# LargePrototype.net
KiCad netlist of a schematic drawn in EAGLE
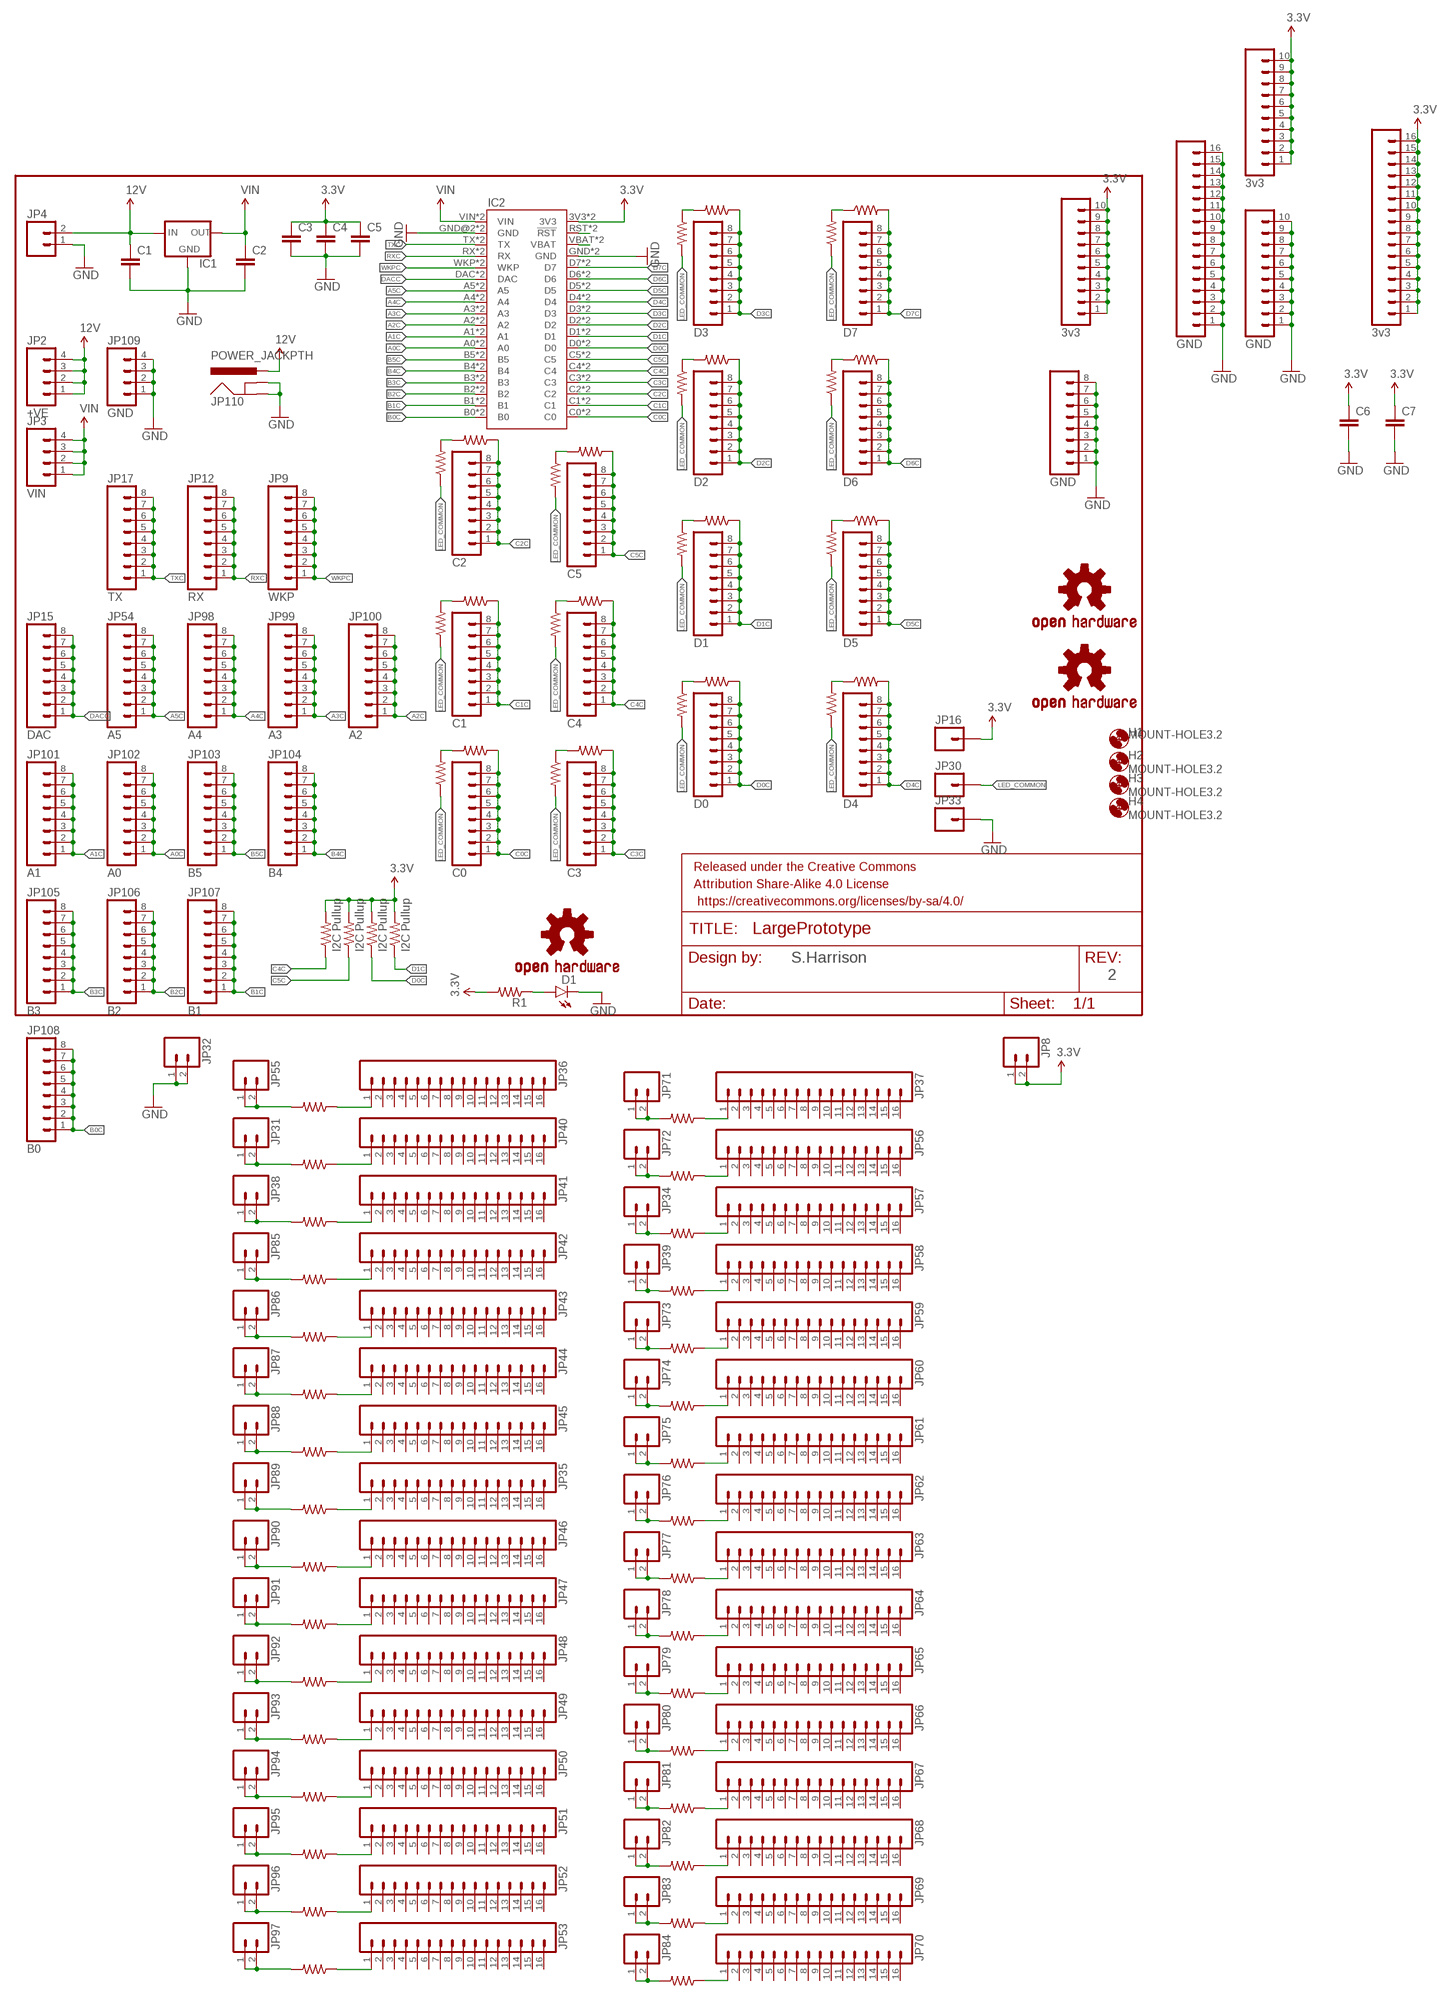
[diagram p0: schematic, sheet 1, part 1 of 2]
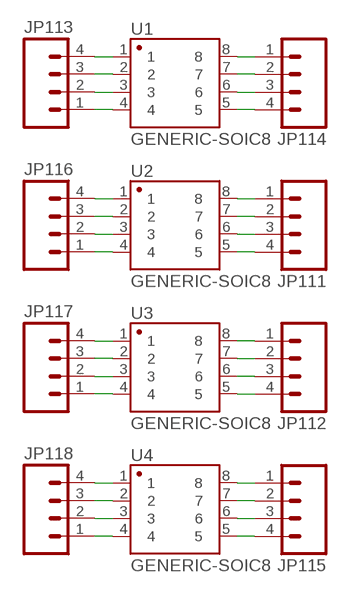
[diagram p1: schematic, sheet 1, part 2 of 2]

(export (version "E")
  (design (tool "Eeschema 10.0.6"))
  (components
    (comp (ref "C1")
      (value "1UF-25V-10%(0805)\"")
      (footprint "eagle-import:0805-CAP")
      (libsource (lib "eagle-import") (part "1UF-25V-10%(0805){dblquote}"))
    )
    (comp (ref "C2")
      (value "1UF-25V-10%(0805)\"")
      (footprint "eagle-import:0805-CAP")
      (libsource (lib "eagle-import") (part "1UF-25V-10%(0805){dblquote}"))
    )
    (comp (ref "C3")
      (value "1UF-25V-10%(0805)\"")
      (footprint "eagle-import:0805-CAP")
      (libsource (lib "eagle-import") (part "1UF-25V-10%(0805){dblquote}"))
    )
    (comp (ref "C4")
      (value "1UF-25V-10%(0805)\"")
      (footprint "eagle-import:0805-CAP")
      (libsource (lib "eagle-import") (part "1UF-25V-10%(0805){dblquote}"))
    )
    (comp (ref "C5")
      (value "1UF-25V-10%(0805)\"")
      (footprint "eagle-import:0805-CAP")
      (libsource (lib "eagle-import") (part "1UF-25V-10%(0805){dblquote}"))
    )
    (comp (ref "C6")
      (value "1UF-25V-10%(0805)\"")
      (footprint "eagle-import:0805-CAP")
      (libsource (lib "eagle-import") (part "1UF-25V-10%(0805){dblquote}"))
    )
    (comp (ref "C7")
      (value "1UF-25V-10%(0805)\"")
      (footprint "eagle-import:0805-CAP")
      (libsource (lib "eagle-import") (part "1UF-25V-10%(0805){dblquote}"))
    )
    (comp (ref "D1")
      (value "LED1206-BOTTOM")
      (footprint "eagle-import:LED-1206-BOTTOM")
      (libsource (lib "eagle-import") (part "LED1206-BOTTOM"))
    )
    (comp (ref "FRAME1")
      (value "FRAME-LETTER")
      (footprint "eagle-import:CREATIVE_COMMONS")
      (libsource (lib "eagle-import") (part "FRAME-LETTER"))
    )
    (comp (ref "H1")
      (value "MOUNT-HOLE3.2")
      (footprint "eagle-import:3,2")
      (libsource (lib "eagle-import") (part "MOUNT-HOLE3.2"))
    )
    (comp (ref "H2")
      (value "MOUNT-HOLE3.2")
      (footprint "eagle-import:3,2")
      (libsource (lib "eagle-import") (part "MOUNT-HOLE3.2"))
    )
    (comp (ref "H3")
      (value "MOUNT-HOLE3.2")
      (footprint "eagle-import:3,2")
      (libsource (lib "eagle-import") (part "MOUNT-HOLE3.2"))
    )
    (comp (ref "H4")
      (value "MOUNT-HOLE3.2")
      (footprint "eagle-import:3,2")
      (libsource (lib "eagle-import") (part "MOUNT-HOLE3.2"))
    )
    (comp (ref "IC1")
      (value "78XXS")
      (footprint "eagle-import:78XXS")
      (libsource (lib "eagle-import") (part "78XXS"))
    )
    (comp (ref "IC2")
      (value "ELECTRONDUALNAMED")
      (footprint "eagle-import:ELECTRON_SIMPLE_SILK_NAMES_DUAL")
      (libsource (lib "eagle-import") (part "ELECTRONDUALNAMED"))
    )
    (comp (ref "JP1")
      (value "D7")
      (footprint "eagle-import:1X08_ROUND")
      (libsource (lib "eagle-import") (part "M08"))
    )
    (comp (ref "JP2")
      (value "+VE")
      (footprint "eagle-import:1X04")
      (libsource (lib "eagle-import") (part "M04PTH"))
    )
    (comp (ref "JP3")
      (value "VIN")
      (footprint "eagle-import:1X04")
      (libsource (lib "eagle-import") (part "M04PTH"))
    )
    (comp (ref "JP4")
      (value "M025MM")
      (footprint "eagle-import:SCREWTERMINAL-5MM-2")
      (libsource (lib "eagle-import") (part "M025MM"))
    )
    (comp (ref "JP5")
      (value "3v3")
      (footprint "eagle-import:1X10")
      (libsource (lib "eagle-import") (part "M10SILK_FEMALE_PTH"))
    )
    (comp (ref "JP6")
      (value "3v3")
      (footprint "eagle-import:1X10")
      (libsource (lib "eagle-import") (part "M10SILK_FEMALE_PTH"))
    )
    (comp (ref "JP7")
      (value "D6")
      (footprint "eagle-import:1X08_ROUND")
      (libsource (lib "eagle-import") (part "M08"))
    )
    (comp (ref "JP8")
      (value "M02PTH")
      (footprint "eagle-import:1X02")
      (libsource (lib "eagle-import") (part "M02PTH"))
    )
    (comp (ref "JP9")
      (value "WKP")
      (footprint "eagle-import:1X08_ROUND")
      (libsource (lib "eagle-import") (part "M08"))
    )
    (comp (ref "JP10")
      (value "D5")
      (footprint "eagle-import:1X08_ROUND")
      (libsource (lib "eagle-import") (part "M08"))
    )
    (comp (ref "JP11")
      (value "GND")
      (footprint "eagle-import:1X10")
      (libsource (lib "eagle-import") (part "M10SILK_FEMALE_PTH"))
    )
    (comp (ref "JP12")
      (value "RX")
      (footprint "eagle-import:1X08_ROUND")
      (libsource (lib "eagle-import") (part "M08"))
    )
    (comp (ref "JP13")
      (value "3v3")
      (footprint "eagle-import:1X16")
      (libsource (lib "eagle-import") (part "M16PTH"))
    )
    (comp (ref "JP14")
      (value "GND")
      (footprint "eagle-import:1X16")
      (libsource (lib "eagle-import") (part "M16PTH"))
    )
    (comp (ref "JP15")
      (value "DAC")
      (footprint "eagle-import:1X08_ROUND")
      (libsource (lib "eagle-import") (part "M08"))
    )
    (comp (ref "JP16")
      (value "M01PTH")
      (footprint "eagle-import:1X01")
      (libsource (lib "eagle-import") (part "M01PTH"))
    )
    (comp (ref "JP17")
      (value "TX")
      (footprint "eagle-import:1X08_ROUND")
      (libsource (lib "eagle-import") (part "M08"))
    )
    (comp (ref "JP18")
      (value "D4")
      (footprint "eagle-import:1X08_ROUND")
      (libsource (lib "eagle-import") (part "M08"))
    )
    (comp (ref "JP19")
      (value "D3")
      (footprint "eagle-import:1X08_ROUND")
      (libsource (lib "eagle-import") (part "M08"))
    )
    (comp (ref "JP20")
      (value "D2")
      (footprint "eagle-import:1X08_ROUND")
      (libsource (lib "eagle-import") (part "M08"))
    )
    (comp (ref "JP21")
      (value "D1")
      (footprint "eagle-import:1X08_ROUND")
      (libsource (lib "eagle-import") (part "M08"))
    )
    (comp (ref "JP22")
      (value "D0")
      (footprint "eagle-import:1X08_ROUND")
      (libsource (lib "eagle-import") (part "M08"))
    )
    (comp (ref "JP23")
      (value "GND")
      (footprint "eagle-import:1X08_ROUND")
      (libsource (lib "eagle-import") (part "M08"))
    )
    (comp (ref "JP24")
      (value "C5")
      (footprint "eagle-import:1X08_ROUND")
      (libsource (lib "eagle-import") (part "M08"))
    )
    (comp (ref "JP25")
      (value "C4")
      (footprint "eagle-import:1X08_ROUND")
      (libsource (lib "eagle-import") (part "M08"))
    )
    (comp (ref "JP26")
      (value "C3")
      (footprint "eagle-import:1X08_ROUND")
      (libsource (lib "eagle-import") (part "M08"))
    )
    (comp (ref "JP27")
      (value "C2")
      (footprint "eagle-import:1X08_ROUND")
      (libsource (lib "eagle-import") (part "M08"))
    )
    (comp (ref "JP28")
      (value "C1")
      (footprint "eagle-import:1X08_ROUND")
      (libsource (lib "eagle-import") (part "M08"))
    )
    (comp (ref "JP29")
      (value "C0")
      (footprint "eagle-import:1X08_ROUND")
      (libsource (lib "eagle-import") (part "M08"))
    )
    (comp (ref "JP30")
      (value "M01PTH")
      (footprint "eagle-import:1X01")
      (libsource (lib "eagle-import") (part "M01PTH"))
    )
    (comp (ref "JP31")
      (value "M02PTH")
      (footprint "eagle-import:1X02")
      (libsource (lib "eagle-import") (part "M02PTH"))
    )
    (comp (ref "JP32")
      (value "M02PTH")
      (footprint "eagle-import:1X02")
      (libsource (lib "eagle-import") (part "M02PTH"))
    )
    (comp (ref "JP33")
      (value "M01PTH")
      (footprint "eagle-import:1X01")
      (libsource (lib "eagle-import") (part "M01PTH"))
    )
    (comp (ref "JP34")
      (value "M02PTH")
      (footprint "eagle-import:1X02")
      (libsource (lib "eagle-import") (part "M02PTH"))
    )
    (comp (ref "JP35")
      (value "M161X16_NO_SILK")
      (footprint "eagle-import:1X16_NO_SILK")
      (libsource (lib "eagle-import") (part "M161X16_NO_SILK"))
    )
    (comp (ref "JP36")
      (value "M161X16_NO_SILK")
      (footprint "eagle-import:1X16_NO_SILK")
      (libsource (lib "eagle-import") (part "M161X16_NO_SILK"))
    )
    (comp (ref "JP37")
      (value "M161X16_NO_SILK")
      (footprint "eagle-import:1X16_NO_SILK")
      (libsource (lib "eagle-import") (part "M161X16_NO_SILK"))
    )
    (comp (ref "JP38")
      (value "M02PTH")
      (footprint "eagle-import:1X02")
      (libsource (lib "eagle-import") (part "M02PTH"))
    )
    (comp (ref "JP39")
      (value "M02PTH")
      (footprint "eagle-import:1X02")
      (libsource (lib "eagle-import") (part "M02PTH"))
    )
    (comp (ref "JP40")
      (value "M161X16_NO_SILK")
      (footprint "eagle-import:1X16_NO_SILK")
      (libsource (lib "eagle-import") (part "M161X16_NO_SILK"))
    )
    (comp (ref "JP41")
      (value "M161X16_NO_SILK")
      (footprint "eagle-import:1X16_NO_SILK")
      (libsource (lib "eagle-import") (part "M161X16_NO_SILK"))
    )
    (comp (ref "JP42")
      (value "M161X16_NO_SILK")
      (footprint "eagle-import:1X16_NO_SILK")
      (libsource (lib "eagle-import") (part "M161X16_NO_SILK"))
    )
    (comp (ref "JP43")
      (value "M161X16_NO_SILK")
      (footprint "eagle-import:1X16_NO_SILK")
      (libsource (lib "eagle-import") (part "M161X16_NO_SILK"))
    )
    (comp (ref "JP44")
      (value "M161X16_NO_SILK")
      (footprint "eagle-import:1X16_NO_SILK")
      (libsource (lib "eagle-import") (part "M161X16_NO_SILK"))
    )
    (comp (ref "JP45")
      (value "M161X16_NO_SILK")
      (footprint "eagle-import:1X16_NO_SILK")
      (libsource (lib "eagle-import") (part "M161X16_NO_SILK"))
    )
    (comp (ref "JP46")
      (value "M161X16_NO_SILK")
      (footprint "eagle-import:1X16_NO_SILK")
      (libsource (lib "eagle-import") (part "M161X16_NO_SILK"))
    )
    (comp (ref "JP47")
      (value "M161X16_NO_SILK")
      (footprint "eagle-import:1X16_NO_SILK")
      (libsource (lib "eagle-import") (part "M161X16_NO_SILK"))
    )
    (comp (ref "JP48")
      (value "M161X16_NO_SILK")
      (footprint "eagle-import:1X16_NO_SILK")
      (libsource (lib "eagle-import") (part "M161X16_NO_SILK"))
    )
    (comp (ref "JP49")
      (value "M161X16_NO_SILK")
      (footprint "eagle-import:1X16_NO_SILK")
      (libsource (lib "eagle-import") (part "M161X16_NO_SILK"))
    )
    (comp (ref "JP50")
      (value "M161X16_NO_SILK")
      (footprint "eagle-import:1X16_NO_SILK")
      (libsource (lib "eagle-import") (part "M161X16_NO_SILK"))
    )
    (comp (ref "JP51")
      (value "M161X16_NO_SILK")
      (footprint "eagle-import:1X16_NO_SILK")
      (libsource (lib "eagle-import") (part "M161X16_NO_SILK"))
    )
    (comp (ref "JP52")
      (value "M161X16_NO_SILK")
      (footprint "eagle-import:1X16_NO_SILK")
      (libsource (lib "eagle-import") (part "M161X16_NO_SILK"))
    )
    (comp (ref "JP53")
      (value "M161X16_NO_SILK")
      (footprint "eagle-import:1X16_NO_SILK")
      (libsource (lib "eagle-import") (part "M161X16_NO_SILK"))
    )
    (comp (ref "JP54")
      (value "A5")
      (footprint "eagle-import:1X08_ROUND")
      (libsource (lib "eagle-import") (part "M08"))
    )
    (comp (ref "JP55")
      (value "M02PTH")
      (footprint "eagle-import:1X02")
      (libsource (lib "eagle-import") (part "M02PTH"))
    )
    (comp (ref "JP56")
      (value "M161X16_NO_SILK")
      (footprint "eagle-import:1X16_NO_SILK")
      (libsource (lib "eagle-import") (part "M161X16_NO_SILK"))
    )
    (comp (ref "JP57")
      (value "M161X16_NO_SILK")
      (footprint "eagle-import:1X16_NO_SILK")
      (libsource (lib "eagle-import") (part "M161X16_NO_SILK"))
    )
    (comp (ref "JP58")
      (value "M161X16_NO_SILK")
      (footprint "eagle-import:1X16_NO_SILK")
      (libsource (lib "eagle-import") (part "M161X16_NO_SILK"))
    )
    (comp (ref "JP59")
      (value "M161X16_NO_SILK")
      (footprint "eagle-import:1X16_NO_SILK")
      (libsource (lib "eagle-import") (part "M161X16_NO_SILK"))
    )
    (comp (ref "JP60")
      (value "M161X16_NO_SILK")
      (footprint "eagle-import:1X16_NO_SILK")
      (libsource (lib "eagle-import") (part "M161X16_NO_SILK"))
    )
    (comp (ref "JP61")
      (value "M161X16_NO_SILK")
      (footprint "eagle-import:1X16_NO_SILK")
      (libsource (lib "eagle-import") (part "M161X16_NO_SILK"))
    )
    (comp (ref "JP62")
      (value "M161X16_NO_SILK")
      (footprint "eagle-import:1X16_NO_SILK")
      (libsource (lib "eagle-import") (part "M161X16_NO_SILK"))
    )
    (comp (ref "JP63")
      (value "M161X16_NO_SILK")
      (footprint "eagle-import:1X16_NO_SILK")
      (libsource (lib "eagle-import") (part "M161X16_NO_SILK"))
    )
    (comp (ref "JP64")
      (value "M161X16_NO_SILK")
      (footprint "eagle-import:1X16_NO_SILK")
      (libsource (lib "eagle-import") (part "M161X16_NO_SILK"))
    )
    (comp (ref "JP65")
      (value "M161X16_NO_SILK")
      (footprint "eagle-import:1X16_NO_SILK")
      (libsource (lib "eagle-import") (part "M161X16_NO_SILK"))
    )
    (comp (ref "JP66")
      (value "M161X16_NO_SILK")
      (footprint "eagle-import:1X16_NO_SILK")
      (libsource (lib "eagle-import") (part "M161X16_NO_SILK"))
    )
    (comp (ref "JP67")
      (value "M161X16_NO_SILK")
      (footprint "eagle-import:1X16_NO_SILK")
      (libsource (lib "eagle-import") (part "M161X16_NO_SILK"))
    )
    (comp (ref "JP68")
      (value "M161X16_NO_SILK")
      (footprint "eagle-import:1X16_NO_SILK")
      (libsource (lib "eagle-import") (part "M161X16_NO_SILK"))
    )
    (comp (ref "JP69")
      (value "M161X16_NO_SILK")
      (footprint "eagle-import:1X16_NO_SILK")
      (libsource (lib "eagle-import") (part "M161X16_NO_SILK"))
    )
    (comp (ref "JP70")
      (value "M161X16_NO_SILK")
      (footprint "eagle-import:1X16_NO_SILK")
      (libsource (lib "eagle-import") (part "M161X16_NO_SILK"))
    )
    (comp (ref "JP71")
      (value "M02PTH")
      (footprint "eagle-import:1X02")
      (libsource (lib "eagle-import") (part "M02PTH"))
    )
    (comp (ref "JP72")
      (value "M02PTH")
      (footprint "eagle-import:1X02")
      (libsource (lib "eagle-import") (part "M02PTH"))
    )
    (comp (ref "JP73")
      (value "M02PTH")
      (footprint "eagle-import:1X02")
      (libsource (lib "eagle-import") (part "M02PTH"))
    )
    (comp (ref "JP74")
      (value "M02PTH")
      (footprint "eagle-import:1X02")
      (libsource (lib "eagle-import") (part "M02PTH"))
    )
    (comp (ref "JP75")
      (value "M02PTH")
      (footprint "eagle-import:1X02")
      (libsource (lib "eagle-import") (part "M02PTH"))
    )
    (comp (ref "JP76")
      (value "M02PTH")
      (footprint "eagle-import:1X02")
      (libsource (lib "eagle-import") (part "M02PTH"))
    )
    (comp (ref "JP77")
      (value "M02PTH")
      (footprint "eagle-import:1X02")
      (libsource (lib "eagle-import") (part "M02PTH"))
    )
    (comp (ref "JP78")
      (value "M02PTH")
      (footprint "eagle-import:1X02")
      (libsource (lib "eagle-import") (part "M02PTH"))
    )
    (comp (ref "JP79")
      (value "M02PTH")
      (footprint "eagle-import:1X02")
      (libsource (lib "eagle-import") (part "M02PTH"))
    )
    (comp (ref "JP80")
      (value "M02PTH")
      (footprint "eagle-import:1X02")
      (libsource (lib "eagle-import") (part "M02PTH"))
    )
    (comp (ref "JP81")
      (value "M02PTH")
      (footprint "eagle-import:1X02")
      (libsource (lib "eagle-import") (part "M02PTH"))
    )
    (comp (ref "JP82")
      (value "M02PTH")
      (footprint "eagle-import:1X02")
      (libsource (lib "eagle-import") (part "M02PTH"))
    )
    (comp (ref "JP83")
      (value "M02PTH")
      (footprint "eagle-import:1X02")
      (libsource (lib "eagle-import") (part "M02PTH"))
    )
    (comp (ref "JP84")
      (value "M02PTH")
      (footprint "eagle-import:1X02")
      (libsource (lib "eagle-import") (part "M02PTH"))
    )
    (comp (ref "JP85")
      (value "M02PTH")
      (footprint "eagle-import:1X02")
      (libsource (lib "eagle-import") (part "M02PTH"))
    )
    (comp (ref "JP86")
      (value "M02PTH")
      (footprint "eagle-import:1X02")
      (libsource (lib "eagle-import") (part "M02PTH"))
    )
    (comp (ref "JP87")
      (value "M02PTH")
      (footprint "eagle-import:1X02")
      (libsource (lib "eagle-import") (part "M02PTH"))
    )
    (comp (ref "JP88")
      (value "M02PTH")
      (footprint "eagle-import:1X02")
      (libsource (lib "eagle-import") (part "M02PTH"))
    )
    (comp (ref "JP89")
      (value "M02PTH")
      (footprint "eagle-import:1X02")
      (libsource (lib "eagle-import") (part "M02PTH"))
    )
    (comp (ref "JP90")
      (value "M02PTH")
      (footprint "eagle-import:1X02")
      (libsource (lib "eagle-import") (part "M02PTH"))
    )
    (comp (ref "JP91")
      (value "M02PTH")
      (footprint "eagle-import:1X02")
      (libsource (lib "eagle-import") (part "M02PTH"))
    )
    (comp (ref "JP92")
      (value "M02PTH")
      (footprint "eagle-import:1X02")
      (libsource (lib "eagle-import") (part "M02PTH"))
    )
    (comp (ref "JP93")
      (value "M02PTH")
      (footprint "eagle-import:1X02")
      (libsource (lib "eagle-import") (part "M02PTH"))
    )
    (comp (ref "JP94")
      (value "M02PTH")
      (footprint "eagle-import:1X02")
      (libsource (lib "eagle-import") (part "M02PTH"))
    )
    (comp (ref "JP95")
      (value "M02PTH")
      (footprint "eagle-import:1X02")
      (libsource (lib "eagle-import") (part "M02PTH"))
    )
    (comp (ref "JP96")
      (value "M02PTH")
      (footprint "eagle-import:1X02")
      (libsource (lib "eagle-import") (part "M02PTH"))
    )
    (comp (ref "JP97")
      (value "M02PTH")
      (footprint "eagle-import:1X02")
      (libsource (lib "eagle-import") (part "M02PTH"))
    )
    (comp (ref "JP98")
      (value "A4")
      (footprint "eagle-import:1X08_ROUND")
      (libsource (lib "eagle-import") (part "M08"))
    )
    (comp (ref "JP99")
      (value "A3")
      (footprint "eagle-import:1X08_ROUND")
      (libsource (lib "eagle-import") (part "M08"))
    )
    (comp (ref "JP100")
      (value "A2")
      (footprint "eagle-import:1X08_ROUND")
      (libsource (lib "eagle-import") (part "M08"))
    )
    (comp (ref "JP101")
      (value "A1")
      (footprint "eagle-import:1X08_ROUND")
      (libsource (lib "eagle-import") (part "M08"))
    )
    (comp (ref "JP102")
      (value "A0")
      (footprint "eagle-import:1X08_ROUND")
      (libsource (lib "eagle-import") (part "M08"))
    )
    (comp (ref "JP103")
      (value "B5")
      (footprint "eagle-import:1X08_ROUND")
      (libsource (lib "eagle-import") (part "M08"))
    )
    (comp (ref "JP104")
      (value "B4")
      (footprint "eagle-import:1X08_ROUND")
      (libsource (lib "eagle-import") (part "M08"))
    )
    (comp (ref "JP105")
      (value "B3")
      (footprint "eagle-import:1X08_ROUND")
      (libsource (lib "eagle-import") (part "M08"))
    )
    (comp (ref "JP106")
      (value "B2")
      (footprint "eagle-import:1X08_ROUND")
      (libsource (lib "eagle-import") (part "M08"))
    )
    (comp (ref "JP107")
      (value "B1")
      (footprint "eagle-import:1X08_ROUND")
      (libsource (lib "eagle-import") (part "M08"))
    )
    (comp (ref "JP108")
      (value "B0")
      (footprint "eagle-import:1X08_ROUND")
      (libsource (lib "eagle-import") (part "M08"))
    )
    (comp (ref "JP109")
      (value "GND")
      (footprint "eagle-import:1X04")
      (libsource (lib "eagle-import") (part "M04PTH"))
    )
    (comp (ref "JP110")
      (value "POWER_JACKPTH")
      (footprint "eagle-import:POWER_JACK_PTH")
      (libsource (lib "eagle-import") (part "POWER_JACKPTH"))
    )
    (comp (ref "JP111")
      (value "M04NO_SILK_ALL_ROUND")
      (footprint "eagle-import:1X04_NO_SILK_ALL_ROUND")
      (libsource (lib "eagle-import") (part "M04NO_SILK_ALL_ROUND"))
    )
    (comp (ref "JP112")
      (value "M04NO_SILK_ALL_ROUND")
      (footprint "eagle-import:1X04_NO_SILK_ALL_ROUND")
      (libsource (lib "eagle-import") (part "M04NO_SILK_ALL_ROUND"))
    )
    (comp (ref "JP113")
      (value "M04NO_SILK_ALL_ROUND")
      (footprint "eagle-import:1X04_NO_SILK_ALL_ROUND")
      (libsource (lib "eagle-import") (part "M04NO_SILK_ALL_ROUND"))
    )
    (comp (ref "JP114")
      (value "M04NO_SILK_ALL_ROUND")
      (footprint "eagle-import:1X04_NO_SILK_ALL_ROUND")
      (libsource (lib "eagle-import") (part "M04NO_SILK_ALL_ROUND"))
    )
    (comp (ref "JP115")
      (value "M04NO_SILK_ALL_ROUND")
      (footprint "eagle-import:1X04_NO_SILK_ALL_ROUND")
      (libsource (lib "eagle-import") (part "M04NO_SILK_ALL_ROUND"))
    )
    (comp (ref "JP116")
      (value "M04NO_SILK_ALL_ROUND")
      (footprint "eagle-import:1X04_NO_SILK_ALL_ROUND")
      (libsource (lib "eagle-import") (part "M04NO_SILK_ALL_ROUND"))
    )
    (comp (ref "JP117")
      (value "M04NO_SILK_ALL_ROUND")
      (footprint "eagle-import:1X04_NO_SILK_ALL_ROUND")
      (libsource (lib "eagle-import") (part "M04NO_SILK_ALL_ROUND"))
    )
    (comp (ref "JP118")
      (value "M04NO_SILK_ALL_ROUND")
      (footprint "eagle-import:1X04_NO_SILK_ALL_ROUND")
      (libsource (lib "eagle-import") (part "M04NO_SILK_ALL_ROUND"))
    )
    (comp (ref "LOGO1")
      (value "OSHW-LOGOL")
      (footprint "eagle-import:OSHW-LOGO-L")
      (libsource (lib "eagle-import") (part "OSHW-LOGOL"))
    )
    (comp (ref "LOGO2")
      (value "OSHW-LOGOL")
      (footprint "eagle-import:OSHW-LOGO-L")
      (libsource (lib "eagle-import") (part "OSHW-LOGOL"))
    )
    (comp (ref "LOGO3")
      (value "OSHW-LOGOM")
      (footprint "eagle-import:OSHW-LOGO-M")
      (libsource (lib "eagle-import") (part "OSHW-LOGOM"))
    )
    (comp (ref "R1")
      (value "RESISTOR1206")
      (footprint "eagle-import:1206")
      (libsource (lib "eagle-import") (part "RESISTOR1206"))
    )
    (comp (ref "R2")
      (value "RESISTOR1206")
      (footprint "eagle-import:1206")
      (libsource (lib "eagle-import") (part "RESISTOR1206"))
    )
    (comp (ref "R3")
      (value "RESISTOR1206")
      (footprint "eagle-import:1206")
      (libsource (lib "eagle-import") (part "RESISTOR1206"))
    )
    (comp (ref "R4")
      (value "RESISTOR1206")
      (footprint "eagle-import:1206")
      (libsource (lib "eagle-import") (part "RESISTOR1206"))
    )
    (comp (ref "R5")
      (value "RESISTOR1206")
      (footprint "eagle-import:1206")
      (libsource (lib "eagle-import") (part "RESISTOR1206"))
    )
    (comp (ref "R6")
      (value "RESISTOR1206")
      (footprint "eagle-import:1206")
      (libsource (lib "eagle-import") (part "RESISTOR1206"))
    )
    (comp (ref "R7")
      (value "RESISTOR1206")
      (footprint "eagle-import:1206")
      (libsource (lib "eagle-import") (part "RESISTOR1206"))
    )
    (comp (ref "R8")
      (value "RESISTOR1206")
      (footprint "eagle-import:1206")
      (libsource (lib "eagle-import") (part "RESISTOR1206"))
    )
    (comp (ref "R9")
      (value "RESISTOR1206")
      (footprint "eagle-import:1206")
      (libsource (lib "eagle-import") (part "RESISTOR1206"))
    )
    (comp (ref "R10")
      (value "RESISTOR1206")
      (footprint "eagle-import:1206")
      (libsource (lib "eagle-import") (part "RESISTOR1206"))
    )
    (comp (ref "R11")
      (value "RESISTOR1206")
      (footprint "eagle-import:1206")
      (libsource (lib "eagle-import") (part "RESISTOR1206"))
    )
    (comp (ref "R12")
      (value "RESISTOR1206")
      (footprint "eagle-import:1206")
      (libsource (lib "eagle-import") (part "RESISTOR1206"))
    )
    (comp (ref "R13")
      (value "RESISTOR1206")
      (footprint "eagle-import:1206")
      (libsource (lib "eagle-import") (part "RESISTOR1206"))
    )
    (comp (ref "R14")
      (value "RESISTOR1206")
      (footprint "eagle-import:1206")
      (libsource (lib "eagle-import") (part "RESISTOR1206"))
    )
    (comp (ref "R15")
      (value "RESISTOR1206")
      (footprint "eagle-import:1206")
      (libsource (lib "eagle-import") (part "RESISTOR1206"))
    )
    (comp (ref "R16")
      (value "RESISTOR1206")
      (footprint "eagle-import:1206")
      (libsource (lib "eagle-import") (part "RESISTOR1206"))
    )
    (comp (ref "R17")
      (value "RESISTOR1206")
      (footprint "eagle-import:1206")
      (libsource (lib "eagle-import") (part "RESISTOR1206"))
    )
    (comp (ref "R18")
      (value "RESISTOR1206")
      (footprint "eagle-import:1206")
      (libsource (lib "eagle-import") (part "RESISTOR1206"))
    )
    (comp (ref "R19")
      (value "RESISTOR1206")
      (footprint "eagle-import:1206")
      (libsource (lib "eagle-import") (part "RESISTOR1206"))
    )
    (comp (ref "R20")
      (value "RESISTOR1206")
      (footprint "eagle-import:1206")
      (libsource (lib "eagle-import") (part "RESISTOR1206"))
    )
    (comp (ref "R21")
      (value "RESISTOR1206")
      (footprint "eagle-import:1206")
      (libsource (lib "eagle-import") (part "RESISTOR1206"))
    )
    (comp (ref "R22")
      (value "RESISTOR1206")
      (footprint "eagle-import:1206")
      (libsource (lib "eagle-import") (part "RESISTOR1206"))
    )
    (comp (ref "R23")
      (value "RESISTOR1206")
      (footprint "eagle-import:1206")
      (libsource (lib "eagle-import") (part "RESISTOR1206"))
    )
    (comp (ref "R24")
      (value "RESISTOR1206")
      (footprint "eagle-import:1206")
      (libsource (lib "eagle-import") (part "RESISTOR1206"))
    )
    (comp (ref "R25")
      (value "RESISTOR1206")
      (footprint "eagle-import:1206")
      (libsource (lib "eagle-import") (part "RESISTOR1206"))
    )
    (comp (ref "R26")
      (value "RESISTOR1206")
      (footprint "eagle-import:1206")
      (libsource (lib "eagle-import") (part "RESISTOR1206"))
    )
    (comp (ref "R27")
      (value "RESISTOR1206")
      (footprint "eagle-import:1206")
      (libsource (lib "eagle-import") (part "RESISTOR1206"))
    )
    (comp (ref "R28")
      (value "RESISTOR1206")
      (footprint "eagle-import:1206")
      (libsource (lib "eagle-import") (part "RESISTOR1206"))
    )
    (comp (ref "R29")
      (value "RESISTOR1206")
      (footprint "eagle-import:1206")
      (libsource (lib "eagle-import") (part "RESISTOR1206"))
    )
    (comp (ref "R30")
      (value "RESISTOR1206")
      (footprint "eagle-import:1206")
      (libsource (lib "eagle-import") (part "RESISTOR1206"))
    )
    (comp (ref "R31")
      (value "RESISTOR1206")
      (footprint "eagle-import:1206")
      (libsource (lib "eagle-import") (part "RESISTOR1206"))
    )
    (comp (ref "R32")
      (value "RESISTOR1206")
      (footprint "eagle-import:1206")
      (libsource (lib "eagle-import") (part "RESISTOR1206"))
    )
    (comp (ref "R33")
      (value "RESISTOR1206")
      (footprint "eagle-import:1206")
      (libsource (lib "eagle-import") (part "RESISTOR1206"))
    )
    (comp (ref "R34")
      (value "RESISTOR1206")
      (footprint "eagle-import:1206")
      (libsource (lib "eagle-import") (part "RESISTOR1206"))
    )
    (comp (ref "R35")
      (value "RESISTOR1206")
      (footprint "eagle-import:1206")
      (libsource (lib "eagle-import") (part "RESISTOR1206"))
    )
    (comp (ref "R36")
      (value "RESISTOR1206")
      (footprint "eagle-import:1206")
      (libsource (lib "eagle-import") (part "RESISTOR1206"))
    )
    (comp (ref "R37")
      (value "RESISTOR1206")
      (footprint "eagle-import:1206")
      (libsource (lib "eagle-import") (part "RESISTOR1206"))
    )
    (comp (ref "R38")
      (value "RESISTOR1206")
      (footprint "eagle-import:1206")
      (libsource (lib "eagle-import") (part "RESISTOR1206"))
    )
    (comp (ref "R39")
      (value "RESISTOR1206")
      (footprint "eagle-import:1206")
      (libsource (lib "eagle-import") (part "RESISTOR1206"))
    )
    (comp (ref "R40")
      (value "RESISTOR1206")
      (footprint "eagle-import:1206")
      (libsource (lib "eagle-import") (part "RESISTOR1206"))
    )
    (comp (ref "R41")
      (value "RESISTOR1206")
      (footprint "eagle-import:1206")
      (libsource (lib "eagle-import") (part "RESISTOR1206"))
    )
    (comp (ref "R42")
      (value "RESISTOR1206")
      (footprint "eagle-import:1206")
      (libsource (lib "eagle-import") (part "RESISTOR1206"))
    )
    (comp (ref "R43")
      (value "RESISTOR1206")
      (footprint "eagle-import:1206")
      (libsource (lib "eagle-import") (part "RESISTOR1206"))
    )
    (comp (ref "R44")
      (value "RESISTOR1206")
      (footprint "eagle-import:1206")
      (libsource (lib "eagle-import") (part "RESISTOR1206"))
    )
    (comp (ref "R45")
      (value "RESISTOR1206")
      (footprint "eagle-import:1206")
      (libsource (lib "eagle-import") (part "RESISTOR1206"))
    )
    (comp (ref "R46")
      (value "RESISTOR1206")
      (footprint "eagle-import:1206")
      (libsource (lib "eagle-import") (part "RESISTOR1206"))
    )
    (comp (ref "R47")
      (value "RESISTOR1206")
      (footprint "eagle-import:1206")
      (libsource (lib "eagle-import") (part "RESISTOR1206"))
    )
    (comp (ref "R48")
      (value "RESISTOR1206")
      (footprint "eagle-import:1206")
      (libsource (lib "eagle-import") (part "RESISTOR1206"))
    )
    (comp (ref "R49")
      (value "RESISTOR1206")
      (footprint "eagle-import:1206")
      (libsource (lib "eagle-import") (part "RESISTOR1206"))
    )
    (comp (ref "R50")
      (value "RESISTOR1206")
      (footprint "eagle-import:1206")
      (libsource (lib "eagle-import") (part "RESISTOR1206"))
    )
    (comp (ref "R51")
      (value "RESISTOR1206")
      (footprint "eagle-import:1206")
      (libsource (lib "eagle-import") (part "RESISTOR1206"))
    )
    (comp (ref "R52")
      (value "RESISTOR1206")
      (footprint "eagle-import:1206")
      (libsource (lib "eagle-import") (part "RESISTOR1206"))
    )
    (comp (ref "R53")
      (value "RESISTOR1206")
      (footprint "eagle-import:1206")
      (libsource (lib "eagle-import") (part "RESISTOR1206"))
    )
    (comp (ref "R54")
      (value "RESISTOR1206")
      (footprint "eagle-import:1206")
      (libsource (lib "eagle-import") (part "RESISTOR1206"))
    )
    (comp (ref "R55")
      (value "RESISTOR1206")
      (footprint "eagle-import:1206")
      (libsource (lib "eagle-import") (part "RESISTOR1206"))
    )
    (comp (ref "R56")
      (value "RESISTOR1206")
      (footprint "eagle-import:1206")
      (libsource (lib "eagle-import") (part "RESISTOR1206"))
    )
    (comp (ref "R57")
      (value "RESISTOR1206")
      (footprint "eagle-import:1206")
      (libsource (lib "eagle-import") (part "RESISTOR1206"))
    )
    (comp (ref "R58")
      (value "RESISTOR1206")
      (footprint "eagle-import:1206")
      (libsource (lib "eagle-import") (part "RESISTOR1206"))
    )
    (comp (ref "R59")
      (value "RESISTOR1206")
      (footprint "eagle-import:1206")
      (libsource (lib "eagle-import") (part "RESISTOR1206"))
    )
    (comp (ref "R60")
      (value "RESISTOR1206")
      (footprint "eagle-import:1206")
      (libsource (lib "eagle-import") (part "RESISTOR1206"))
    )
    (comp (ref "R61")
      (value "RESISTOR1206")
      (footprint "eagle-import:1206")
      (libsource (lib "eagle-import") (part "RESISTOR1206"))
    )
    (comp (ref "R62")
      (value "I2C Pullup")
      (footprint "eagle-import:1206")
      (libsource (lib "eagle-import") (part "RESISTOR1206"))
    )
    (comp (ref "R63")
      (value "I2C Pullup")
      (footprint "eagle-import:1206")
      (libsource (lib "eagle-import") (part "RESISTOR1206"))
    )
    (comp (ref "R64")
      (value "I2C Pullup")
      (footprint "eagle-import:1206")
      (libsource (lib "eagle-import") (part "RESISTOR1206"))
    )
    (comp (ref "R65")
      (value "I2C Pullup")
      (footprint "eagle-import:1206")
      (libsource (lib "eagle-import") (part "RESISTOR1206"))
    )
    (comp (ref "U1")
      (value "GENERIC-SOIC8")
      (footprint "eagle-import:SO08-UNIVERSAL")
      (libsource (lib "eagle-import") (part "GENERIC-SOIC8"))
    )
    (comp (ref "U2")
      (value "GENERIC-SOIC8")
      (footprint "eagle-import:SO08-UNIVERSAL")
      (libsource (lib "eagle-import") (part "GENERIC-SOIC8"))
    )
    (comp (ref "U3")
      (value "GENERIC-SOIC8")
      (footprint "eagle-import:SO08-UNIVERSAL")
      (libsource (lib "eagle-import") (part "GENERIC-SOIC8"))
    )
    (comp (ref "U4")
      (value "GENERIC-SOIC8")
      (footprint "eagle-import:SO08-UNIVERSAL")
      (libsource (lib "eagle-import") (part "GENERIC-SOIC8"))
    )
  )
  (nets
    (net (code "1") (name "3.3V") (class "Default")
      (node (ref "C3") (pin "1") (pinfunction "1_1") (pintype "passive"))
      (node (ref "C4") (pin "1") (pinfunction "1_1") (pintype "passive"))
      (node (ref "C5") (pin "1") (pinfunction "1_1") (pintype "passive"))
      (node (ref "C6") (pin "1") (pinfunction "1_1") (pintype "passive"))
      (node (ref "C7") (pin "1") (pinfunction "1_1") (pintype "passive"))
      (node (ref "IC2") (pin "3V3") (pinfunction "3V3_3V3") (pintype "power_in"))
      (node (ref "IC2") (pin "3V3_1") (pinfunction "3V3_3V3_1") (pintype "power_in"))
      (node (ref "JP13") (pin "1") (pinfunction "1_1") (pintype "passive"))
      (node (ref "JP13") (pin "10") (pinfunction "10_10") (pintype "passive"))
      (node (ref "JP13") (pin "11") (pinfunction "11_11") (pintype "passive"))
      (node (ref "JP13") (pin "12") (pinfunction "12_12") (pintype "passive"))
      (node (ref "JP13") (pin "13") (pinfunction "13_13") (pintype "passive"))
      (node (ref "JP13") (pin "14") (pinfunction "14_14") (pintype "passive"))
      (node (ref "JP13") (pin "15") (pinfunction "15_15") (pintype "passive"))
      (node (ref "JP13") (pin "16") (pinfunction "16_16") (pintype "passive"))
      (node (ref "JP13") (pin "2") (pinfunction "2_2") (pintype "passive"))
      (node (ref "JP13") (pin "3") (pinfunction "3_3") (pintype "passive"))
      (node (ref "JP13") (pin "4") (pinfunction "4_4") (pintype "passive"))
      (node (ref "JP13") (pin "5") (pinfunction "5_5") (pintype "passive"))
      (node (ref "JP13") (pin "6") (pinfunction "6_6") (pintype "passive"))
      (node (ref "JP13") (pin "7") (pinfunction "7_7") (pintype "passive"))
      (node (ref "JP13") (pin "8") (pinfunction "8_8") (pintype "passive"))
      (node (ref "JP13") (pin "9") (pinfunction "9_9") (pintype "passive"))
      (node (ref "JP16") (pin "1") (pinfunction "1_1") (pintype "passive"))
      (node (ref "JP5") (pin "1") (pinfunction "1_1") (pintype "passive"))
      (node (ref "JP5") (pin "10") (pinfunction "10_10") (pintype "passive"))
      (node (ref "JP5") (pin "2") (pinfunction "2_2") (pintype "passive"))
      (node (ref "JP5") (pin "3") (pinfunction "3_3") (pintype "passive"))
      (node (ref "JP5") (pin "4") (pinfunction "4_4") (pintype "passive"))
      (node (ref "JP5") (pin "5") (pinfunction "5_5") (pintype "passive"))
      (node (ref "JP5") (pin "6") (pinfunction "6_6") (pintype "passive"))
      (node (ref "JP5") (pin "7") (pinfunction "7_7") (pintype "passive"))
      (node (ref "JP5") (pin "8") (pinfunction "8_8") (pintype "passive"))
      (node (ref "JP5") (pin "9") (pinfunction "9_9") (pintype "passive"))
      (node (ref "JP6") (pin "1") (pinfunction "1_1") (pintype "passive"))
      (node (ref "JP6") (pin "10") (pinfunction "10_10") (pintype "passive"))
      (node (ref "JP6") (pin "2") (pinfunction "2_2") (pintype "passive"))
      (node (ref "JP6") (pin "3") (pinfunction "3_3") (pintype "passive"))
      (node (ref "JP6") (pin "4") (pinfunction "4_4") (pintype "passive"))
      (node (ref "JP6") (pin "5") (pinfunction "5_5") (pintype "passive"))
      (node (ref "JP6") (pin "6") (pinfunction "6_6") (pintype "passive"))
      (node (ref "JP6") (pin "7") (pinfunction "7_7") (pintype "passive"))
      (node (ref "JP6") (pin "8") (pinfunction "8_8") (pintype "passive"))
      (node (ref "JP6") (pin "9") (pinfunction "9_9") (pintype "passive"))
      (node (ref "JP8") (pin "1") (pinfunction "1_1") (pintype "passive"))
      (node (ref "JP8") (pin "2") (pinfunction "2_2") (pintype "passive"))
      (node (ref "R1") (pin "2") (pinfunction "2_2") (pintype "passive"))
      (node (ref "R62") (pin "2") (pinfunction "2_2") (pintype "passive"))
      (node (ref "R63") (pin "2") (pinfunction "2_2") (pintype "passive"))
      (node (ref "R64") (pin "2") (pinfunction "2_2") (pintype "passive"))
      (node (ref "R65") (pin "2") (pinfunction "2_2") (pintype "passive"))
    )
    (net (code "2") (name "12V") (class "Default")
      (node (ref "C1") (pin "1") (pinfunction "1_1") (pintype "passive"))
      (node (ref "IC1") (pin "IN") (pinfunction "IN_IN") (pintype "input"))
      (node (ref "JP110") (pin "PWR") (pinfunction "PWR_PWR") (pintype "bidirectional"))
      (node (ref "JP2") (pin "1") (pinfunction "1_1") (pintype "passive"))
      (node (ref "JP2") (pin "2") (pinfunction "2_2") (pintype "passive"))
      (node (ref "JP2") (pin "3") (pinfunction "3_3") (pintype "passive"))
      (node (ref "JP2") (pin "4") (pinfunction "4_4") (pintype "passive"))
      (node (ref "JP4") (pin "2") (pinfunction "2_2") (pintype "passive"))
    )
    (net (code "3") (name "A0C") (class "Default")
      (node (ref "IC2") (pin "A0") (pinfunction "A0_A0") (pintype "bidirectional"))
      (node (ref "IC2") (pin "A0_1") (pinfunction "A0_A0_1") (pintype "bidirectional"))
      (node (ref "JP102") (pin "1") (pinfunction "1_1") (pintype "passive"))
      (node (ref "JP102") (pin "2") (pinfunction "2_2") (pintype "passive"))
      (node (ref "JP102") (pin "3") (pinfunction "3_3") (pintype "passive"))
      (node (ref "JP102") (pin "4") (pinfunction "4_4") (pintype "passive"))
      (node (ref "JP102") (pin "5") (pinfunction "5_5") (pintype "passive"))
      (node (ref "JP102") (pin "6") (pinfunction "6_6") (pintype "passive"))
      (node (ref "JP102") (pin "7") (pinfunction "7_7") (pintype "passive"))
      (node (ref "JP102") (pin "8") (pinfunction "8_8") (pintype "passive"))
    )
    (net (code "4") (name "A1C") (class "Default")
      (node (ref "IC2") (pin "A1") (pinfunction "A1_A1") (pintype "bidirectional"))
      (node (ref "IC2") (pin "A1_1") (pinfunction "A1_A1_1") (pintype "bidirectional"))
      (node (ref "JP101") (pin "1") (pinfunction "1_1") (pintype "passive"))
      (node (ref "JP101") (pin "2") (pinfunction "2_2") (pintype "passive"))
      (node (ref "JP101") (pin "3") (pinfunction "3_3") (pintype "passive"))
      (node (ref "JP101") (pin "4") (pinfunction "4_4") (pintype "passive"))
      (node (ref "JP101") (pin "5") (pinfunction "5_5") (pintype "passive"))
      (node (ref "JP101") (pin "6") (pinfunction "6_6") (pintype "passive"))
      (node (ref "JP101") (pin "7") (pinfunction "7_7") (pintype "passive"))
      (node (ref "JP101") (pin "8") (pinfunction "8_8") (pintype "passive"))
    )
    (net (code "5") (name "A2C") (class "Default")
      (node (ref "IC2") (pin "A2") (pinfunction "A2_A2") (pintype "bidirectional"))
      (node (ref "IC2") (pin "A2_1") (pinfunction "A2_A2_1") (pintype "bidirectional"))
      (node (ref "JP100") (pin "1") (pinfunction "1_1") (pintype "passive"))
      (node (ref "JP100") (pin "2") (pinfunction "2_2") (pintype "passive"))
      (node (ref "JP100") (pin "3") (pinfunction "3_3") (pintype "passive"))
      (node (ref "JP100") (pin "4") (pinfunction "4_4") (pintype "passive"))
      (node (ref "JP100") (pin "5") (pinfunction "5_5") (pintype "passive"))
      (node (ref "JP100") (pin "6") (pinfunction "6_6") (pintype "passive"))
      (node (ref "JP100") (pin "7") (pinfunction "7_7") (pintype "passive"))
      (node (ref "JP100") (pin "8") (pinfunction "8_8") (pintype "passive"))
    )
    (net (code "6") (name "A3C") (class "Default")
      (node (ref "IC2") (pin "A3") (pinfunction "A3_A3") (pintype "bidirectional"))
      (node (ref "IC2") (pin "A3_1") (pinfunction "A3_A3_1") (pintype "bidirectional"))
      (node (ref "JP99") (pin "1") (pinfunction "1_1") (pintype "passive"))
      (node (ref "JP99") (pin "2") (pinfunction "2_2") (pintype "passive"))
      (node (ref "JP99") (pin "3") (pinfunction "3_3") (pintype "passive"))
      (node (ref "JP99") (pin "4") (pinfunction "4_4") (pintype "passive"))
      (node (ref "JP99") (pin "5") (pinfunction "5_5") (pintype "passive"))
      (node (ref "JP99") (pin "6") (pinfunction "6_6") (pintype "passive"))
      (node (ref "JP99") (pin "7") (pinfunction "7_7") (pintype "passive"))
      (node (ref "JP99") (pin "8") (pinfunction "8_8") (pintype "passive"))
    )
    (net (code "7") (name "A4C") (class "Default")
      (node (ref "IC2") (pin "A4") (pinfunction "A4_A4") (pintype "bidirectional"))
      (node (ref "IC2") (pin "A4_1") (pinfunction "A4_A4_1") (pintype "bidirectional"))
      (node (ref "JP98") (pin "1") (pinfunction "1_1") (pintype "passive"))
      (node (ref "JP98") (pin "2") (pinfunction "2_2") (pintype "passive"))
      (node (ref "JP98") (pin "3") (pinfunction "3_3") (pintype "passive"))
      (node (ref "JP98") (pin "4") (pinfunction "4_4") (pintype "passive"))
      (node (ref "JP98") (pin "5") (pinfunction "5_5") (pintype "passive"))
      (node (ref "JP98") (pin "6") (pinfunction "6_6") (pintype "passive"))
      (node (ref "JP98") (pin "7") (pinfunction "7_7") (pintype "passive"))
      (node (ref "JP98") (pin "8") (pinfunction "8_8") (pintype "passive"))
    )
    (net (code "8") (name "A5C") (class "Default")
      (node (ref "IC2") (pin "A5") (pinfunction "A5_A5") (pintype "bidirectional"))
      (node (ref "IC2") (pin "A5_1") (pinfunction "A5_A5_1") (pintype "bidirectional"))
      (node (ref "JP54") (pin "1") (pinfunction "1_1") (pintype "passive"))
      (node (ref "JP54") (pin "2") (pinfunction "2_2") (pintype "passive"))
      (node (ref "JP54") (pin "3") (pinfunction "3_3") (pintype "passive"))
      (node (ref "JP54") (pin "4") (pinfunction "4_4") (pintype "passive"))
      (node (ref "JP54") (pin "5") (pinfunction "5_5") (pintype "passive"))
      (node (ref "JP54") (pin "6") (pinfunction "6_6") (pintype "passive"))
      (node (ref "JP54") (pin "7") (pinfunction "7_7") (pintype "passive"))
      (node (ref "JP54") (pin "8") (pinfunction "8_8") (pintype "passive"))
    )
    (net (code "9") (name "B0C") (class "Default")
      (node (ref "IC2") (pin "B0") (pinfunction "B0_B0") (pintype "bidirectional"))
      (node (ref "IC2") (pin "B0_1") (pinfunction "B0_B0_1") (pintype "bidirectional"))
      (node (ref "JP108") (pin "1") (pinfunction "1_1") (pintype "passive"))
      (node (ref "JP108") (pin "2") (pinfunction "2_2") (pintype "passive"))
      (node (ref "JP108") (pin "3") (pinfunction "3_3") (pintype "passive"))
      (node (ref "JP108") (pin "4") (pinfunction "4_4") (pintype "passive"))
      (node (ref "JP108") (pin "5") (pinfunction "5_5") (pintype "passive"))
      (node (ref "JP108") (pin "6") (pinfunction "6_6") (pintype "passive"))
      (node (ref "JP108") (pin "7") (pinfunction "7_7") (pintype "passive"))
      (node (ref "JP108") (pin "8") (pinfunction "8_8") (pintype "passive"))
    )
    (net (code "10") (name "B1C") (class "Default")
      (node (ref "IC2") (pin "B1") (pinfunction "B1_B1") (pintype "bidirectional"))
      (node (ref "IC2") (pin "B1_1") (pinfunction "B1_B1_1") (pintype "bidirectional"))
      (node (ref "JP107") (pin "1") (pinfunction "1_1") (pintype "passive"))
      (node (ref "JP107") (pin "2") (pinfunction "2_2") (pintype "passive"))
      (node (ref "JP107") (pin "3") (pinfunction "3_3") (pintype "passive"))
      (node (ref "JP107") (pin "4") (pinfunction "4_4") (pintype "passive"))
      (node (ref "JP107") (pin "5") (pinfunction "5_5") (pintype "passive"))
      (node (ref "JP107") (pin "6") (pinfunction "6_6") (pintype "passive"))
      (node (ref "JP107") (pin "7") (pinfunction "7_7") (pintype "passive"))
      (node (ref "JP107") (pin "8") (pinfunction "8_8") (pintype "passive"))
    )
    (net (code "11") (name "B2C") (class "Default")
      (node (ref "IC2") (pin "B2") (pinfunction "B2_B2") (pintype "bidirectional"))
      (node (ref "IC2") (pin "B2_1") (pinfunction "B2_B2_1") (pintype "bidirectional"))
      (node (ref "JP106") (pin "1") (pinfunction "1_1") (pintype "passive"))
      (node (ref "JP106") (pin "2") (pinfunction "2_2") (pintype "passive"))
      (node (ref "JP106") (pin "3") (pinfunction "3_3") (pintype "passive"))
      (node (ref "JP106") (pin "4") (pinfunction "4_4") (pintype "passive"))
      (node (ref "JP106") (pin "5") (pinfunction "5_5") (pintype "passive"))
      (node (ref "JP106") (pin "6") (pinfunction "6_6") (pintype "passive"))
      (node (ref "JP106") (pin "7") (pinfunction "7_7") (pintype "passive"))
      (node (ref "JP106") (pin "8") (pinfunction "8_8") (pintype "passive"))
    )
    (net (code "12") (name "B3C") (class "Default")
      (node (ref "IC2") (pin "B3") (pinfunction "B3_B3") (pintype "bidirectional"))
      (node (ref "IC2") (pin "B3_1") (pinfunction "B3_B3_1") (pintype "bidirectional"))
      (node (ref "JP105") (pin "1") (pinfunction "1_1") (pintype "passive"))
      (node (ref "JP105") (pin "2") (pinfunction "2_2") (pintype "passive"))
      (node (ref "JP105") (pin "3") (pinfunction "3_3") (pintype "passive"))
      (node (ref "JP105") (pin "4") (pinfunction "4_4") (pintype "passive"))
      (node (ref "JP105") (pin "5") (pinfunction "5_5") (pintype "passive"))
      (node (ref "JP105") (pin "6") (pinfunction "6_6") (pintype "passive"))
      (node (ref "JP105") (pin "7") (pinfunction "7_7") (pintype "passive"))
      (node (ref "JP105") (pin "8") (pinfunction "8_8") (pintype "passive"))
    )
    (net (code "13") (name "B4C") (class "Default")
      (node (ref "IC2") (pin "B4") (pinfunction "B4_B4") (pintype "bidirectional"))
      (node (ref "IC2") (pin "B4_1") (pinfunction "B4_B4_1") (pintype "bidirectional"))
      (node (ref "JP104") (pin "1") (pinfunction "1_1") (pintype "passive"))
      (node (ref "JP104") (pin "2") (pinfunction "2_2") (pintype "passive"))
      (node (ref "JP104") (pin "3") (pinfunction "3_3") (pintype "passive"))
      (node (ref "JP104") (pin "4") (pinfunction "4_4") (pintype "passive"))
      (node (ref "JP104") (pin "5") (pinfunction "5_5") (pintype "passive"))
      (node (ref "JP104") (pin "6") (pinfunction "6_6") (pintype "passive"))
      (node (ref "JP104") (pin "7") (pinfunction "7_7") (pintype "passive"))
      (node (ref "JP104") (pin "8") (pinfunction "8_8") (pintype "passive"))
    )
    (net (code "14") (name "B5C") (class "Default")
      (node (ref "IC2") (pin "B5") (pinfunction "B5_B5") (pintype "bidirectional"))
      (node (ref "IC2") (pin "B5_1") (pinfunction "B5_B5_1") (pintype "bidirectional"))
      (node (ref "JP103") (pin "1") (pinfunction "1_1") (pintype "passive"))
      (node (ref "JP103") (pin "2") (pinfunction "2_2") (pintype "passive"))
      (node (ref "JP103") (pin "3") (pinfunction "3_3") (pintype "passive"))
      (node (ref "JP103") (pin "4") (pinfunction "4_4") (pintype "passive"))
      (node (ref "JP103") (pin "5") (pinfunction "5_5") (pintype "passive"))
      (node (ref "JP103") (pin "6") (pinfunction "6_6") (pintype "passive"))
      (node (ref "JP103") (pin "7") (pinfunction "7_7") (pintype "passive"))
      (node (ref "JP103") (pin "8") (pinfunction "8_8") (pintype "passive"))
    )
    (net (code "15") (name "C0C") (class "Default")
      (node (ref "IC2") (pin "C0") (pinfunction "C0_C0") (pintype "bidirectional"))
      (node (ref "IC2") (pin "C0_1") (pinfunction "C0_C0_1") (pintype "bidirectional"))
      (node (ref "JP29") (pin "1") (pinfunction "1_1") (pintype "passive"))
      (node (ref "JP29") (pin "2") (pinfunction "2_2") (pintype "passive"))
      (node (ref "JP29") (pin "3") (pinfunction "3_3") (pintype "passive"))
      (node (ref "JP29") (pin "4") (pinfunction "4_4") (pintype "passive"))
      (node (ref "JP29") (pin "5") (pinfunction "5_5") (pintype "passive"))
      (node (ref "JP29") (pin "6") (pinfunction "6_6") (pintype "passive"))
      (node (ref "JP29") (pin "7") (pinfunction "7_7") (pintype "passive"))
      (node (ref "JP29") (pin "8") (pinfunction "8_8") (pintype "passive"))
      (node (ref "R28") (pin "1") (pinfunction "1_1") (pintype "passive"))
    )
    (net (code "16") (name "C1C") (class "Default")
      (node (ref "IC2") (pin "C1") (pinfunction "C1_C1") (pintype "bidirectional"))
      (node (ref "IC2") (pin "C1_1") (pinfunction "C1_C1_1") (pintype "bidirectional"))
      (node (ref "JP28") (pin "1") (pinfunction "1_1") (pintype "passive"))
      (node (ref "JP28") (pin "2") (pinfunction "2_2") (pintype "passive"))
      (node (ref "JP28") (pin "3") (pinfunction "3_3") (pintype "passive"))
      (node (ref "JP28") (pin "4") (pinfunction "4_4") (pintype "passive"))
      (node (ref "JP28") (pin "5") (pinfunction "5_5") (pintype "passive"))
      (node (ref "JP28") (pin "6") (pinfunction "6_6") (pintype "passive"))
      (node (ref "JP28") (pin "7") (pinfunction "7_7") (pintype "passive"))
      (node (ref "JP28") (pin "8") (pinfunction "8_8") (pintype "passive"))
      (node (ref "R26") (pin "1") (pinfunction "1_1") (pintype "passive"))
    )
    (net (code "17") (name "C2C") (class "Default")
      (node (ref "IC2") (pin "C2") (pinfunction "C2_C2") (pintype "bidirectional"))
      (node (ref "IC2") (pin "C2_1") (pinfunction "C2_C2_1") (pintype "bidirectional"))
      (node (ref "JP27") (pin "1") (pinfunction "1_1") (pintype "passive"))
      (node (ref "JP27") (pin "2") (pinfunction "2_2") (pintype "passive"))
      (node (ref "JP27") (pin "3") (pinfunction "3_3") (pintype "passive"))
      (node (ref "JP27") (pin "4") (pinfunction "4_4") (pintype "passive"))
      (node (ref "JP27") (pin "5") (pinfunction "5_5") (pintype "passive"))
      (node (ref "JP27") (pin "6") (pinfunction "6_6") (pintype "passive"))
      (node (ref "JP27") (pin "7") (pinfunction "7_7") (pintype "passive"))
      (node (ref "JP27") (pin "8") (pinfunction "8_8") (pintype "passive"))
      (node (ref "R24") (pin "1") (pinfunction "1_1") (pintype "passive"))
    )
    (net (code "18") (name "C3C") (class "Default")
      (node (ref "IC2") (pin "C3") (pinfunction "C3_C3") (pintype "bidirectional"))
      (node (ref "IC2") (pin "C3_1") (pinfunction "C3_C3_1") (pintype "bidirectional"))
      (node (ref "JP26") (pin "1") (pinfunction "1_1") (pintype "passive"))
      (node (ref "JP26") (pin "2") (pinfunction "2_2") (pintype "passive"))
      (node (ref "JP26") (pin "3") (pinfunction "3_3") (pintype "passive"))
      (node (ref "JP26") (pin "4") (pinfunction "4_4") (pintype "passive"))
      (node (ref "JP26") (pin "5") (pinfunction "5_5") (pintype "passive"))
      (node (ref "JP26") (pin "6") (pinfunction "6_6") (pintype "passive"))
      (node (ref "JP26") (pin "7") (pinfunction "7_7") (pintype "passive"))
      (node (ref "JP26") (pin "8") (pinfunction "8_8") (pintype "passive"))
      (node (ref "R22") (pin "1") (pinfunction "1_1") (pintype "passive"))
    )
    (net (code "19") (name "C4C") (class "Default")
      (node (ref "IC2") (pin "C4") (pinfunction "C4_C4") (pintype "bidirectional"))
      (node (ref "IC2") (pin "C4_1") (pinfunction "C4_C4_1") (pintype "bidirectional"))
      (node (ref "JP25") (pin "1") (pinfunction "1_1") (pintype "passive"))
      (node (ref "JP25") (pin "2") (pinfunction "2_2") (pintype "passive"))
      (node (ref "JP25") (pin "3") (pinfunction "3_3") (pintype "passive"))
      (node (ref "JP25") (pin "4") (pinfunction "4_4") (pintype "passive"))
      (node (ref "JP25") (pin "5") (pinfunction "5_5") (pintype "passive"))
      (node (ref "JP25") (pin "6") (pinfunction "6_6") (pintype "passive"))
      (node (ref "JP25") (pin "7") (pinfunction "7_7") (pintype "passive"))
      (node (ref "JP25") (pin "8") (pinfunction "8_8") (pintype "passive"))
      (node (ref "R20") (pin "1") (pinfunction "1_1") (pintype "passive"))
      (node (ref "R65") (pin "1") (pinfunction "1_1") (pintype "passive"))
    )
    (net (code "20") (name "C5C") (class "Default")
      (node (ref "IC2") (pin "C5") (pinfunction "C5_C5") (pintype "bidirectional"))
      (node (ref "IC2") (pin "C5_1") (pinfunction "C5_C5_1") (pintype "bidirectional"))
      (node (ref "JP24") (pin "1") (pinfunction "1_1") (pintype "passive"))
      (node (ref "JP24") (pin "2") (pinfunction "2_2") (pintype "passive"))
      (node (ref "JP24") (pin "3") (pinfunction "3_3") (pintype "passive"))
      (node (ref "JP24") (pin "4") (pinfunction "4_4") (pintype "passive"))
      (node (ref "JP24") (pin "5") (pinfunction "5_5") (pintype "passive"))
      (node (ref "JP24") (pin "6") (pinfunction "6_6") (pintype "passive"))
      (node (ref "JP24") (pin "7") (pinfunction "7_7") (pintype "passive"))
      (node (ref "JP24") (pin "8") (pinfunction "8_8") (pintype "passive"))
      (node (ref "R18") (pin "1") (pinfunction "1_1") (pintype "passive"))
      (node (ref "R64") (pin "1") (pinfunction "1_1") (pintype "passive"))
    )
    (net (code "21") (name "D0C") (class "Default")
      (node (ref "IC2") (pin "D0") (pinfunction "D0_D0") (pintype "bidirectional"))
      (node (ref "IC2") (pin "D0_1") (pinfunction "D0_D0_1") (pintype "bidirectional"))
      (node (ref "JP22") (pin "1") (pinfunction "1_1") (pintype "passive"))
      (node (ref "JP22") (pin "2") (pinfunction "2_2") (pintype "passive"))
      (node (ref "JP22") (pin "3") (pinfunction "3_3") (pintype "passive"))
      (node (ref "JP22") (pin "4") (pinfunction "4_4") (pintype "passive"))
      (node (ref "JP22") (pin "5") (pinfunction "5_5") (pintype "passive"))
      (node (ref "JP22") (pin "6") (pinfunction "6_6") (pintype "passive"))
      (node (ref "JP22") (pin "7") (pinfunction "7_7") (pintype "passive"))
      (node (ref "JP22") (pin "8") (pinfunction "8_8") (pintype "passive"))
      (node (ref "R16") (pin "1") (pinfunction "1_1") (pintype "passive"))
      (node (ref "R62") (pin "1") (pinfunction "1_1") (pintype "passive"))
    )
    (net (code "22") (name "D1C") (class "Default")
      (node (ref "IC2") (pin "D1") (pinfunction "D1_D1") (pintype "bidirectional"))
      (node (ref "IC2") (pin "D1_1") (pinfunction "D1_D1_1") (pintype "bidirectional"))
      (node (ref "JP21") (pin "1") (pinfunction "1_1") (pintype "passive"))
      (node (ref "JP21") (pin "2") (pinfunction "2_2") (pintype "passive"))
      (node (ref "JP21") (pin "3") (pinfunction "3_3") (pintype "passive"))
      (node (ref "JP21") (pin "4") (pinfunction "4_4") (pintype "passive"))
      (node (ref "JP21") (pin "5") (pinfunction "5_5") (pintype "passive"))
      (node (ref "JP21") (pin "6") (pinfunction "6_6") (pintype "passive"))
      (node (ref "JP21") (pin "7") (pinfunction "7_7") (pintype "passive"))
      (node (ref "JP21") (pin "8") (pinfunction "8_8") (pintype "passive"))
      (node (ref "R14") (pin "1") (pinfunction "1_1") (pintype "passive"))
      (node (ref "R63") (pin "1") (pinfunction "1_1") (pintype "passive"))
    )
    (net (code "23") (name "D2C") (class "Default")
      (node (ref "IC2") (pin "D2") (pinfunction "D2_D2") (pintype "bidirectional"))
      (node (ref "IC2") (pin "D2_1") (pinfunction "D2_D2_1") (pintype "bidirectional"))
      (node (ref "JP20") (pin "1") (pinfunction "1_1") (pintype "passive"))
      (node (ref "JP20") (pin "2") (pinfunction "2_2") (pintype "passive"))
      (node (ref "JP20") (pin "3") (pinfunction "3_3") (pintype "passive"))
      (node (ref "JP20") (pin "4") (pinfunction "4_4") (pintype "passive"))
      (node (ref "JP20") (pin "5") (pinfunction "5_5") (pintype "passive"))
      (node (ref "JP20") (pin "6") (pinfunction "6_6") (pintype "passive"))
      (node (ref "JP20") (pin "7") (pinfunction "7_7") (pintype "passive"))
      (node (ref "JP20") (pin "8") (pinfunction "8_8") (pintype "passive"))
      (node (ref "R12") (pin "1") (pinfunction "1_1") (pintype "passive"))
    )
    (net (code "24") (name "D3C") (class "Default")
      (node (ref "IC2") (pin "D3") (pinfunction "D3_D3") (pintype "bidirectional"))
      (node (ref "IC2") (pin "D3_1") (pinfunction "D3_D3_1") (pintype "bidirectional"))
      (node (ref "JP19") (pin "1") (pinfunction "1_1") (pintype "passive"))
      (node (ref "JP19") (pin "2") (pinfunction "2_2") (pintype "passive"))
      (node (ref "JP19") (pin "3") (pinfunction "3_3") (pintype "passive"))
      (node (ref "JP19") (pin "4") (pinfunction "4_4") (pintype "passive"))
      (node (ref "JP19") (pin "5") (pinfunction "5_5") (pintype "passive"))
      (node (ref "JP19") (pin "6") (pinfunction "6_6") (pintype "passive"))
      (node (ref "JP19") (pin "7") (pinfunction "7_7") (pintype "passive"))
      (node (ref "JP19") (pin "8") (pinfunction "8_8") (pintype "passive"))
      (node (ref "R10") (pin "1") (pinfunction "1_1") (pintype "passive"))
    )
    (net (code "25") (name "D4C") (class "Default")
      (node (ref "IC2") (pin "D4") (pinfunction "D4_D4") (pintype "bidirectional"))
      (node (ref "IC2") (pin "D4_1") (pinfunction "D4_D4_1") (pintype "bidirectional"))
      (node (ref "JP18") (pin "1") (pinfunction "1_1") (pintype "passive"))
      (node (ref "JP18") (pin "2") (pinfunction "2_2") (pintype "passive"))
      (node (ref "JP18") (pin "3") (pinfunction "3_3") (pintype "passive"))
      (node (ref "JP18") (pin "4") (pinfunction "4_4") (pintype "passive"))
      (node (ref "JP18") (pin "5") (pinfunction "5_5") (pintype "passive"))
      (node (ref "JP18") (pin "6") (pinfunction "6_6") (pintype "passive"))
      (node (ref "JP18") (pin "7") (pinfunction "7_7") (pintype "passive"))
      (node (ref "JP18") (pin "8") (pinfunction "8_8") (pintype "passive"))
      (node (ref "R8") (pin "2") (pinfunction "2_2") (pintype "passive"))
    )
    (net (code "26") (name "D5C") (class "Default")
      (node (ref "IC2") (pin "D5") (pinfunction "D5_D5") (pintype "bidirectional"))
      (node (ref "IC2") (pin "D5_1") (pinfunction "D5_D5_1") (pintype "bidirectional"))
      (node (ref "JP10") (pin "1") (pinfunction "1_1") (pintype "passive"))
      (node (ref "JP10") (pin "2") (pinfunction "2_2") (pintype "passive"))
      (node (ref "JP10") (pin "3") (pinfunction "3_3") (pintype "passive"))
      (node (ref "JP10") (pin "4") (pinfunction "4_4") (pintype "passive"))
      (node (ref "JP10") (pin "5") (pinfunction "5_5") (pintype "passive"))
      (node (ref "JP10") (pin "6") (pinfunction "6_6") (pintype "passive"))
      (node (ref "JP10") (pin "7") (pinfunction "7_7") (pintype "passive"))
      (node (ref "JP10") (pin "8") (pinfunction "8_8") (pintype "passive"))
      (node (ref "R6") (pin "2") (pinfunction "2_2") (pintype "passive"))
    )
    (net (code "27") (name "D6C") (class "Default")
      (node (ref "IC2") (pin "D6") (pinfunction "D6_D6") (pintype "bidirectional"))
      (node (ref "IC2") (pin "D6_1") (pinfunction "D6_D6_1") (pintype "bidirectional"))
      (node (ref "JP7") (pin "1") (pinfunction "1_1") (pintype "passive"))
      (node (ref "JP7") (pin "2") (pinfunction "2_2") (pintype "passive"))
      (node (ref "JP7") (pin "3") (pinfunction "3_3") (pintype "passive"))
      (node (ref "JP7") (pin "4") (pinfunction "4_4") (pintype "passive"))
      (node (ref "JP7") (pin "5") (pinfunction "5_5") (pintype "passive"))
      (node (ref "JP7") (pin "6") (pinfunction "6_6") (pintype "passive"))
      (node (ref "JP7") (pin "7") (pinfunction "7_7") (pintype "passive"))
      (node (ref "JP7") (pin "8") (pinfunction "8_8") (pintype "passive"))
      (node (ref "R4") (pin "2") (pinfunction "2_2") (pintype "passive"))
    )
    (net (code "28") (name "D7C") (class "Default")
      (node (ref "IC2") (pin "D7") (pinfunction "D7_D7") (pintype "bidirectional"))
      (node (ref "IC2") (pin "D7_1") (pinfunction "D7_D7_1") (pintype "bidirectional"))
      (node (ref "JP1") (pin "1") (pinfunction "1_1") (pintype "passive"))
      (node (ref "JP1") (pin "2") (pinfunction "2_2") (pintype "passive"))
      (node (ref "JP1") (pin "3") (pinfunction "3_3") (pintype "passive"))
      (node (ref "JP1") (pin "4") (pinfunction "4_4") (pintype "passive"))
      (node (ref "JP1") (pin "5") (pinfunction "5_5") (pintype "passive"))
      (node (ref "JP1") (pin "6") (pinfunction "6_6") (pintype "passive"))
      (node (ref "JP1") (pin "7") (pinfunction "7_7") (pintype "passive"))
      (node (ref "JP1") (pin "8") (pinfunction "8_8") (pintype "passive"))
      (node (ref "R3") (pin "2") (pinfunction "2_2") (pintype "passive"))
    )
    (net (code "29") (name "DACC") (class "Default")
      (node (ref "IC2") (pin "DAC") (pinfunction "DAC_DAC") (pintype "bidirectional"))
      (node (ref "IC2") (pin "DAC_1") (pinfunction "DAC_DAC_1") (pintype "bidirectional"))
      (node (ref "JP15") (pin "1") (pinfunction "1_1") (pintype "passive"))
      (node (ref "JP15") (pin "2") (pinfunction "2_2") (pintype "passive"))
      (node (ref "JP15") (pin "3") (pinfunction "3_3") (pintype "passive"))
      (node (ref "JP15") (pin "4") (pinfunction "4_4") (pintype "passive"))
      (node (ref "JP15") (pin "5") (pinfunction "5_5") (pintype "passive"))
      (node (ref "JP15") (pin "6") (pinfunction "6_6") (pintype "passive"))
      (node (ref "JP15") (pin "7") (pinfunction "7_7") (pintype "passive"))
      (node (ref "JP15") (pin "8") (pinfunction "8_8") (pintype "passive"))
    )
    (net (code "30") (name "GND") (class "Default")
      (node (ref "C1") (pin "2") (pinfunction "2_2") (pintype "passive"))
      (node (ref "C2") (pin "2") (pinfunction "2_2") (pintype "passive"))
      (node (ref "C3") (pin "2") (pinfunction "2_2") (pintype "passive"))
      (node (ref "C4") (pin "2") (pinfunction "2_2") (pintype "passive"))
      (node (ref "C5") (pin "2") (pinfunction "2_2") (pintype "passive"))
      (node (ref "C6") (pin "2") (pinfunction "2_2") (pintype "passive"))
      (node (ref "C7") (pin "2") (pinfunction "2_2") (pintype "passive"))
      (node (ref "D1") (pin "C") (pinfunction "C_C") (pintype "passive"))
      (node (ref "IC1") (pin "GND") (pinfunction "GND_GND") (pintype "input"))
      (node (ref "IC2") (pin "GND") (pinfunction "GND_GND") (pintype "power_in"))
      (node (ref "IC2") (pin "GND@2") (pinfunction "GND_GND@2") (pintype "power_in"))
      (node (ref "IC2") (pin "GND_1") (pinfunction "GND_GND_1") (pintype "power_in"))
      (node (ref "IC2") (pin "GND_1B") (pinfunction "GND_GND_1B") (pintype "power_in"))
      (node (ref "JP109") (pin "1") (pinfunction "1_1") (pintype "passive"))
      (node (ref "JP109") (pin "2") (pinfunction "2_2") (pintype "passive"))
      (node (ref "JP109") (pin "3") (pinfunction "3_3") (pintype "passive"))
      (node (ref "JP109") (pin "4") (pinfunction "4_4") (pintype "passive"))
      (node (ref "JP11") (pin "1") (pinfunction "1_1") (pintype "passive"))
      (node (ref "JP11") (pin "10") (pinfunction "10_10") (pintype "passive"))
      (node (ref "JP11") (pin "2") (pinfunction "2_2") (pintype "passive"))
      (node (ref "JP11") (pin "3") (pinfunction "3_3") (pintype "passive"))
      (node (ref "JP11") (pin "4") (pinfunction "4_4") (pintype "passive"))
      (node (ref "JP11") (pin "5") (pinfunction "5_5") (pintype "passive"))
      (node (ref "JP11") (pin "6") (pinfunction "6_6") (pintype "passive"))
      (node (ref "JP11") (pin "7") (pinfunction "7_7") (pintype "passive"))
      (node (ref "JP11") (pin "8") (pinfunction "8_8") (pintype "passive"))
      (node (ref "JP11") (pin "9") (pinfunction "9_9") (pintype "passive"))
      (node (ref "JP110") (pin "GND") (pinfunction "GND_GND") (pintype "bidirectional"))
      (node (ref "JP110") (pin "GNDBREAK") (pinfunction "GNDBREAK_GNDBREAK") (pintype "bidirectional"))
      (node (ref "JP14") (pin "1") (pinfunction "1_1") (pintype "passive"))
      (node (ref "JP14") (pin "10") (pinfunction "10_10") (pintype "passive"))
      (node (ref "JP14") (pin "11") (pinfunction "11_11") (pintype "passive"))
      (node (ref "JP14") (pin "12") (pinfunction "12_12") (pintype "passive"))
      (node (ref "JP14") (pin "13") (pinfunction "13_13") (pintype "passive"))
      (node (ref "JP14") (pin "14") (pinfunction "14_14") (pintype "passive"))
      (node (ref "JP14") (pin "15") (pinfunction "15_15") (pintype "passive"))
      (node (ref "JP14") (pin "16") (pinfunction "16_16") (pintype "passive"))
      (node (ref "JP14") (pin "2") (pinfunction "2_2") (pintype "passive"))
      (node (ref "JP14") (pin "3") (pinfunction "3_3") (pintype "passive"))
      (node (ref "JP14") (pin "4") (pinfunction "4_4") (pintype "passive"))
      (node (ref "JP14") (pin "5") (pinfunction "5_5") (pintype "passive"))
      (node (ref "JP14") (pin "6") (pinfunction "6_6") (pintype "passive"))
      (node (ref "JP14") (pin "7") (pinfunction "7_7") (pintype "passive"))
      (node (ref "JP14") (pin "8") (pinfunction "8_8") (pintype "passive"))
      (node (ref "JP14") (pin "9") (pinfunction "9_9") (pintype "passive"))
      (node (ref "JP23") (pin "1") (pinfunction "1_1") (pintype "passive"))
      (node (ref "JP23") (pin "2") (pinfunction "2_2") (pintype "passive"))
      (node (ref "JP23") (pin "3") (pinfunction "3_3") (pintype "passive"))
      (node (ref "JP23") (pin "4") (pinfunction "4_4") (pintype "passive"))
      (node (ref "JP23") (pin "5") (pinfunction "5_5") (pintype "passive"))
      (node (ref "JP23") (pin "6") (pinfunction "6_6") (pintype "passive"))
      (node (ref "JP23") (pin "7") (pinfunction "7_7") (pintype "passive"))
      (node (ref "JP23") (pin "8") (pinfunction "8_8") (pintype "passive"))
      (node (ref "JP32") (pin "1") (pinfunction "1_1") (pintype "passive"))
      (node (ref "JP32") (pin "2") (pinfunction "2_2") (pintype "passive"))
      (node (ref "JP33") (pin "1") (pinfunction "1_1") (pintype "passive"))
      (node (ref "JP4") (pin "1") (pinfunction "1_1") (pintype "passive"))
    )
    (net (code "31") (name "LED_COMMON") (class "Default")
      (node (ref "JP30") (pin "1") (pinfunction "1_1") (pintype "passive"))
      (node (ref "R11") (pin "2") (pinfunction "2_2") (pintype "passive"))
      (node (ref "R13") (pin "2") (pinfunction "2_2") (pintype "passive"))
      (node (ref "R15") (pin "2") (pinfunction "2_2") (pintype "passive"))
      (node (ref "R17") (pin "2") (pinfunction "2_2") (pintype "passive"))
      (node (ref "R19") (pin "2") (pinfunction "2_2") (pintype "passive"))
      (node (ref "R2") (pin "1") (pinfunction "1_1") (pintype "passive"))
      (node (ref "R21") (pin "2") (pinfunction "2_2") (pintype "passive"))
      (node (ref "R23") (pin "2") (pinfunction "2_2") (pintype "passive"))
      (node (ref "R25") (pin "1") (pinfunction "1_1") (pintype "passive"))
      (node (ref "R27") (pin "1") (pinfunction "1_1") (pintype "passive"))
      (node (ref "R29") (pin "1") (pinfunction "1_1") (pintype "passive"))
      (node (ref "R5") (pin "1") (pinfunction "1_1") (pintype "passive"))
      (node (ref "R7") (pin "1") (pinfunction "1_1") (pintype "passive"))
      (node (ref "R9") (pin "1") (pinfunction "1_1") (pintype "passive"))
    )
    (net (code "32") (name "Net-(D1-PadA)") (class "Default")
      (node (ref "D1") (pin "A") (pinfunction "A_A") (pintype "passive"))
      (node (ref "R1") (pin "1") (pinfunction "1_1") (pintype "passive"))
    )
    (net (code "33") (name "Net-(IC2-PadVBAT)") (class "Default")
      (node (ref "IC2") (pin "VBAT") (pinfunction "VBAT_VBAT") (pintype "passive"))
      (node (ref "IC2") (pin "VBATT_1") (pinfunction "VBAT_VBATT_1") (pintype "passive"))
    )
    (net (code "34") (name "Net-(IC2-~{RST}-PadRST)") (class "Default")
      (node (ref "IC2") (pin "RST") (pinfunction "~{RST}_RST") (pintype "bidirectional"))
      (node (ref "IC2") (pin "RST_1") (pinfunction "~{RST}_RST_1") (pintype "bidirectional"))
    )
    (net (code "35") (name "Net-(JP31-Pad1)") (class "Default")
      (node (ref "JP31") (pin "1") (pinfunction "1_1") (pintype "passive"))
      (node (ref "JP31") (pin "2") (pinfunction "2_2") (pintype "passive"))
      (node (ref "R31") (pin "2") (pinfunction "2_2") (pintype "passive"))
    )
    (net (code "36") (name "Net-(JP34-Pad1)") (class "Default")
      (node (ref "JP34") (pin "1") (pinfunction "1_1") (pintype "passive"))
      (node (ref "JP34") (pin "2") (pinfunction "2_2") (pintype "passive"))
      (node (ref "R48") (pin "2") (pinfunction "2_2") (pintype "passive"))
    )
    (net (code "37") (name "Net-(JP35-Pad1)") (class "Default")
      (node (ref "JP35") (pin "1") (pinfunction "1_1") (pintype "passive"))
      (node (ref "R37") (pin "1") (pinfunction "1_1") (pintype "passive"))
    )
    (net (code "38") (name "Net-(JP36-Pad1)") (class "Default")
      (node (ref "JP36") (pin "1") (pinfunction "1_1") (pintype "passive"))
      (node (ref "R30") (pin "1") (pinfunction "1_1") (pintype "passive"))
    )
    (net (code "39") (name "Net-(JP37-Pad1)") (class "Default")
      (node (ref "JP37") (pin "1") (pinfunction "1_1") (pintype "passive"))
      (node (ref "R46") (pin "1") (pinfunction "1_1") (pintype "passive"))
    )
    (net (code "40") (name "Net-(JP38-Pad1)") (class "Default")
      (node (ref "JP38") (pin "1") (pinfunction "1_1") (pintype "passive"))
      (node (ref "JP38") (pin "2") (pinfunction "2_2") (pintype "passive"))
      (node (ref "R32") (pin "2") (pinfunction "2_2") (pintype "passive"))
    )
    (net (code "41") (name "Net-(JP39-Pad1)") (class "Default")
      (node (ref "JP39") (pin "1") (pinfunction "1_1") (pintype "passive"))
      (node (ref "JP39") (pin "2") (pinfunction "2_2") (pintype "passive"))
      (node (ref "R49") (pin "2") (pinfunction "2_2") (pintype "passive"))
    )
    (net (code "42") (name "Net-(JP40-Pad1)") (class "Default")
      (node (ref "JP40") (pin "1") (pinfunction "1_1") (pintype "passive"))
      (node (ref "R31") (pin "1") (pinfunction "1_1") (pintype "passive"))
    )
    (net (code "43") (name "Net-(JP41-Pad1)") (class "Default")
      (node (ref "JP41") (pin "1") (pinfunction "1_1") (pintype "passive"))
      (node (ref "R32") (pin "1") (pinfunction "1_1") (pintype "passive"))
    )
    (net (code "44") (name "Net-(JP42-Pad1)") (class "Default")
      (node (ref "JP42") (pin "1") (pinfunction "1_1") (pintype "passive"))
      (node (ref "R33") (pin "1") (pinfunction "1_1") (pintype "passive"))
    )
    (net (code "45") (name "Net-(JP43-Pad1)") (class "Default")
      (node (ref "JP43") (pin "1") (pinfunction "1_1") (pintype "passive"))
      (node (ref "R34") (pin "1") (pinfunction "1_1") (pintype "passive"))
    )
    (net (code "46") (name "Net-(JP44-Pad1)") (class "Default")
      (node (ref "JP44") (pin "1") (pinfunction "1_1") (pintype "passive"))
      (node (ref "R35") (pin "1") (pinfunction "1_1") (pintype "passive"))
    )
    (net (code "47") (name "Net-(JP45-Pad1)") (class "Default")
      (node (ref "JP45") (pin "1") (pinfunction "1_1") (pintype "passive"))
      (node (ref "R36") (pin "1") (pinfunction "1_1") (pintype "passive"))
    )
    (net (code "48") (name "Net-(JP46-Pad1)") (class "Default")
      (node (ref "JP46") (pin "1") (pinfunction "1_1") (pintype "passive"))
      (node (ref "R38") (pin "1") (pinfunction "1_1") (pintype "passive"))
    )
    (net (code "49") (name "Net-(JP47-Pad1)") (class "Default")
      (node (ref "JP47") (pin "1") (pinfunction "1_1") (pintype "passive"))
      (node (ref "R39") (pin "1") (pinfunction "1_1") (pintype "passive"))
    )
    (net (code "50") (name "Net-(JP48-Pad1)") (class "Default")
      (node (ref "JP48") (pin "1") (pinfunction "1_1") (pintype "passive"))
      (node (ref "R40") (pin "1") (pinfunction "1_1") (pintype "passive"))
    )
    (net (code "51") (name "Net-(JP49-Pad1)") (class "Default")
      (node (ref "JP49") (pin "1") (pinfunction "1_1") (pintype "passive"))
      (node (ref "R41") (pin "1") (pinfunction "1_1") (pintype "passive"))
    )
    (net (code "52") (name "Net-(JP50-Pad1)") (class "Default")
      (node (ref "JP50") (pin "1") (pinfunction "1_1") (pintype "passive"))
      (node (ref "R42") (pin "1") (pinfunction "1_1") (pintype "passive"))
    )
    (net (code "53") (name "Net-(JP51-Pad1)") (class "Default")
      (node (ref "JP51") (pin "1") (pinfunction "1_1") (pintype "passive"))
      (node (ref "R43") (pin "1") (pinfunction "1_1") (pintype "passive"))
    )
    (net (code "54") (name "Net-(JP52-Pad1)") (class "Default")
      (node (ref "JP52") (pin "1") (pinfunction "1_1") (pintype "passive"))
      (node (ref "R44") (pin "1") (pinfunction "1_1") (pintype "passive"))
    )
    (net (code "55") (name "Net-(JP53-Pad1)") (class "Default")
      (node (ref "JP53") (pin "1") (pinfunction "1_1") (pintype "passive"))
      (node (ref "R45") (pin "1") (pinfunction "1_1") (pintype "passive"))
    )
    (net (code "56") (name "Net-(JP55-Pad1)") (class "Default")
      (node (ref "JP55") (pin "1") (pinfunction "1_1") (pintype "passive"))
      (node (ref "JP55") (pin "2") (pinfunction "2_2") (pintype "passive"))
      (node (ref "R30") (pin "2") (pinfunction "2_2") (pintype "passive"))
    )
    (net (code "57") (name "Net-(JP56-Pad1)") (class "Default")
      (node (ref "JP56") (pin "1") (pinfunction "1_1") (pintype "passive"))
      (node (ref "R47") (pin "1") (pinfunction "1_1") (pintype "passive"))
    )
    (net (code "58") (name "Net-(JP57-Pad1)") (class "Default")
      (node (ref "JP57") (pin "1") (pinfunction "1_1") (pintype "passive"))
      (node (ref "R48") (pin "1") (pinfunction "1_1") (pintype "passive"))
    )
    (net (code "59") (name "Net-(JP58-Pad1)") (class "Default")
      (node (ref "JP58") (pin "1") (pinfunction "1_1") (pintype "passive"))
      (node (ref "R49") (pin "1") (pinfunction "1_1") (pintype "passive"))
    )
    (net (code "60") (name "Net-(JP59-Pad1)") (class "Default")
      (node (ref "JP59") (pin "1") (pinfunction "1_1") (pintype "passive"))
      (node (ref "R50") (pin "1") (pinfunction "1_1") (pintype "passive"))
    )
    (net (code "61") (name "Net-(JP60-Pad1)") (class "Default")
      (node (ref "JP60") (pin "1") (pinfunction "1_1") (pintype "passive"))
      (node (ref "R51") (pin "1") (pinfunction "1_1") (pintype "passive"))
    )
    (net (code "62") (name "Net-(JP61-Pad1)") (class "Default")
      (node (ref "JP61") (pin "1") (pinfunction "1_1") (pintype "passive"))
      (node (ref "R52") (pin "1") (pinfunction "1_1") (pintype "passive"))
    )
    (net (code "63") (name "Net-(JP62-Pad1)") (class "Default")
      (node (ref "JP62") (pin "1") (pinfunction "1_1") (pintype "passive"))
      (node (ref "R53") (pin "1") (pinfunction "1_1") (pintype "passive"))
    )
    (net (code "64") (name "Net-(JP63-Pad1)") (class "Default")
      (node (ref "JP63") (pin "1") (pinfunction "1_1") (pintype "passive"))
      (node (ref "R54") (pin "1") (pinfunction "1_1") (pintype "passive"))
    )
    (net (code "65") (name "Net-(JP64-Pad1)") (class "Default")
      (node (ref "JP64") (pin "1") (pinfunction "1_1") (pintype "passive"))
      (node (ref "R55") (pin "1") (pinfunction "1_1") (pintype "passive"))
    )
    (net (code "66") (name "Net-(JP65-Pad1)") (class "Default")
      (node (ref "JP65") (pin "1") (pinfunction "1_1") (pintype "passive"))
      (node (ref "R56") (pin "1") (pinfunction "1_1") (pintype "passive"))
    )
    (net (code "67") (name "Net-(JP66-Pad1)") (class "Default")
      (node (ref "JP66") (pin "1") (pinfunction "1_1") (pintype "passive"))
      (node (ref "R57") (pin "1") (pinfunction "1_1") (pintype "passive"))
    )
    (net (code "68") (name "Net-(JP67-Pad1)") (class "Default")
      (node (ref "JP67") (pin "1") (pinfunction "1_1") (pintype "passive"))
      (node (ref "R58") (pin "1") (pinfunction "1_1") (pintype "passive"))
    )
    (net (code "69") (name "Net-(JP68-Pad1)") (class "Default")
      (node (ref "JP68") (pin "1") (pinfunction "1_1") (pintype "passive"))
      (node (ref "R59") (pin "1") (pinfunction "1_1") (pintype "passive"))
    )
    (net (code "70") (name "Net-(JP69-Pad1)") (class "Default")
      (node (ref "JP69") (pin "1") (pinfunction "1_1") (pintype "passive"))
      (node (ref "R60") (pin "1") (pinfunction "1_1") (pintype "passive"))
    )
    (net (code "71") (name "Net-(JP70-Pad1)") (class "Default")
      (node (ref "JP70") (pin "1") (pinfunction "1_1") (pintype "passive"))
      (node (ref "R61") (pin "1") (pinfunction "1_1") (pintype "passive"))
    )
    (net (code "72") (name "Net-(JP71-Pad1)") (class "Default")
      (node (ref "JP71") (pin "1") (pinfunction "1_1") (pintype "passive"))
      (node (ref "JP71") (pin "2") (pinfunction "2_2") (pintype "passive"))
      (node (ref "R46") (pin "2") (pinfunction "2_2") (pintype "passive"))
    )
    (net (code "73") (name "Net-(JP72-Pad1)") (class "Default")
      (node (ref "JP72") (pin "1") (pinfunction "1_1") (pintype "passive"))
      (node (ref "JP72") (pin "2") (pinfunction "2_2") (pintype "passive"))
      (node (ref "R47") (pin "2") (pinfunction "2_2") (pintype "passive"))
    )
    (net (code "74") (name "Net-(JP73-Pad1)") (class "Default")
      (node (ref "JP73") (pin "1") (pinfunction "1_1") (pintype "passive"))
      (node (ref "JP73") (pin "2") (pinfunction "2_2") (pintype "passive"))
      (node (ref "R50") (pin "2") (pinfunction "2_2") (pintype "passive"))
    )
    (net (code "75") (name "Net-(JP74-Pad1)") (class "Default")
      (node (ref "JP74") (pin "1") (pinfunction "1_1") (pintype "passive"))
      (node (ref "JP74") (pin "2") (pinfunction "2_2") (pintype "passive"))
      (node (ref "R51") (pin "2") (pinfunction "2_2") (pintype "passive"))
    )
    (net (code "76") (name "Net-(JP75-Pad1)") (class "Default")
      (node (ref "JP75") (pin "1") (pinfunction "1_1") (pintype "passive"))
      (node (ref "JP75") (pin "2") (pinfunction "2_2") (pintype "passive"))
      (node (ref "R52") (pin "2") (pinfunction "2_2") (pintype "passive"))
    )
    (net (code "77") (name "Net-(JP76-Pad1)") (class "Default")
      (node (ref "JP76") (pin "1") (pinfunction "1_1") (pintype "passive"))
      (node (ref "JP76") (pin "2") (pinfunction "2_2") (pintype "passive"))
      (node (ref "R53") (pin "2") (pinfunction "2_2") (pintype "passive"))
    )
    (net (code "78") (name "Net-(JP77-Pad1)") (class "Default")
      (node (ref "JP77") (pin "1") (pinfunction "1_1") (pintype "passive"))
      (node (ref "JP77") (pin "2") (pinfunction "2_2") (pintype "passive"))
      (node (ref "R54") (pin "2") (pinfunction "2_2") (pintype "passive"))
    )
    (net (code "79") (name "Net-(JP78-Pad1)") (class "Default")
      (node (ref "JP78") (pin "1") (pinfunction "1_1") (pintype "passive"))
      (node (ref "JP78") (pin "2") (pinfunction "2_2") (pintype "passive"))
      (node (ref "R55") (pin "2") (pinfunction "2_2") (pintype "passive"))
    )
    (net (code "80") (name "Net-(JP79-Pad1)") (class "Default")
      (node (ref "JP79") (pin "1") (pinfunction "1_1") (pintype "passive"))
      (node (ref "JP79") (pin "2") (pinfunction "2_2") (pintype "passive"))
      (node (ref "R56") (pin "2") (pinfunction "2_2") (pintype "passive"))
    )
    (net (code "81") (name "Net-(JP80-Pad1)") (class "Default")
      (node (ref "JP80") (pin "1") (pinfunction "1_1") (pintype "passive"))
      (node (ref "JP80") (pin "2") (pinfunction "2_2") (pintype "passive"))
      (node (ref "R57") (pin "2") (pinfunction "2_2") (pintype "passive"))
    )
    (net (code "82") (name "Net-(JP81-Pad1)") (class "Default")
      (node (ref "JP81") (pin "1") (pinfunction "1_1") (pintype "passive"))
      (node (ref "JP81") (pin "2") (pinfunction "2_2") (pintype "passive"))
      (node (ref "R58") (pin "2") (pinfunction "2_2") (pintype "passive"))
    )
    (net (code "83") (name "Net-(JP82-Pad1)") (class "Default")
      (node (ref "JP82") (pin "1") (pinfunction "1_1") (pintype "passive"))
      (node (ref "JP82") (pin "2") (pinfunction "2_2") (pintype "passive"))
      (node (ref "R59") (pin "2") (pinfunction "2_2") (pintype "passive"))
    )
    (net (code "84") (name "Net-(JP83-Pad1)") (class "Default")
      (node (ref "JP83") (pin "1") (pinfunction "1_1") (pintype "passive"))
      (node (ref "JP83") (pin "2") (pinfunction "2_2") (pintype "passive"))
      (node (ref "R60") (pin "2") (pinfunction "2_2") (pintype "passive"))
    )
    (net (code "85") (name "Net-(JP84-Pad1)") (class "Default")
      (node (ref "JP84") (pin "1") (pinfunction "1_1") (pintype "passive"))
      (node (ref "JP84") (pin "2") (pinfunction "2_2") (pintype "passive"))
      (node (ref "R61") (pin "2") (pinfunction "2_2") (pintype "passive"))
    )
    (net (code "86") (name "Net-(JP85-Pad1)") (class "Default")
      (node (ref "JP85") (pin "1") (pinfunction "1_1") (pintype "passive"))
      (node (ref "JP85") (pin "2") (pinfunction "2_2") (pintype "passive"))
      (node (ref "R33") (pin "2") (pinfunction "2_2") (pintype "passive"))
    )
    (net (code "87") (name "Net-(JP86-Pad1)") (class "Default")
      (node (ref "JP86") (pin "1") (pinfunction "1_1") (pintype "passive"))
      (node (ref "JP86") (pin "2") (pinfunction "2_2") (pintype "passive"))
      (node (ref "R34") (pin "2") (pinfunction "2_2") (pintype "passive"))
    )
    (net (code "88") (name "Net-(JP87-Pad1)") (class "Default")
      (node (ref "JP87") (pin "1") (pinfunction "1_1") (pintype "passive"))
      (node (ref "JP87") (pin "2") (pinfunction "2_2") (pintype "passive"))
      (node (ref "R35") (pin "2") (pinfunction "2_2") (pintype "passive"))
    )
    (net (code "89") (name "Net-(JP88-Pad1)") (class "Default")
      (node (ref "JP88") (pin "1") (pinfunction "1_1") (pintype "passive"))
      (node (ref "JP88") (pin "2") (pinfunction "2_2") (pintype "passive"))
      (node (ref "R36") (pin "2") (pinfunction "2_2") (pintype "passive"))
    )
    (net (code "90") (name "Net-(JP89-Pad1)") (class "Default")
      (node (ref "JP89") (pin "1") (pinfunction "1_1") (pintype "passive"))
      (node (ref "JP89") (pin "2") (pinfunction "2_2") (pintype "passive"))
      (node (ref "R37") (pin "2") (pinfunction "2_2") (pintype "passive"))
    )
    (net (code "91") (name "Net-(JP90-Pad1)") (class "Default")
      (node (ref "JP90") (pin "1") (pinfunction "1_1") (pintype "passive"))
      (node (ref "JP90") (pin "2") (pinfunction "2_2") (pintype "passive"))
      (node (ref "R38") (pin "2") (pinfunction "2_2") (pintype "passive"))
    )
    (net (code "92") (name "Net-(JP91-Pad1)") (class "Default")
      (node (ref "JP91") (pin "1") (pinfunction "1_1") (pintype "passive"))
      (node (ref "JP91") (pin "2") (pinfunction "2_2") (pintype "passive"))
      (node (ref "R39") (pin "2") (pinfunction "2_2") (pintype "passive"))
    )
    (net (code "93") (name "Net-(JP92-Pad1)") (class "Default")
      (node (ref "JP92") (pin "1") (pinfunction "1_1") (pintype "passive"))
      (node (ref "JP92") (pin "2") (pinfunction "2_2") (pintype "passive"))
      (node (ref "R40") (pin "2") (pinfunction "2_2") (pintype "passive"))
    )
    (net (code "94") (name "Net-(JP93-Pad1)") (class "Default")
      (node (ref "JP93") (pin "1") (pinfunction "1_1") (pintype "passive"))
      (node (ref "JP93") (pin "2") (pinfunction "2_2") (pintype "passive"))
      (node (ref "R41") (pin "2") (pinfunction "2_2") (pintype "passive"))
    )
    (net (code "95") (name "Net-(JP94-Pad1)") (class "Default")
      (node (ref "JP94") (pin "1") (pinfunction "1_1") (pintype "passive"))
      (node (ref "JP94") (pin "2") (pinfunction "2_2") (pintype "passive"))
      (node (ref "R42") (pin "2") (pinfunction "2_2") (pintype "passive"))
    )
    (net (code "96") (name "Net-(JP95-Pad1)") (class "Default")
      (node (ref "JP95") (pin "1") (pinfunction "1_1") (pintype "passive"))
      (node (ref "JP95") (pin "2") (pinfunction "2_2") (pintype "passive"))
      (node (ref "R43") (pin "2") (pinfunction "2_2") (pintype "passive"))
    )
    (net (code "97") (name "Net-(JP96-Pad1)") (class "Default")
      (node (ref "JP96") (pin "1") (pinfunction "1_1") (pintype "passive"))
      (node (ref "JP96") (pin "2") (pinfunction "2_2") (pintype "passive"))
      (node (ref "R44") (pin "2") (pinfunction "2_2") (pintype "passive"))
    )
    (net (code "98") (name "Net-(JP97-Pad1)") (class "Default")
      (node (ref "JP97") (pin "1") (pinfunction "1_1") (pintype "passive"))
      (node (ref "JP97") (pin "2") (pinfunction "2_2") (pintype "passive"))
      (node (ref "R45") (pin "2") (pinfunction "2_2") (pintype "passive"))
    )
    (net (code "99") (name "Net-(JP111-Pad1)") (class "Default")
      (node (ref "JP111") (pin "1") (pinfunction "1_1") (pintype "passive"))
      (node (ref "U2") (pin "8") (pinfunction "8_8") (pintype "bidirectional"))
    )
    (net (code "100") (name "Net-(JP111-Pad2)") (class "Default")
      (node (ref "JP111") (pin "2") (pinfunction "2_2") (pintype "passive"))
      (node (ref "U2") (pin "7") (pinfunction "7_7") (pintype "bidirectional"))
    )
    (net (code "101") (name "Net-(JP111-Pad3)") (class "Default")
      (node (ref "JP111") (pin "3") (pinfunction "3_3") (pintype "passive"))
      (node (ref "U2") (pin "6") (pinfunction "6_6") (pintype "bidirectional"))
    )
    (net (code "102") (name "Net-(JP111-Pad4)") (class "Default")
      (node (ref "JP111") (pin "4") (pinfunction "4_4") (pintype "passive"))
      (node (ref "U2") (pin "5") (pinfunction "5_5") (pintype "bidirectional"))
    )
    (net (code "103") (name "Net-(JP112-Pad1)") (class "Default")
      (node (ref "JP112") (pin "1") (pinfunction "1_1") (pintype "passive"))
      (node (ref "U3") (pin "8") (pinfunction "8_8") (pintype "bidirectional"))
    )
    (net (code "104") (name "Net-(JP112-Pad2)") (class "Default")
      (node (ref "JP112") (pin "2") (pinfunction "2_2") (pintype "passive"))
      (node (ref "U3") (pin "7") (pinfunction "7_7") (pintype "bidirectional"))
    )
    (net (code "105") (name "Net-(JP112-Pad3)") (class "Default")
      (node (ref "JP112") (pin "3") (pinfunction "3_3") (pintype "passive"))
      (node (ref "U3") (pin "6") (pinfunction "6_6") (pintype "bidirectional"))
    )
    (net (code "106") (name "Net-(JP112-Pad4)") (class "Default")
      (node (ref "JP112") (pin "4") (pinfunction "4_4") (pintype "passive"))
      (node (ref "U3") (pin "5") (pinfunction "5_5") (pintype "bidirectional"))
    )
    (net (code "107") (name "Net-(JP113-Pad1)") (class "Default")
      (node (ref "JP113") (pin "1") (pinfunction "1_1") (pintype "passive"))
      (node (ref "U1") (pin "4") (pinfunction "4_4") (pintype "bidirectional"))
    )
    (net (code "108") (name "Net-(JP113-Pad2)") (class "Default")
      (node (ref "JP113") (pin "2") (pinfunction "2_2") (pintype "passive"))
      (node (ref "U1") (pin "3") (pinfunction "3_3") (pintype "bidirectional"))
    )
    (net (code "109") (name "Net-(JP113-Pad3)") (class "Default")
      (node (ref "JP113") (pin "3") (pinfunction "3_3") (pintype "passive"))
      (node (ref "U1") (pin "2") (pinfunction "2_2") (pintype "bidirectional"))
    )
    (net (code "110") (name "Net-(JP113-Pad4)") (class "Default")
      (node (ref "JP113") (pin "4") (pinfunction "4_4") (pintype "passive"))
      (node (ref "U1") (pin "1") (pinfunction "1_1") (pintype "bidirectional"))
    )
    (net (code "111") (name "Net-(JP114-Pad1)") (class "Default")
      (node (ref "JP114") (pin "1") (pinfunction "1_1") (pintype "passive"))
      (node (ref "U1") (pin "8") (pinfunction "8_8") (pintype "bidirectional"))
    )
    (net (code "112") (name "Net-(JP114-Pad2)") (class "Default")
      (node (ref "JP114") (pin "2") (pinfunction "2_2") (pintype "passive"))
      (node (ref "U1") (pin "7") (pinfunction "7_7") (pintype "bidirectional"))
    )
    (net (code "113") (name "Net-(JP114-Pad3)") (class "Default")
      (node (ref "JP114") (pin "3") (pinfunction "3_3") (pintype "passive"))
      (node (ref "U1") (pin "6") (pinfunction "6_6") (pintype "bidirectional"))
    )
    (net (code "114") (name "Net-(JP114-Pad4)") (class "Default")
      (node (ref "JP114") (pin "4") (pinfunction "4_4") (pintype "passive"))
      (node (ref "U1") (pin "5") (pinfunction "5_5") (pintype "bidirectional"))
    )
    (net (code "115") (name "Net-(JP115-Pad1)") (class "Default")
      (node (ref "JP115") (pin "1") (pinfunction "1_1") (pintype "passive"))
      (node (ref "U4") (pin "8") (pinfunction "8_8") (pintype "bidirectional"))
    )
    (net (code "116") (name "Net-(JP115-Pad2)") (class "Default")
      (node (ref "JP115") (pin "2") (pinfunction "2_2") (pintype "passive"))
      (node (ref "U4") (pin "7") (pinfunction "7_7") (pintype "bidirectional"))
    )
    (net (code "117") (name "Net-(JP115-Pad3)") (class "Default")
      (node (ref "JP115") (pin "3") (pinfunction "3_3") (pintype "passive"))
      (node (ref "U4") (pin "6") (pinfunction "6_6") (pintype "bidirectional"))
    )
    (net (code "118") (name "Net-(JP115-Pad4)") (class "Default")
      (node (ref "JP115") (pin "4") (pinfunction "4_4") (pintype "passive"))
      (node (ref "U4") (pin "5") (pinfunction "5_5") (pintype "bidirectional"))
    )
    (net (code "119") (name "Net-(JP116-Pad1)") (class "Default")
      (node (ref "JP116") (pin "1") (pinfunction "1_1") (pintype "passive"))
      (node (ref "U2") (pin "4") (pinfunction "4_4") (pintype "bidirectional"))
    )
    (net (code "120") (name "Net-(JP116-Pad2)") (class "Default")
      (node (ref "JP116") (pin "2") (pinfunction "2_2") (pintype "passive"))
      (node (ref "U2") (pin "3") (pinfunction "3_3") (pintype "bidirectional"))
    )
    (net (code "121") (name "Net-(JP116-Pad3)") (class "Default")
      (node (ref "JP116") (pin "3") (pinfunction "3_3") (pintype "passive"))
      (node (ref "U2") (pin "2") (pinfunction "2_2") (pintype "bidirectional"))
    )
    (net (code "122") (name "Net-(JP116-Pad4)") (class "Default")
      (node (ref "JP116") (pin "4") (pinfunction "4_4") (pintype "passive"))
      (node (ref "U2") (pin "1") (pinfunction "1_1") (pintype "bidirectional"))
    )
    (net (code "123") (name "Net-(JP117-Pad1)") (class "Default")
      (node (ref "JP117") (pin "1") (pinfunction "1_1") (pintype "passive"))
      (node (ref "U3") (pin "4") (pinfunction "4_4") (pintype "bidirectional"))
    )
    (net (code "124") (name "Net-(JP117-Pad2)") (class "Default")
      (node (ref "JP117") (pin "2") (pinfunction "2_2") (pintype "passive"))
      (node (ref "U3") (pin "3") (pinfunction "3_3") (pintype "bidirectional"))
    )
    (net (code "125") (name "Net-(JP117-Pad3)") (class "Default")
      (node (ref "JP117") (pin "3") (pinfunction "3_3") (pintype "passive"))
      (node (ref "U3") (pin "2") (pinfunction "2_2") (pintype "bidirectional"))
    )
    (net (code "126") (name "Net-(JP117-Pad4)") (class "Default")
      (node (ref "JP117") (pin "4") (pinfunction "4_4") (pintype "passive"))
      (node (ref "U3") (pin "1") (pinfunction "1_1") (pintype "bidirectional"))
    )
    (net (code "127") (name "Net-(JP118-Pad1)") (class "Default")
      (node (ref "JP118") (pin "1") (pinfunction "1_1") (pintype "passive"))
      (node (ref "U4") (pin "4") (pinfunction "4_4") (pintype "bidirectional"))
    )
    (net (code "128") (name "Net-(JP118-Pad2)") (class "Default")
      (node (ref "JP118") (pin "2") (pinfunction "2_2") (pintype "passive"))
      (node (ref "U4") (pin "3") (pinfunction "3_3") (pintype "bidirectional"))
    )
    (net (code "129") (name "Net-(JP118-Pad3)") (class "Default")
      (node (ref "JP118") (pin "3") (pinfunction "3_3") (pintype "passive"))
      (node (ref "U4") (pin "2") (pinfunction "2_2") (pintype "bidirectional"))
    )
    (net (code "130") (name "Net-(JP118-Pad4)") (class "Default")
      (node (ref "JP118") (pin "4") (pinfunction "4_4") (pintype "passive"))
      (node (ref "U4") (pin "1") (pinfunction "1_1") (pintype "bidirectional"))
    )
    (net (code "131") (name "Net-(R2-Pad2)") (class "Default")
      (node (ref "R2") (pin "2") (pinfunction "2_2") (pintype "passive"))
      (node (ref "R3") (pin "1") (pinfunction "1_1") (pintype "passive"))
    )
    (net (code "132") (name "Net-(R4-Pad1)") (class "Default")
      (node (ref "R4") (pin "1") (pinfunction "1_1") (pintype "passive"))
      (node (ref "R5") (pin "2") (pinfunction "2_2") (pintype "passive"))
    )
    (net (code "133") (name "Net-(R6-Pad1)") (class "Default")
      (node (ref "R6") (pin "1") (pinfunction "1_1") (pintype "passive"))
      (node (ref "R7") (pin "2") (pinfunction "2_2") (pintype "passive"))
    )
    (net (code "134") (name "Net-(R8-Pad1)") (class "Default")
      (node (ref "R8") (pin "1") (pinfunction "1_1") (pintype "passive"))
      (node (ref "R9") (pin "2") (pinfunction "2_2") (pintype "passive"))
    )
    (net (code "135") (name "Net-(R10-Pad2)") (class "Default")
      (node (ref "R10") (pin "2") (pinfunction "2_2") (pintype "passive"))
      (node (ref "R11") (pin "1") (pinfunction "1_1") (pintype "passive"))
    )
    (net (code "136") (name "Net-(R12-Pad2)") (class "Default")
      (node (ref "R12") (pin "2") (pinfunction "2_2") (pintype "passive"))
      (node (ref "R13") (pin "1") (pinfunction "1_1") (pintype "passive"))
    )
    (net (code "137") (name "Net-(R14-Pad2)") (class "Default")
      (node (ref "R14") (pin "2") (pinfunction "2_2") (pintype "passive"))
      (node (ref "R15") (pin "1") (pinfunction "1_1") (pintype "passive"))
    )
    (net (code "138") (name "Net-(R16-Pad2)") (class "Default")
      (node (ref "R16") (pin "2") (pinfunction "2_2") (pintype "passive"))
      (node (ref "R17") (pin "1") (pinfunction "1_1") (pintype "passive"))
    )
    (net (code "139") (name "Net-(R18-Pad2)") (class "Default")
      (node (ref "R18") (pin "2") (pinfunction "2_2") (pintype "passive"))
      (node (ref "R19") (pin "1") (pinfunction "1_1") (pintype "passive"))
    )
    (net (code "140") (name "Net-(R20-Pad2)") (class "Default")
      (node (ref "R20") (pin "2") (pinfunction "2_2") (pintype "passive"))
      (node (ref "R21") (pin "1") (pinfunction "1_1") (pintype "passive"))
    )
    (net (code "141") (name "Net-(R22-Pad2)") (class "Default")
      (node (ref "R22") (pin "2") (pinfunction "2_2") (pintype "passive"))
      (node (ref "R23") (pin "1") (pinfunction "1_1") (pintype "passive"))
    )
    (net (code "142") (name "Net-(R24-Pad2)") (class "Default")
      (node (ref "R24") (pin "2") (pinfunction "2_2") (pintype "passive"))
      (node (ref "R25") (pin "2") (pinfunction "2_2") (pintype "passive"))
    )
    (net (code "143") (name "Net-(R26-Pad2)") (class "Default")
      (node (ref "R26") (pin "2") (pinfunction "2_2") (pintype "passive"))
      (node (ref "R27") (pin "2") (pinfunction "2_2") (pintype "passive"))
    )
    (net (code "144") (name "Net-(R28-Pad2)") (class "Default")
      (node (ref "R28") (pin "2") (pinfunction "2_2") (pintype "passive"))
      (node (ref "R29") (pin "2") (pinfunction "2_2") (pintype "passive"))
    )
    (net (code "145") (name "RXC") (class "Default")
      (node (ref "IC2") (pin "RX") (pinfunction "RX_RX") (pintype "bidirectional"))
      (node (ref "IC2") (pin "RX_1") (pinfunction "RX_RX_1") (pintype "bidirectional"))
      (node (ref "JP12") (pin "1") (pinfunction "1_1") (pintype "passive"))
      (node (ref "JP12") (pin "2") (pinfunction "2_2") (pintype "passive"))
      (node (ref "JP12") (pin "3") (pinfunction "3_3") (pintype "passive"))
      (node (ref "JP12") (pin "4") (pinfunction "4_4") (pintype "passive"))
      (node (ref "JP12") (pin "5") (pinfunction "5_5") (pintype "passive"))
      (node (ref "JP12") (pin "6") (pinfunction "6_6") (pintype "passive"))
      (node (ref "JP12") (pin "7") (pinfunction "7_7") (pintype "passive"))
      (node (ref "JP12") (pin "8") (pinfunction "8_8") (pintype "passive"))
    )
    (net (code "146") (name "TXC") (class "Default")
      (node (ref "IC2") (pin "TX") (pinfunction "TX_TX") (pintype "bidirectional"))
      (node (ref "IC2") (pin "TX_1") (pinfunction "TX_TX_1") (pintype "bidirectional"))
      (node (ref "JP17") (pin "1") (pinfunction "1_1") (pintype "passive"))
      (node (ref "JP17") (pin "2") (pinfunction "2_2") (pintype "passive"))
      (node (ref "JP17") (pin "3") (pinfunction "3_3") (pintype "passive"))
      (node (ref "JP17") (pin "4") (pinfunction "4_4") (pintype "passive"))
      (node (ref "JP17") (pin "5") (pinfunction "5_5") (pintype "passive"))
      (node (ref "JP17") (pin "6") (pinfunction "6_6") (pintype "passive"))
      (node (ref "JP17") (pin "7") (pinfunction "7_7") (pintype "passive"))
      (node (ref "JP17") (pin "8") (pinfunction "8_8") (pintype "passive"))
    )
    (net (code "147") (name "VIN") (class "Default")
      (node (ref "C2") (pin "1") (pinfunction "1_1") (pintype "passive"))
      (node (ref "IC1") (pin "OUT") (pinfunction "OUT_OUT") (pintype "passive"))
      (node (ref "IC2") (pin "VIN") (pinfunction "VIN_VIN") (pintype "power_in"))
      (node (ref "IC2") (pin "VIN_1B") (pinfunction "VIN_VIN_1B") (pintype "power_in"))
      (node (ref "JP3") (pin "1") (pinfunction "1_1") (pintype "passive"))
      (node (ref "JP3") (pin "2") (pinfunction "2_2") (pintype "passive"))
      (node (ref "JP3") (pin "3") (pinfunction "3_3") (pintype "passive"))
      (node (ref "JP3") (pin "4") (pinfunction "4_4") (pintype "passive"))
    )
    (net (code "148") (name "WKPC") (class "Default")
      (node (ref "IC2") (pin "WKP") (pinfunction "WKP_WKP") (pintype "bidirectional"))
      (node (ref "IC2") (pin "WKP_1") (pinfunction "WKP_WKP_1") (pintype "bidirectional"))
      (node (ref "JP9") (pin "1") (pinfunction "1_1") (pintype "passive"))
      (node (ref "JP9") (pin "2") (pinfunction "2_2") (pintype "passive"))
      (node (ref "JP9") (pin "3") (pinfunction "3_3") (pintype "passive"))
      (node (ref "JP9") (pin "4") (pinfunction "4_4") (pintype "passive"))
      (node (ref "JP9") (pin "5") (pinfunction "5_5") (pintype "passive"))
      (node (ref "JP9") (pin "6") (pinfunction "6_6") (pintype "passive"))
      (node (ref "JP9") (pin "7") (pinfunction "7_7") (pintype "passive"))
      (node (ref "JP9") (pin "8") (pinfunction "8_8") (pintype "passive"))
    )
    (net (code "149") (name "unconnected-(JP35-Pad2)") (class "Default")
      (node (ref "JP35") (pin "2") (pinfunction "2_2") (pintype "passive"))
    )
    (net (code "150") (name "unconnected-(JP35-Pad3)") (class "Default")
      (node (ref "JP35") (pin "3") (pinfunction "3_3") (pintype "passive"))
    )
    (net (code "151") (name "unconnected-(JP35-Pad4)") (class "Default")
      (node (ref "JP35") (pin "4") (pinfunction "4_4") (pintype "passive"))
    )
    (net (code "152") (name "unconnected-(JP35-Pad5)") (class "Default")
      (node (ref "JP35") (pin "5") (pinfunction "5_5") (pintype "passive"))
    )
    (net (code "153") (name "unconnected-(JP35-Pad6)") (class "Default")
      (node (ref "JP35") (pin "6") (pinfunction "6_6") (pintype "passive"))
    )
    (net (code "154") (name "unconnected-(JP35-Pad7)") (class "Default")
      (node (ref "JP35") (pin "7") (pinfunction "7_7") (pintype "passive"))
    )
    (net (code "155") (name "unconnected-(JP35-Pad8)") (class "Default")
      (node (ref "JP35") (pin "8") (pinfunction "8_8") (pintype "passive"))
    )
    (net (code "156") (name "unconnected-(JP35-Pad9)") (class "Default")
      (node (ref "JP35") (pin "9") (pinfunction "9_9") (pintype "passive"))
    )
    (net (code "157") (name "unconnected-(JP35-Pad10)") (class "Default")
      (node (ref "JP35") (pin "10") (pinfunction "10_10") (pintype "passive"))
    )
    (net (code "158") (name "unconnected-(JP35-Pad11)") (class "Default")
      (node (ref "JP35") (pin "11") (pinfunction "11_11") (pintype "passive"))
    )
    (net (code "159") (name "unconnected-(JP35-Pad12)") (class "Default")
      (node (ref "JP35") (pin "12") (pinfunction "12_12") (pintype "passive"))
    )
    (net (code "160") (name "unconnected-(JP35-Pad13)") (class "Default")
      (node (ref "JP35") (pin "13") (pinfunction "13_13") (pintype "passive"))
    )
    (net (code "161") (name "unconnected-(JP35-Pad14)") (class "Default")
      (node (ref "JP35") (pin "14") (pinfunction "14_14") (pintype "passive"))
    )
    (net (code "162") (name "unconnected-(JP35-Pad15)") (class "Default")
      (node (ref "JP35") (pin "15") (pinfunction "15_15") (pintype "passive"))
    )
    (net (code "163") (name "unconnected-(JP35-Pad16)") (class "Default")
      (node (ref "JP35") (pin "16") (pinfunction "16_16") (pintype "passive"))
    )
    (net (code "164") (name "unconnected-(JP36-Pad2)") (class "Default")
      (node (ref "JP36") (pin "2") (pinfunction "2_2") (pintype "passive"))
    )
    (net (code "165") (name "unconnected-(JP36-Pad3)") (class "Default")
      (node (ref "JP36") (pin "3") (pinfunction "3_3") (pintype "passive"))
    )
    (net (code "166") (name "unconnected-(JP36-Pad4)") (class "Default")
      (node (ref "JP36") (pin "4") (pinfunction "4_4") (pintype "passive"))
    )
    (net (code "167") (name "unconnected-(JP36-Pad5)") (class "Default")
      (node (ref "JP36") (pin "5") (pinfunction "5_5") (pintype "passive"))
    )
    (net (code "168") (name "unconnected-(JP36-Pad6)") (class "Default")
      (node (ref "JP36") (pin "6") (pinfunction "6_6") (pintype "passive"))
    )
    (net (code "169") (name "unconnected-(JP36-Pad7)") (class "Default")
      (node (ref "JP36") (pin "7") (pinfunction "7_7") (pintype "passive"))
    )
    (net (code "170") (name "unconnected-(JP36-Pad8)") (class "Default")
      (node (ref "JP36") (pin "8") (pinfunction "8_8") (pintype "passive"))
    )
    (net (code "171") (name "unconnected-(JP36-Pad9)") (class "Default")
      (node (ref "JP36") (pin "9") (pinfunction "9_9") (pintype "passive"))
    )
    (net (code "172") (name "unconnected-(JP36-Pad10)") (class "Default")
      (node (ref "JP36") (pin "10") (pinfunction "10_10") (pintype "passive"))
    )
    (net (code "173") (name "unconnected-(JP36-Pad11)") (class "Default")
      (node (ref "JP36") (pin "11") (pinfunction "11_11") (pintype "passive"))
    )
    (net (code "174") (name "unconnected-(JP36-Pad12)") (class "Default")
      (node (ref "JP36") (pin "12") (pinfunction "12_12") (pintype "passive"))
    )
    (net (code "175") (name "unconnected-(JP36-Pad13)") (class "Default")
      (node (ref "JP36") (pin "13") (pinfunction "13_13") (pintype "passive"))
    )
    (net (code "176") (name "unconnected-(JP36-Pad14)") (class "Default")
      (node (ref "JP36") (pin "14") (pinfunction "14_14") (pintype "passive"))
    )
    (net (code "177") (name "unconnected-(JP36-Pad15)") (class "Default")
      (node (ref "JP36") (pin "15") (pinfunction "15_15") (pintype "passive"))
    )
    (net (code "178") (name "unconnected-(JP36-Pad16)") (class "Default")
      (node (ref "JP36") (pin "16") (pinfunction "16_16") (pintype "passive"))
    )
    (net (code "179") (name "unconnected-(JP37-Pad2)") (class "Default")
      (node (ref "JP37") (pin "2") (pinfunction "2_2") (pintype "passive"))
    )
    (net (code "180") (name "unconnected-(JP37-Pad3)") (class "Default")
      (node (ref "JP37") (pin "3") (pinfunction "3_3") (pintype "passive"))
    )
    (net (code "181") (name "unconnected-(JP37-Pad4)") (class "Default")
      (node (ref "JP37") (pin "4") (pinfunction "4_4") (pintype "passive"))
    )
    (net (code "182") (name "unconnected-(JP37-Pad5)") (class "Default")
      (node (ref "JP37") (pin "5") (pinfunction "5_5") (pintype "passive"))
    )
    (net (code "183") (name "unconnected-(JP37-Pad6)") (class "Default")
      (node (ref "JP37") (pin "6") (pinfunction "6_6") (pintype "passive"))
    )
    (net (code "184") (name "unconnected-(JP37-Pad7)") (class "Default")
      (node (ref "JP37") (pin "7") (pinfunction "7_7") (pintype "passive"))
    )
    (net (code "185") (name "unconnected-(JP37-Pad8)") (class "Default")
      (node (ref "JP37") (pin "8") (pinfunction "8_8") (pintype "passive"))
    )
    (net (code "186") (name "unconnected-(JP37-Pad9)") (class "Default")
      (node (ref "JP37") (pin "9") (pinfunction "9_9") (pintype "passive"))
    )
    (net (code "187") (name "unconnected-(JP37-Pad10)") (class "Default")
      (node (ref "JP37") (pin "10") (pinfunction "10_10") (pintype "passive"))
    )
    (net (code "188") (name "unconnected-(JP37-Pad11)") (class "Default")
      (node (ref "JP37") (pin "11") (pinfunction "11_11") (pintype "passive"))
    )
    (net (code "189") (name "unconnected-(JP37-Pad12)") (class "Default")
      (node (ref "JP37") (pin "12") (pinfunction "12_12") (pintype "passive"))
    )
    (net (code "190") (name "unconnected-(JP37-Pad13)") (class "Default")
      (node (ref "JP37") (pin "13") (pinfunction "13_13") (pintype "passive"))
    )
    (net (code "191") (name "unconnected-(JP37-Pad14)") (class "Default")
      (node (ref "JP37") (pin "14") (pinfunction "14_14") (pintype "passive"))
    )
    (net (code "192") (name "unconnected-(JP37-Pad15)") (class "Default")
      (node (ref "JP37") (pin "15") (pinfunction "15_15") (pintype "passive"))
    )
    (net (code "193") (name "unconnected-(JP37-Pad16)") (class "Default")
      (node (ref "JP37") (pin "16") (pinfunction "16_16") (pintype "passive"))
    )
    (net (code "194") (name "unconnected-(JP40-Pad2)") (class "Default")
      (node (ref "JP40") (pin "2") (pinfunction "2_2") (pintype "passive"))
    )
    (net (code "195") (name "unconnected-(JP40-Pad3)") (class "Default")
      (node (ref "JP40") (pin "3") (pinfunction "3_3") (pintype "passive"))
    )
    (net (code "196") (name "unconnected-(JP40-Pad4)") (class "Default")
      (node (ref "JP40") (pin "4") (pinfunction "4_4") (pintype "passive"))
    )
    (net (code "197") (name "unconnected-(JP40-Pad5)") (class "Default")
      (node (ref "JP40") (pin "5") (pinfunction "5_5") (pintype "passive"))
    )
    (net (code "198") (name "unconnected-(JP40-Pad6)") (class "Default")
      (node (ref "JP40") (pin "6") (pinfunction "6_6") (pintype "passive"))
    )
    (net (code "199") (name "unconnected-(JP40-Pad7)") (class "Default")
      (node (ref "JP40") (pin "7") (pinfunction "7_7") (pintype "passive"))
    )
    (net (code "200") (name "unconnected-(JP40-Pad8)") (class "Default")
      (node (ref "JP40") (pin "8") (pinfunction "8_8") (pintype "passive"))
    )
    (net (code "201") (name "unconnected-(JP40-Pad9)") (class "Default")
      (node (ref "JP40") (pin "9") (pinfunction "9_9") (pintype "passive"))
    )
    (net (code "202") (name "unconnected-(JP40-Pad10)") (class "Default")
      (node (ref "JP40") (pin "10") (pinfunction "10_10") (pintype "passive"))
    )
    (net (code "203") (name "unconnected-(JP40-Pad11)") (class "Default")
      (node (ref "JP40") (pin "11") (pinfunction "11_11") (pintype "passive"))
    )
    (net (code "204") (name "unconnected-(JP40-Pad12)") (class "Default")
      (node (ref "JP40") (pin "12") (pinfunction "12_12") (pintype "passive"))
    )
    (net (code "205") (name "unconnected-(JP40-Pad13)") (class "Default")
      (node (ref "JP40") (pin "13") (pinfunction "13_13") (pintype "passive"))
    )
    (net (code "206") (name "unconnected-(JP40-Pad14)") (class "Default")
      (node (ref "JP40") (pin "14") (pinfunction "14_14") (pintype "passive"))
    )
    (net (code "207") (name "unconnected-(JP40-Pad15)") (class "Default")
      (node (ref "JP40") (pin "15") (pinfunction "15_15") (pintype "passive"))
    )
    (net (code "208") (name "unconnected-(JP40-Pad16)") (class "Default")
      (node (ref "JP40") (pin "16") (pinfunction "16_16") (pintype "passive"))
    )
    (net (code "209") (name "unconnected-(JP41-Pad2)") (class "Default")
      (node (ref "JP41") (pin "2") (pinfunction "2_2") (pintype "passive"))
    )
    (net (code "210") (name "unconnected-(JP41-Pad3)") (class "Default")
      (node (ref "JP41") (pin "3") (pinfunction "3_3") (pintype "passive"))
    )
    (net (code "211") (name "unconnected-(JP41-Pad4)") (class "Default")
      (node (ref "JP41") (pin "4") (pinfunction "4_4") (pintype "passive"))
    )
    (net (code "212") (name "unconnected-(JP41-Pad5)") (class "Default")
      (node (ref "JP41") (pin "5") (pinfunction "5_5") (pintype "passive"))
    )
    (net (code "213") (name "unconnected-(JP41-Pad6)") (class "Default")
      (node (ref "JP41") (pin "6") (pinfunction "6_6") (pintype "passive"))
    )
    (net (code "214") (name "unconnected-(JP41-Pad7)") (class "Default")
      (node (ref "JP41") (pin "7") (pinfunction "7_7") (pintype "passive"))
    )
    (net (code "215") (name "unconnected-(JP41-Pad8)") (class "Default")
      (node (ref "JP41") (pin "8") (pinfunction "8_8") (pintype "passive"))
    )
    (net (code "216") (name "unconnected-(JP41-Pad9)") (class "Default")
      (node (ref "JP41") (pin "9") (pinfunction "9_9") (pintype "passive"))
    )
    (net (code "217") (name "unconnected-(JP41-Pad10)") (class "Default")
      (node (ref "JP41") (pin "10") (pinfunction "10_10") (pintype "passive"))
    )
    (net (code "218") (name "unconnected-(JP41-Pad11)") (class "Default")
      (node (ref "JP41") (pin "11") (pinfunction "11_11") (pintype "passive"))
    )
    (net (code "219") (name "unconnected-(JP41-Pad12)") (class "Default")
      (node (ref "JP41") (pin "12") (pinfunction "12_12") (pintype "passive"))
    )
    (net (code "220") (name "unconnected-(JP41-Pad13)") (class "Default")
      (node (ref "JP41") (pin "13") (pinfunction "13_13") (pintype "passive"))
    )
    (net (code "221") (name "unconnected-(JP41-Pad14)") (class "Default")
      (node (ref "JP41") (pin "14") (pinfunction "14_14") (pintype "passive"))
    )
    (net (code "222") (name "unconnected-(JP41-Pad15)") (class "Default")
      (node (ref "JP41") (pin "15") (pinfunction "15_15") (pintype "passive"))
    )
    (net (code "223") (name "unconnected-(JP41-Pad16)") (class "Default")
      (node (ref "JP41") (pin "16") (pinfunction "16_16") (pintype "passive"))
    )
    (net (code "224") (name "unconnected-(JP42-Pad2)") (class "Default")
      (node (ref "JP42") (pin "2") (pinfunction "2_2") (pintype "passive"))
    )
    (net (code "225") (name "unconnected-(JP42-Pad3)") (class "Default")
      (node (ref "JP42") (pin "3") (pinfunction "3_3") (pintype "passive"))
    )
    (net (code "226") (name "unconnected-(JP42-Pad4)") (class "Default")
      (node (ref "JP42") (pin "4") (pinfunction "4_4") (pintype "passive"))
    )
    (net (code "227") (name "unconnected-(JP42-Pad5)") (class "Default")
      (node (ref "JP42") (pin "5") (pinfunction "5_5") (pintype "passive"))
    )
    (net (code "228") (name "unconnected-(JP42-Pad6)") (class "Default")
      (node (ref "JP42") (pin "6") (pinfunction "6_6") (pintype "passive"))
    )
    (net (code "229") (name "unconnected-(JP42-Pad7)") (class "Default")
      (node (ref "JP42") (pin "7") (pinfunction "7_7") (pintype "passive"))
    )
    (net (code "230") (name "unconnected-(JP42-Pad8)") (class "Default")
      (node (ref "JP42") (pin "8") (pinfunction "8_8") (pintype "passive"))
    )
    (net (code "231") (name "unconnected-(JP42-Pad9)") (class "Default")
      (node (ref "JP42") (pin "9") (pinfunction "9_9") (pintype "passive"))
    )
    (net (code "232") (name "unconnected-(JP42-Pad10)") (class "Default")
      (node (ref "JP42") (pin "10") (pinfunction "10_10") (pintype "passive"))
    )
    (net (code "233") (name "unconnected-(JP42-Pad11)") (class "Default")
      (node (ref "JP42") (pin "11") (pinfunction "11_11") (pintype "passive"))
    )
    (net (code "234") (name "unconnected-(JP42-Pad12)") (class "Default")
      (node (ref "JP42") (pin "12") (pinfunction "12_12") (pintype "passive"))
    )
    (net (code "235") (name "unconnected-(JP42-Pad13)") (class "Default")
      (node (ref "JP42") (pin "13") (pinfunction "13_13") (pintype "passive"))
    )
    (net (code "236") (name "unconnected-(JP42-Pad14)") (class "Default")
      (node (ref "JP42") (pin "14") (pinfunction "14_14") (pintype "passive"))
    )
    (net (code "237") (name "unconnected-(JP42-Pad15)") (class "Default")
      (node (ref "JP42") (pin "15") (pinfunction "15_15") (pintype "passive"))
    )
    (net (code "238") (name "unconnected-(JP42-Pad16)") (class "Default")
      (node (ref "JP42") (pin "16") (pinfunction "16_16") (pintype "passive"))
    )
    (net (code "239") (name "unconnected-(JP43-Pad2)") (class "Default")
      (node (ref "JP43") (pin "2") (pinfunction "2_2") (pintype "passive"))
    )
    (net (code "240") (name "unconnected-(JP43-Pad3)") (class "Default")
      (node (ref "JP43") (pin "3") (pinfunction "3_3") (pintype "passive"))
    )
    (net (code "241") (name "unconnected-(JP43-Pad4)") (class "Default")
      (node (ref "JP43") (pin "4") (pinfunction "4_4") (pintype "passive"))
    )
    (net (code "242") (name "unconnected-(JP43-Pad5)") (class "Default")
      (node (ref "JP43") (pin "5") (pinfunction "5_5") (pintype "passive"))
    )
    (net (code "243") (name "unconnected-(JP43-Pad6)") (class "Default")
      (node (ref "JP43") (pin "6") (pinfunction "6_6") (pintype "passive"))
    )
    (net (code "244") (name "unconnected-(JP43-Pad7)") (class "Default")
      (node (ref "JP43") (pin "7") (pinfunction "7_7") (pintype "passive"))
    )
    (net (code "245") (name "unconnected-(JP43-Pad8)") (class "Default")
      (node (ref "JP43") (pin "8") (pinfunction "8_8") (pintype "passive"))
    )
    (net (code "246") (name "unconnected-(JP43-Pad9)") (class "Default")
      (node (ref "JP43") (pin "9") (pinfunction "9_9") (pintype "passive"))
    )
    (net (code "247") (name "unconnected-(JP43-Pad10)") (class "Default")
      (node (ref "JP43") (pin "10") (pinfunction "10_10") (pintype "passive"))
    )
    (net (code "248") (name "unconnected-(JP43-Pad11)") (class "Default")
      (node (ref "JP43") (pin "11") (pinfunction "11_11") (pintype "passive"))
    )
    (net (code "249") (name "unconnected-(JP43-Pad12)") (class "Default")
      (node (ref "JP43") (pin "12") (pinfunction "12_12") (pintype "passive"))
    )
    (net (code "250") (name "unconnected-(JP43-Pad13)") (class "Default")
      (node (ref "JP43") (pin "13") (pinfunction "13_13") (pintype "passive"))
    )
    (net (code "251") (name "unconnected-(JP43-Pad14)") (class "Default")
      (node (ref "JP43") (pin "14") (pinfunction "14_14") (pintype "passive"))
    )
    (net (code "252") (name "unconnected-(JP43-Pad15)") (class "Default")
      (node (ref "JP43") (pin "15") (pinfunction "15_15") (pintype "passive"))
    )
    (net (code "253") (name "unconnected-(JP43-Pad16)") (class "Default")
      (node (ref "JP43") (pin "16") (pinfunction "16_16") (pintype "passive"))
    )
    (net (code "254") (name "unconnected-(JP44-Pad2)") (class "Default")
      (node (ref "JP44") (pin "2") (pinfunction "2_2") (pintype "passive"))
    )
    (net (code "255") (name "unconnected-(JP44-Pad3)") (class "Default")
      (node (ref "JP44") (pin "3") (pinfunction "3_3") (pintype "passive"))
    )
    (net (code "256") (name "unconnected-(JP44-Pad4)") (class "Default")
      (node (ref "JP44") (pin "4") (pinfunction "4_4") (pintype "passive"))
    )
    (net (code "257") (name "unconnected-(JP44-Pad5)") (class "Default")
      (node (ref "JP44") (pin "5") (pinfunction "5_5") (pintype "passive"))
    )
    (net (code "258") (name "unconnected-(JP44-Pad6)") (class "Default")
      (node (ref "JP44") (pin "6") (pinfunction "6_6") (pintype "passive"))
    )
    (net (code "259") (name "unconnected-(JP44-Pad7)") (class "Default")
      (node (ref "JP44") (pin "7") (pinfunction "7_7") (pintype "passive"))
    )
    (net (code "260") (name "unconnected-(JP44-Pad8)") (class "Default")
      (node (ref "JP44") (pin "8") (pinfunction "8_8") (pintype "passive"))
    )
    (net (code "261") (name "unconnected-(JP44-Pad9)") (class "Default")
      (node (ref "JP44") (pin "9") (pinfunction "9_9") (pintype "passive"))
    )
    (net (code "262") (name "unconnected-(JP44-Pad10)") (class "Default")
      (node (ref "JP44") (pin "10") (pinfunction "10_10") (pintype "passive"))
    )
    (net (code "263") (name "unconnected-(JP44-Pad11)") (class "Default")
      (node (ref "JP44") (pin "11") (pinfunction "11_11") (pintype "passive"))
    )
    (net (code "264") (name "unconnected-(JP44-Pad12)") (class "Default")
      (node (ref "JP44") (pin "12") (pinfunction "12_12") (pintype "passive"))
    )
    (net (code "265") (name "unconnected-(JP44-Pad13)") (class "Default")
      (node (ref "JP44") (pin "13") (pinfunction "13_13") (pintype "passive"))
    )
    (net (code "266") (name "unconnected-(JP44-Pad14)") (class "Default")
      (node (ref "JP44") (pin "14") (pinfunction "14_14") (pintype "passive"))
    )
    (net (code "267") (name "unconnected-(JP44-Pad15)") (class "Default")
      (node (ref "JP44") (pin "15") (pinfunction "15_15") (pintype "passive"))
    )
    (net (code "268") (name "unconnected-(JP44-Pad16)") (class "Default")
      (node (ref "JP44") (pin "16") (pinfunction "16_16") (pintype "passive"))
    )
    (net (code "269") (name "unconnected-(JP45-Pad2)") (class "Default")
      (node (ref "JP45") (pin "2") (pinfunction "2_2") (pintype "passive"))
    )
    (net (code "270") (name "unconnected-(JP45-Pad3)") (class "Default")
      (node (ref "JP45") (pin "3") (pinfunction "3_3") (pintype "passive"))
    )
    (net (code "271") (name "unconnected-(JP45-Pad4)") (class "Default")
      (node (ref "JP45") (pin "4") (pinfunction "4_4") (pintype "passive"))
    )
    (net (code "272") (name "unconnected-(JP45-Pad5)") (class "Default")
      (node (ref "JP45") (pin "5") (pinfunction "5_5") (pintype "passive"))
    )
    (net (code "273") (name "unconnected-(JP45-Pad6)") (class "Default")
      (node (ref "JP45") (pin "6") (pinfunction "6_6") (pintype "passive"))
    )
    (net (code "274") (name "unconnected-(JP45-Pad7)") (class "Default")
      (node (ref "JP45") (pin "7") (pinfunction "7_7") (pintype "passive"))
    )
    (net (code "275") (name "unconnected-(JP45-Pad8)") (class "Default")
      (node (ref "JP45") (pin "8") (pinfunction "8_8") (pintype "passive"))
    )
    (net (code "276") (name "unconnected-(JP45-Pad9)") (class "Default")
      (node (ref "JP45") (pin "9") (pinfunction "9_9") (pintype "passive"))
    )
    (net (code "277") (name "unconnected-(JP45-Pad10)") (class "Default")
      (node (ref "JP45") (pin "10") (pinfunction "10_10") (pintype "passive"))
    )
    (net (code "278") (name "unconnected-(JP45-Pad11)") (class "Default")
      (node (ref "JP45") (pin "11") (pinfunction "11_11") (pintype "passive"))
    )
    (net (code "279") (name "unconnected-(JP45-Pad12)") (class "Default")
      (node (ref "JP45") (pin "12") (pinfunction "12_12") (pintype "passive"))
    )
    (net (code "280") (name "unconnected-(JP45-Pad13)") (class "Default")
      (node (ref "JP45") (pin "13") (pinfunction "13_13") (pintype "passive"))
    )
    (net (code "281") (name "unconnected-(JP45-Pad14)") (class "Default")
      (node (ref "JP45") (pin "14") (pinfunction "14_14") (pintype "passive"))
    )
    (net (code "282") (name "unconnected-(JP45-Pad15)") (class "Default")
      (node (ref "JP45") (pin "15") (pinfunction "15_15") (pintype "passive"))
    )
    (net (code "283") (name "unconnected-(JP45-Pad16)") (class "Default")
      (node (ref "JP45") (pin "16") (pinfunction "16_16") (pintype "passive"))
    )
    (net (code "284") (name "unconnected-(JP46-Pad2)") (class "Default")
      (node (ref "JP46") (pin "2") (pinfunction "2_2") (pintype "passive"))
    )
    (net (code "285") (name "unconnected-(JP46-Pad3)") (class "Default")
      (node (ref "JP46") (pin "3") (pinfunction "3_3") (pintype "passive"))
    )
    (net (code "286") (name "unconnected-(JP46-Pad4)") (class "Default")
      (node (ref "JP46") (pin "4") (pinfunction "4_4") (pintype "passive"))
    )
    (net (code "287") (name "unconnected-(JP46-Pad5)") (class "Default")
      (node (ref "JP46") (pin "5") (pinfunction "5_5") (pintype "passive"))
    )
    (net (code "288") (name "unconnected-(JP46-Pad6)") (class "Default")
      (node (ref "JP46") (pin "6") (pinfunction "6_6") (pintype "passive"))
    )
    (net (code "289") (name "unconnected-(JP46-Pad7)") (class "Default")
      (node (ref "JP46") (pin "7") (pinfunction "7_7") (pintype "passive"))
    )
    (net (code "290") (name "unconnected-(JP46-Pad8)") (class "Default")
      (node (ref "JP46") (pin "8") (pinfunction "8_8") (pintype "passive"))
    )
    (net (code "291") (name "unconnected-(JP46-Pad9)") (class "Default")
      (node (ref "JP46") (pin "9") (pinfunction "9_9") (pintype "passive"))
    )
    (net (code "292") (name "unconnected-(JP46-Pad10)") (class "Default")
      (node (ref "JP46") (pin "10") (pinfunction "10_10") (pintype "passive"))
    )
    (net (code "293") (name "unconnected-(JP46-Pad11)") (class "Default")
      (node (ref "JP46") (pin "11") (pinfunction "11_11") (pintype "passive"))
    )
    (net (code "294") (name "unconnected-(JP46-Pad12)") (class "Default")
      (node (ref "JP46") (pin "12") (pinfunction "12_12") (pintype "passive"))
    )
    (net (code "295") (name "unconnected-(JP46-Pad13)") (class "Default")
      (node (ref "JP46") (pin "13") (pinfunction "13_13") (pintype "passive"))
    )
    (net (code "296") (name "unconnected-(JP46-Pad14)") (class "Default")
      (node (ref "JP46") (pin "14") (pinfunction "14_14") (pintype "passive"))
    )
    (net (code "297") (name "unconnected-(JP46-Pad15)") (class "Default")
      (node (ref "JP46") (pin "15") (pinfunction "15_15") (pintype "passive"))
    )
    (net (code "298") (name "unconnected-(JP46-Pad16)") (class "Default")
      (node (ref "JP46") (pin "16") (pinfunction "16_16") (pintype "passive"))
    )
    (net (code "299") (name "unconnected-(JP47-Pad2)") (class "Default")
      (node (ref "JP47") (pin "2") (pinfunction "2_2") (pintype "passive"))
    )
    (net (code "300") (name "unconnected-(JP47-Pad3)") (class "Default")
      (node (ref "JP47") (pin "3") (pinfunction "3_3") (pintype "passive"))
    )
    (net (code "301") (name "unconnected-(JP47-Pad4)") (class "Default")
      (node (ref "JP47") (pin "4") (pinfunction "4_4") (pintype "passive"))
    )
    (net (code "302") (name "unconnected-(JP47-Pad5)") (class "Default")
      (node (ref "JP47") (pin "5") (pinfunction "5_5") (pintype "passive"))
    )
    (net (code "303") (name "unconnected-(JP47-Pad6)") (class "Default")
      (node (ref "JP47") (pin "6") (pinfunction "6_6") (pintype "passive"))
    )
    (net (code "304") (name "unconnected-(JP47-Pad7)") (class "Default")
      (node (ref "JP47") (pin "7") (pinfunction "7_7") (pintype "passive"))
    )
    (net (code "305") (name "unconnected-(JP47-Pad8)") (class "Default")
      (node (ref "JP47") (pin "8") (pinfunction "8_8") (pintype "passive"))
    )
    (net (code "306") (name "unconnected-(JP47-Pad9)") (class "Default")
      (node (ref "JP47") (pin "9") (pinfunction "9_9") (pintype "passive"))
    )
    (net (code "307") (name "unconnected-(JP47-Pad10)") (class "Default")
      (node (ref "JP47") (pin "10") (pinfunction "10_10") (pintype "passive"))
    )
    (net (code "308") (name "unconnected-(JP47-Pad11)") (class "Default")
      (node (ref "JP47") (pin "11") (pinfunction "11_11") (pintype "passive"))
    )
    (net (code "309") (name "unconnected-(JP47-Pad12)") (class "Default")
      (node (ref "JP47") (pin "12") (pinfunction "12_12") (pintype "passive"))
    )
    (net (code "310") (name "unconnected-(JP47-Pad13)") (class "Default")
      (node (ref "JP47") (pin "13") (pinfunction "13_13") (pintype "passive"))
    )
    (net (code "311") (name "unconnected-(JP47-Pad14)") (class "Default")
      (node (ref "JP47") (pin "14") (pinfunction "14_14") (pintype "passive"))
    )
    (net (code "312") (name "unconnected-(JP47-Pad15)") (class "Default")
      (node (ref "JP47") (pin "15") (pinfunction "15_15") (pintype "passive"))
    )
    (net (code "313") (name "unconnected-(JP47-Pad16)") (class "Default")
      (node (ref "JP47") (pin "16") (pinfunction "16_16") (pintype "passive"))
    )
    (net (code "314") (name "unconnected-(JP48-Pad2)") (class "Default")
      (node (ref "JP48") (pin "2") (pinfunction "2_2") (pintype "passive"))
    )
    (net (code "315") (name "unconnected-(JP48-Pad3)") (class "Default")
      (node (ref "JP48") (pin "3") (pinfunction "3_3") (pintype "passive"))
    )
    (net (code "316") (name "unconnected-(JP48-Pad4)") (class "Default")
      (node (ref "JP48") (pin "4") (pinfunction "4_4") (pintype "passive"))
    )
    (net (code "317") (name "unconnected-(JP48-Pad5)") (class "Default")
      (node (ref "JP48") (pin "5") (pinfunction "5_5") (pintype "passive"))
    )
    (net (code "318") (name "unconnected-(JP48-Pad6)") (class "Default")
      (node (ref "JP48") (pin "6") (pinfunction "6_6") (pintype "passive"))
    )
    (net (code "319") (name "unconnected-(JP48-Pad7)") (class "Default")
      (node (ref "JP48") (pin "7") (pinfunction "7_7") (pintype "passive"))
    )
    (net (code "320") (name "unconnected-(JP48-Pad8)") (class "Default")
      (node (ref "JP48") (pin "8") (pinfunction "8_8") (pintype "passive"))
    )
    (net (code "321") (name "unconnected-(JP48-Pad9)") (class "Default")
      (node (ref "JP48") (pin "9") (pinfunction "9_9") (pintype "passive"))
    )
    (net (code "322") (name "unconnected-(JP48-Pad10)") (class "Default")
      (node (ref "JP48") (pin "10") (pinfunction "10_10") (pintype "passive"))
    )
    (net (code "323") (name "unconnected-(JP48-Pad11)") (class "Default")
      (node (ref "JP48") (pin "11") (pinfunction "11_11") (pintype "passive"))
    )
    (net (code "324") (name "unconnected-(JP48-Pad12)") (class "Default")
      (node (ref "JP48") (pin "12") (pinfunction "12_12") (pintype "passive"))
    )
    (net (code "325") (name "unconnected-(JP48-Pad13)") (class "Default")
      (node (ref "JP48") (pin "13") (pinfunction "13_13") (pintype "passive"))
    )
    (net (code "326") (name "unconnected-(JP48-Pad14)") (class "Default")
      (node (ref "JP48") (pin "14") (pinfunction "14_14") (pintype "passive"))
    )
    (net (code "327") (name "unconnected-(JP48-Pad15)") (class "Default")
      (node (ref "JP48") (pin "15") (pinfunction "15_15") (pintype "passive"))
    )
    (net (code "328") (name "unconnected-(JP48-Pad16)") (class "Default")
      (node (ref "JP48") (pin "16") (pinfunction "16_16") (pintype "passive"))
    )
    (net (code "329") (name "unconnected-(JP49-Pad2)") (class "Default")
      (node (ref "JP49") (pin "2") (pinfunction "2_2") (pintype "passive"))
    )
    (net (code "330") (name "unconnected-(JP49-Pad3)") (class "Default")
      (node (ref "JP49") (pin "3") (pinfunction "3_3") (pintype "passive"))
    )
    (net (code "331") (name "unconnected-(JP49-Pad4)") (class "Default")
      (node (ref "JP49") (pin "4") (pinfunction "4_4") (pintype "passive"))
    )
    (net (code "332") (name "unconnected-(JP49-Pad5)") (class "Default")
      (node (ref "JP49") (pin "5") (pinfunction "5_5") (pintype "passive"))
    )
    (net (code "333") (name "unconnected-(JP49-Pad6)") (class "Default")
      (node (ref "JP49") (pin "6") (pinfunction "6_6") (pintype "passive"))
    )
    (net (code "334") (name "unconnected-(JP49-Pad7)") (class "Default")
      (node (ref "JP49") (pin "7") (pinfunction "7_7") (pintype "passive"))
    )
    (net (code "335") (name "unconnected-(JP49-Pad8)") (class "Default")
      (node (ref "JP49") (pin "8") (pinfunction "8_8") (pintype "passive"))
    )
    (net (code "336") (name "unconnected-(JP49-Pad9)") (class "Default")
      (node (ref "JP49") (pin "9") (pinfunction "9_9") (pintype "passive"))
    )
    (net (code "337") (name "unconnected-(JP49-Pad10)") (class "Default")
      (node (ref "JP49") (pin "10") (pinfunction "10_10") (pintype "passive"))
    )
    (net (code "338") (name "unconnected-(JP49-Pad11)") (class "Default")
      (node (ref "JP49") (pin "11") (pinfunction "11_11") (pintype "passive"))
    )
    (net (code "339") (name "unconnected-(JP49-Pad12)") (class "Default")
      (node (ref "JP49") (pin "12") (pinfunction "12_12") (pintype "passive"))
    )
    (net (code "340") (name "unconnected-(JP49-Pad13)") (class "Default")
      (node (ref "JP49") (pin "13") (pinfunction "13_13") (pintype "passive"))
    )
    (net (code "341") (name "unconnected-(JP49-Pad14)") (class "Default")
      (node (ref "JP49") (pin "14") (pinfunction "14_14") (pintype "passive"))
    )
    (net (code "342") (name "unconnected-(JP49-Pad15)") (class "Default")
      (node (ref "JP49") (pin "15") (pinfunction "15_15") (pintype "passive"))
    )
    (net (code "343") (name "unconnected-(JP49-Pad16)") (class "Default")
      (node (ref "JP49") (pin "16") (pinfunction "16_16") (pintype "passive"))
    )
    (net (code "344") (name "unconnected-(JP50-Pad2)") (class "Default")
      (node (ref "JP50") (pin "2") (pinfunction "2_2") (pintype "passive"))
    )
    (net (code "345") (name "unconnected-(JP50-Pad3)") (class "Default")
      (node (ref "JP50") (pin "3") (pinfunction "3_3") (pintype "passive"))
    )
    (net (code "346") (name "unconnected-(JP50-Pad4)") (class "Default")
      (node (ref "JP50") (pin "4") (pinfunction "4_4") (pintype "passive"))
    )
    (net (code "347") (name "unconnected-(JP50-Pad5)") (class "Default")
      (node (ref "JP50") (pin "5") (pinfunction "5_5") (pintype "passive"))
    )
    (net (code "348") (name "unconnected-(JP50-Pad6)") (class "Default")
      (node (ref "JP50") (pin "6") (pinfunction "6_6") (pintype "passive"))
    )
    (net (code "349") (name "unconnected-(JP50-Pad7)") (class "Default")
      (node (ref "JP50") (pin "7") (pinfunction "7_7") (pintype "passive"))
    )
    (net (code "350") (name "unconnected-(JP50-Pad8)") (class "Default")
      (node (ref "JP50") (pin "8") (pinfunction "8_8") (pintype "passive"))
    )
    (net (code "351") (name "unconnected-(JP50-Pad9)") (class "Default")
      (node (ref "JP50") (pin "9") (pinfunction "9_9") (pintype "passive"))
    )
    (net (code "352") (name "unconnected-(JP50-Pad10)") (class "Default")
      (node (ref "JP50") (pin "10") (pinfunction "10_10") (pintype "passive"))
    )
    (net (code "353") (name "unconnected-(JP50-Pad11)") (class "Default")
      (node (ref "JP50") (pin "11") (pinfunction "11_11") (pintype "passive"))
    )
    (net (code "354") (name "unconnected-(JP50-Pad12)") (class "Default")
      (node (ref "JP50") (pin "12") (pinfunction "12_12") (pintype "passive"))
    )
    (net (code "355") (name "unconnected-(JP50-Pad13)") (class "Default")
      (node (ref "JP50") (pin "13") (pinfunction "13_13") (pintype "passive"))
    )
    (net (code "356") (name "unconnected-(JP50-Pad14)") (class "Default")
      (node (ref "JP50") (pin "14") (pinfunction "14_14") (pintype "passive"))
    )
    (net (code "357") (name "unconnected-(JP50-Pad15)") (class "Default")
      (node (ref "JP50") (pin "15") (pinfunction "15_15") (pintype "passive"))
    )
    (net (code "358") (name "unconnected-(JP50-Pad16)") (class "Default")
      (node (ref "JP50") (pin "16") (pinfunction "16_16") (pintype "passive"))
    )
    (net (code "359") (name "unconnected-(JP51-Pad2)") (class "Default")
      (node (ref "JP51") (pin "2") (pinfunction "2_2") (pintype "passive"))
    )
    (net (code "360") (name "unconnected-(JP51-Pad3)") (class "Default")
      (node (ref "JP51") (pin "3") (pinfunction "3_3") (pintype "passive"))
    )
    (net (code "361") (name "unconnected-(JP51-Pad4)") (class "Default")
      (node (ref "JP51") (pin "4") (pinfunction "4_4") (pintype "passive"))
    )
    (net (code "362") (name "unconnected-(JP51-Pad5)") (class "Default")
      (node (ref "JP51") (pin "5") (pinfunction "5_5") (pintype "passive"))
    )
    (net (code "363") (name "unconnected-(JP51-Pad6)") (class "Default")
      (node (ref "JP51") (pin "6") (pinfunction "6_6") (pintype "passive"))
    )
    (net (code "364") (name "unconnected-(JP51-Pad7)") (class "Default")
      (node (ref "JP51") (pin "7") (pinfunction "7_7") (pintype "passive"))
    )
    (net (code "365") (name "unconnected-(JP51-Pad8)") (class "Default")
      (node (ref "JP51") (pin "8") (pinfunction "8_8") (pintype "passive"))
    )
    (net (code "366") (name "unconnected-(JP51-Pad9)") (class "Default")
      (node (ref "JP51") (pin "9") (pinfunction "9_9") (pintype "passive"))
    )
    (net (code "367") (name "unconnected-(JP51-Pad10)") (class "Default")
      (node (ref "JP51") (pin "10") (pinfunction "10_10") (pintype "passive"))
    )
    (net (code "368") (name "unconnected-(JP51-Pad11)") (class "Default")
      (node (ref "JP51") (pin "11") (pinfunction "11_11") (pintype "passive"))
    )
    (net (code "369") (name "unconnected-(JP51-Pad12)") (class "Default")
      (node (ref "JP51") (pin "12") (pinfunction "12_12") (pintype "passive"))
    )
    (net (code "370") (name "unconnected-(JP51-Pad13)") (class "Default")
      (node (ref "JP51") (pin "13") (pinfunction "13_13") (pintype "passive"))
    )
    (net (code "371") (name "unconnected-(JP51-Pad14)") (class "Default")
      (node (ref "JP51") (pin "14") (pinfunction "14_14") (pintype "passive"))
    )
    (net (code "372") (name "unconnected-(JP51-Pad15)") (class "Default")
      (node (ref "JP51") (pin "15") (pinfunction "15_15") (pintype "passive"))
    )
    (net (code "373") (name "unconnected-(JP51-Pad16)") (class "Default")
      (node (ref "JP51") (pin "16") (pinfunction "16_16") (pintype "passive"))
    )
    (net (code "374") (name "unconnected-(JP52-Pad2)") (class "Default")
      (node (ref "JP52") (pin "2") (pinfunction "2_2") (pintype "passive"))
    )
    (net (code "375") (name "unconnected-(JP52-Pad3)") (class "Default")
      (node (ref "JP52") (pin "3") (pinfunction "3_3") (pintype "passive"))
    )
    (net (code "376") (name "unconnected-(JP52-Pad4)") (class "Default")
      (node (ref "JP52") (pin "4") (pinfunction "4_4") (pintype "passive"))
    )
    (net (code "377") (name "unconnected-(JP52-Pad5)") (class "Default")
      (node (ref "JP52") (pin "5") (pinfunction "5_5") (pintype "passive"))
    )
    (net (code "378") (name "unconnected-(JP52-Pad6)") (class "Default")
      (node (ref "JP52") (pin "6") (pinfunction "6_6") (pintype "passive"))
    )
    (net (code "379") (name "unconnected-(JP52-Pad7)") (class "Default")
      (node (ref "JP52") (pin "7") (pinfunction "7_7") (pintype "passive"))
    )
    (net (code "380") (name "unconnected-(JP52-Pad8)") (class "Default")
      (node (ref "JP52") (pin "8") (pinfunction "8_8") (pintype "passive"))
    )
    (net (code "381") (name "unconnected-(JP52-Pad9)") (class "Default")
      (node (ref "JP52") (pin "9") (pinfunction "9_9") (pintype "passive"))
    )
    (net (code "382") (name "unconnected-(JP52-Pad10)") (class "Default")
      (node (ref "JP52") (pin "10") (pinfunction "10_10") (pintype "passive"))
    )
    (net (code "383") (name "unconnected-(JP52-Pad11)") (class "Default")
      (node (ref "JP52") (pin "11") (pinfunction "11_11") (pintype "passive"))
    )
    (net (code "384") (name "unconnected-(JP52-Pad12)") (class "Default")
      (node (ref "JP52") (pin "12") (pinfunction "12_12") (pintype "passive"))
    )
    (net (code "385") (name "unconnected-(JP52-Pad13)") (class "Default")
      (node (ref "JP52") (pin "13") (pinfunction "13_13") (pintype "passive"))
    )
    (net (code "386") (name "unconnected-(JP52-Pad14)") (class "Default")
      (node (ref "JP52") (pin "14") (pinfunction "14_14") (pintype "passive"))
    )
    (net (code "387") (name "unconnected-(JP52-Pad15)") (class "Default")
      (node (ref "JP52") (pin "15") (pinfunction "15_15") (pintype "passive"))
    )
    (net (code "388") (name "unconnected-(JP52-Pad16)") (class "Default")
      (node (ref "JP52") (pin "16") (pinfunction "16_16") (pintype "passive"))
    )
    (net (code "389") (name "unconnected-(JP53-Pad2)") (class "Default")
      (node (ref "JP53") (pin "2") (pinfunction "2_2") (pintype "passive"))
    )
    (net (code "390") (name "unconnected-(JP53-Pad3)") (class "Default")
      (node (ref "JP53") (pin "3") (pinfunction "3_3") (pintype "passive"))
    )
    (net (code "391") (name "unconnected-(JP53-Pad4)") (class "Default")
      (node (ref "JP53") (pin "4") (pinfunction "4_4") (pintype "passive"))
    )
    (net (code "392") (name "unconnected-(JP53-Pad5)") (class "Default")
      (node (ref "JP53") (pin "5") (pinfunction "5_5") (pintype "passive"))
    )
    (net (code "393") (name "unconnected-(JP53-Pad6)") (class "Default")
      (node (ref "JP53") (pin "6") (pinfunction "6_6") (pintype "passive"))
    )
    (net (code "394") (name "unconnected-(JP53-Pad7)") (class "Default")
      (node (ref "JP53") (pin "7") (pinfunction "7_7") (pintype "passive"))
    )
    (net (code "395") (name "unconnected-(JP53-Pad8)") (class "Default")
      (node (ref "JP53") (pin "8") (pinfunction "8_8") (pintype "passive"))
    )
    (net (code "396") (name "unconnected-(JP53-Pad9)") (class "Default")
      (node (ref "JP53") (pin "9") (pinfunction "9_9") (pintype "passive"))
    )
    (net (code "397") (name "unconnected-(JP53-Pad10)") (class "Default")
      (node (ref "JP53") (pin "10") (pinfunction "10_10") (pintype "passive"))
    )
    (net (code "398") (name "unconnected-(JP53-Pad11)") (class "Default")
      (node (ref "JP53") (pin "11") (pinfunction "11_11") (pintype "passive"))
    )
    (net (code "399") (name "unconnected-(JP53-Pad12)") (class "Default")
      (node (ref "JP53") (pin "12") (pinfunction "12_12") (pintype "passive"))
    )
    (net (code "400") (name "unconnected-(JP53-Pad13)") (class "Default")
      (node (ref "JP53") (pin "13") (pinfunction "13_13") (pintype "passive"))
    )
    (net (code "401") (name "unconnected-(JP53-Pad14)") (class "Default")
      (node (ref "JP53") (pin "14") (pinfunction "14_14") (pintype "passive"))
    )
    (net (code "402") (name "unconnected-(JP53-Pad15)") (class "Default")
      (node (ref "JP53") (pin "15") (pinfunction "15_15") (pintype "passive"))
    )
    (net (code "403") (name "unconnected-(JP53-Pad16)") (class "Default")
      (node (ref "JP53") (pin "16") (pinfunction "16_16") (pintype "passive"))
    )
    (net (code "404") (name "unconnected-(JP56-Pad2)") (class "Default")
      (node (ref "JP56") (pin "2") (pinfunction "2_2") (pintype "passive"))
    )
    (net (code "405") (name "unconnected-(JP56-Pad3)") (class "Default")
      (node (ref "JP56") (pin "3") (pinfunction "3_3") (pintype "passive"))
    )
    (net (code "406") (name "unconnected-(JP56-Pad4)") (class "Default")
      (node (ref "JP56") (pin "4") (pinfunction "4_4") (pintype "passive"))
    )
    (net (code "407") (name "unconnected-(JP56-Pad5)") (class "Default")
      (node (ref "JP56") (pin "5") (pinfunction "5_5") (pintype "passive"))
    )
    (net (code "408") (name "unconnected-(JP56-Pad6)") (class "Default")
      (node (ref "JP56") (pin "6") (pinfunction "6_6") (pintype "passive"))
    )
    (net (code "409") (name "unconnected-(JP56-Pad7)") (class "Default")
      (node (ref "JP56") (pin "7") (pinfunction "7_7") (pintype "passive"))
    )
    (net (code "410") (name "unconnected-(JP56-Pad8)") (class "Default")
      (node (ref "JP56") (pin "8") (pinfunction "8_8") (pintype "passive"))
    )
    (net (code "411") (name "unconnected-(JP56-Pad9)") (class "Default")
      (node (ref "JP56") (pin "9") (pinfunction "9_9") (pintype "passive"))
    )
    (net (code "412") (name "unconnected-(JP56-Pad10)") (class "Default")
      (node (ref "JP56") (pin "10") (pinfunction "10_10") (pintype "passive"))
    )
    (net (code "413") (name "unconnected-(JP56-Pad11)") (class "Default")
      (node (ref "JP56") (pin "11") (pinfunction "11_11") (pintype "passive"))
    )
    (net (code "414") (name "unconnected-(JP56-Pad12)") (class "Default")
      (node (ref "JP56") (pin "12") (pinfunction "12_12") (pintype "passive"))
    )
    (net (code "415") (name "unconnected-(JP56-Pad13)") (class "Default")
      (node (ref "JP56") (pin "13") (pinfunction "13_13") (pintype "passive"))
    )
    (net (code "416") (name "unconnected-(JP56-Pad14)") (class "Default")
      (node (ref "JP56") (pin "14") (pinfunction "14_14") (pintype "passive"))
    )
    (net (code "417") (name "unconnected-(JP56-Pad15)") (class "Default")
      (node (ref "JP56") (pin "15") (pinfunction "15_15") (pintype "passive"))
    )
    (net (code "418") (name "unconnected-(JP56-Pad16)") (class "Default")
      (node (ref "JP56") (pin "16") (pinfunction "16_16") (pintype "passive"))
    )
    (net (code "419") (name "unconnected-(JP57-Pad2)") (class "Default")
      (node (ref "JP57") (pin "2") (pinfunction "2_2") (pintype "passive"))
    )
    (net (code "420") (name "unconnected-(JP57-Pad3)") (class "Default")
      (node (ref "JP57") (pin "3") (pinfunction "3_3") (pintype "passive"))
    )
    (net (code "421") (name "unconnected-(JP57-Pad4)") (class "Default")
      (node (ref "JP57") (pin "4") (pinfunction "4_4") (pintype "passive"))
    )
    (net (code "422") (name "unconnected-(JP57-Pad5)") (class "Default")
      (node (ref "JP57") (pin "5") (pinfunction "5_5") (pintype "passive"))
    )
    (net (code "423") (name "unconnected-(JP57-Pad6)") (class "Default")
      (node (ref "JP57") (pin "6") (pinfunction "6_6") (pintype "passive"))
    )
    (net (code "424") (name "unconnected-(JP57-Pad7)") (class "Default")
      (node (ref "JP57") (pin "7") (pinfunction "7_7") (pintype "passive"))
    )
    (net (code "425") (name "unconnected-(JP57-Pad8)") (class "Default")
      (node (ref "JP57") (pin "8") (pinfunction "8_8") (pintype "passive"))
    )
    (net (code "426") (name "unconnected-(JP57-Pad9)") (class "Default")
      (node (ref "JP57") (pin "9") (pinfunction "9_9") (pintype "passive"))
    )
    (net (code "427") (name "unconnected-(JP57-Pad10)") (class "Default")
      (node (ref "JP57") (pin "10") (pinfunction "10_10") (pintype "passive"))
    )
    (net (code "428") (name "unconnected-(JP57-Pad11)") (class "Default")
      (node (ref "JP57") (pin "11") (pinfunction "11_11") (pintype "passive"))
    )
    (net (code "429") (name "unconnected-(JP57-Pad12)") (class "Default")
      (node (ref "JP57") (pin "12") (pinfunction "12_12") (pintype "passive"))
    )
    (net (code "430") (name "unconnected-(JP57-Pad13)") (class "Default")
      (node (ref "JP57") (pin "13") (pinfunction "13_13") (pintype "passive"))
    )
    (net (code "431") (name "unconnected-(JP57-Pad14)") (class "Default")
      (node (ref "JP57") (pin "14") (pinfunction "14_14") (pintype "passive"))
    )
    (net (code "432") (name "unconnected-(JP57-Pad15)") (class "Default")
      (node (ref "JP57") (pin "15") (pinfunction "15_15") (pintype "passive"))
    )
    (net (code "433") (name "unconnected-(JP57-Pad16)") (class "Default")
      (node (ref "JP57") (pin "16") (pinfunction "16_16") (pintype "passive"))
    )
    (net (code "434") (name "unconnected-(JP58-Pad2)") (class "Default")
      (node (ref "JP58") (pin "2") (pinfunction "2_2") (pintype "passive"))
    )
    (net (code "435") (name "unconnected-(JP58-Pad3)") (class "Default")
      (node (ref "JP58") (pin "3") (pinfunction "3_3") (pintype "passive"))
    )
    (net (code "436") (name "unconnected-(JP58-Pad4)") (class "Default")
      (node (ref "JP58") (pin "4") (pinfunction "4_4") (pintype "passive"))
    )
    (net (code "437") (name "unconnected-(JP58-Pad5)") (class "Default")
      (node (ref "JP58") (pin "5") (pinfunction "5_5") (pintype "passive"))
    )
    (net (code "438") (name "unconnected-(JP58-Pad6)") (class "Default")
      (node (ref "JP58") (pin "6") (pinfunction "6_6") (pintype "passive"))
    )
    (net (code "439") (name "unconnected-(JP58-Pad7)") (class "Default")
      (node (ref "JP58") (pin "7") (pinfunction "7_7") (pintype "passive"))
    )
    (net (code "440") (name "unconnected-(JP58-Pad8)") (class "Default")
      (node (ref "JP58") (pin "8") (pinfunction "8_8") (pintype "passive"))
    )
    (net (code "441") (name "unconnected-(JP58-Pad9)") (class "Default")
      (node (ref "JP58") (pin "9") (pinfunction "9_9") (pintype "passive"))
    )
    (net (code "442") (name "unconnected-(JP58-Pad10)") (class "Default")
      (node (ref "JP58") (pin "10") (pinfunction "10_10") (pintype "passive"))
    )
    (net (code "443") (name "unconnected-(JP58-Pad11)") (class "Default")
      (node (ref "JP58") (pin "11") (pinfunction "11_11") (pintype "passive"))
    )
    (net (code "444") (name "unconnected-(JP58-Pad12)") (class "Default")
      (node (ref "JP58") (pin "12") (pinfunction "12_12") (pintype "passive"))
    )
    (net (code "445") (name "unconnected-(JP58-Pad13)") (class "Default")
      (node (ref "JP58") (pin "13") (pinfunction "13_13") (pintype "passive"))
    )
    (net (code "446") (name "unconnected-(JP58-Pad14)") (class "Default")
      (node (ref "JP58") (pin "14") (pinfunction "14_14") (pintype "passive"))
    )
    (net (code "447") (name "unconnected-(JP58-Pad15)") (class "Default")
      (node (ref "JP58") (pin "15") (pinfunction "15_15") (pintype "passive"))
    )
    (net (code "448") (name "unconnected-(JP58-Pad16)") (class "Default")
      (node (ref "JP58") (pin "16") (pinfunction "16_16") (pintype "passive"))
    )
    (net (code "449") (name "unconnected-(JP59-Pad2)") (class "Default")
      (node (ref "JP59") (pin "2") (pinfunction "2_2") (pintype "passive"))
    )
    (net (code "450") (name "unconnected-(JP59-Pad3)") (class "Default")
      (node (ref "JP59") (pin "3") (pinfunction "3_3") (pintype "passive"))
    )
    (net (code "451") (name "unconnected-(JP59-Pad4)") (class "Default")
      (node (ref "JP59") (pin "4") (pinfunction "4_4") (pintype "passive"))
    )
    (net (code "452") (name "unconnected-(JP59-Pad5)") (class "Default")
      (node (ref "JP59") (pin "5") (pinfunction "5_5") (pintype "passive"))
    )
    (net (code "453") (name "unconnected-(JP59-Pad6)") (class "Default")
      (node (ref "JP59") (pin "6") (pinfunction "6_6") (pintype "passive"))
    )
    (net (code "454") (name "unconnected-(JP59-Pad7)") (class "Default")
      (node (ref "JP59") (pin "7") (pinfunction "7_7") (pintype "passive"))
    )
    (net (code "455") (name "unconnected-(JP59-Pad8)") (class "Default")
      (node (ref "JP59") (pin "8") (pinfunction "8_8") (pintype "passive"))
    )
    (net (code "456") (name "unconnected-(JP59-Pad9)") (class "Default")
      (node (ref "JP59") (pin "9") (pinfunction "9_9") (pintype "passive"))
    )
    (net (code "457") (name "unconnected-(JP59-Pad10)") (class "Default")
      (node (ref "JP59") (pin "10") (pinfunction "10_10") (pintype "passive"))
    )
    (net (code "458") (name "unconnected-(JP59-Pad11)") (class "Default")
      (node (ref "JP59") (pin "11") (pinfunction "11_11") (pintype "passive"))
    )
    (net (code "459") (name "unconnected-(JP59-Pad12)") (class "Default")
      (node (ref "JP59") (pin "12") (pinfunction "12_12") (pintype "passive"))
    )
    (net (code "460") (name "unconnected-(JP59-Pad13)") (class "Default")
      (node (ref "JP59") (pin "13") (pinfunction "13_13") (pintype "passive"))
    )
    (net (code "461") (name "unconnected-(JP59-Pad14)") (class "Default")
      (node (ref "JP59") (pin "14") (pinfunction "14_14") (pintype "passive"))
    )
    (net (code "462") (name "unconnected-(JP59-Pad15)") (class "Default")
      (node (ref "JP59") (pin "15") (pinfunction "15_15") (pintype "passive"))
    )
    (net (code "463") (name "unconnected-(JP59-Pad16)") (class "Default")
      (node (ref "JP59") (pin "16") (pinfunction "16_16") (pintype "passive"))
    )
    (net (code "464") (name "unconnected-(JP60-Pad2)") (class "Default")
      (node (ref "JP60") (pin "2") (pinfunction "2_2") (pintype "passive"))
    )
    (net (code "465") (name "unconnected-(JP60-Pad3)") (class "Default")
      (node (ref "JP60") (pin "3") (pinfunction "3_3") (pintype "passive"))
    )
    (net (code "466") (name "unconnected-(JP60-Pad4)") (class "Default")
      (node (ref "JP60") (pin "4") (pinfunction "4_4") (pintype "passive"))
    )
    (net (code "467") (name "unconnected-(JP60-Pad5)") (class "Default")
      (node (ref "JP60") (pin "5") (pinfunction "5_5") (pintype "passive"))
    )
    (net (code "468") (name "unconnected-(JP60-Pad6)") (class "Default")
      (node (ref "JP60") (pin "6") (pinfunction "6_6") (pintype "passive"))
    )
    (net (code "469") (name "unconnected-(JP60-Pad7)") (class "Default")
      (node (ref "JP60") (pin "7") (pinfunction "7_7") (pintype "passive"))
    )
    (net (code "470") (name "unconnected-(JP60-Pad8)") (class "Default")
      (node (ref "JP60") (pin "8") (pinfunction "8_8") (pintype "passive"))
    )
    (net (code "471") (name "unconnected-(JP60-Pad9)") (class "Default")
      (node (ref "JP60") (pin "9") (pinfunction "9_9") (pintype "passive"))
    )
    (net (code "472") (name "unconnected-(JP60-Pad10)") (class "Default")
      (node (ref "JP60") (pin "10") (pinfunction "10_10") (pintype "passive"))
    )
    (net (code "473") (name "unconnected-(JP60-Pad11)") (class "Default")
      (node (ref "JP60") (pin "11") (pinfunction "11_11") (pintype "passive"))
    )
    (net (code "474") (name "unconnected-(JP60-Pad12)") (class "Default")
      (node (ref "JP60") (pin "12") (pinfunction "12_12") (pintype "passive"))
    )
    (net (code "475") (name "unconnected-(JP60-Pad13)") (class "Default")
      (node (ref "JP60") (pin "13") (pinfunction "13_13") (pintype "passive"))
    )
    (net (code "476") (name "unconnected-(JP60-Pad14)") (class "Default")
      (node (ref "JP60") (pin "14") (pinfunction "14_14") (pintype "passive"))
    )
    (net (code "477") (name "unconnected-(JP60-Pad15)") (class "Default")
      (node (ref "JP60") (pin "15") (pinfunction "15_15") (pintype "passive"))
    )
    (net (code "478") (name "unconnected-(JP60-Pad16)") (class "Default")
      (node (ref "JP60") (pin "16") (pinfunction "16_16") (pintype "passive"))
    )
    (net (code "479") (name "unconnected-(JP61-Pad2)") (class "Default")
      (node (ref "JP61") (pin "2") (pinfunction "2_2") (pintype "passive"))
    )
    (net (code "480") (name "unconnected-(JP61-Pad3)") (class "Default")
      (node (ref "JP61") (pin "3") (pinfunction "3_3") (pintype "passive"))
    )
    (net (code "481") (name "unconnected-(JP61-Pad4)") (class "Default")
      (node (ref "JP61") (pin "4") (pinfunction "4_4") (pintype "passive"))
    )
    (net (code "482") (name "unconnected-(JP61-Pad5)") (class "Default")
      (node (ref "JP61") (pin "5") (pinfunction "5_5") (pintype "passive"))
    )
    (net (code "483") (name "unconnected-(JP61-Pad6)") (class "Default")
      (node (ref "JP61") (pin "6") (pinfunction "6_6") (pintype "passive"))
    )
    (net (code "484") (name "unconnected-(JP61-Pad7)") (class "Default")
      (node (ref "JP61") (pin "7") (pinfunction "7_7") (pintype "passive"))
    )
    (net (code "485") (name "unconnected-(JP61-Pad8)") (class "Default")
      (node (ref "JP61") (pin "8") (pinfunction "8_8") (pintype "passive"))
    )
    (net (code "486") (name "unconnected-(JP61-Pad9)") (class "Default")
      (node (ref "JP61") (pin "9") (pinfunction "9_9") (pintype "passive"))
    )
    (net (code "487") (name "unconnected-(JP61-Pad10)") (class "Default")
      (node (ref "JP61") (pin "10") (pinfunction "10_10") (pintype "passive"))
    )
    (net (code "488") (name "unconnected-(JP61-Pad11)") (class "Default")
      (node (ref "JP61") (pin "11") (pinfunction "11_11") (pintype "passive"))
    )
    (net (code "489") (name "unconnected-(JP61-Pad12)") (class "Default")
      (node (ref "JP61") (pin "12") (pinfunction "12_12") (pintype "passive"))
    )
    (net (code "490") (name "unconnected-(JP61-Pad13)") (class "Default")
      (node (ref "JP61") (pin "13") (pinfunction "13_13") (pintype "passive"))
    )
    (net (code "491") (name "unconnected-(JP61-Pad14)") (class "Default")
      (node (ref "JP61") (pin "14") (pinfunction "14_14") (pintype "passive"))
    )
    (net (code "492") (name "unconnected-(JP61-Pad15)") (class "Default")
      (node (ref "JP61") (pin "15") (pinfunction "15_15") (pintype "passive"))
    )
    (net (code "493") (name "unconnected-(JP61-Pad16)") (class "Default")
      (node (ref "JP61") (pin "16") (pinfunction "16_16") (pintype "passive"))
    )
    (net (code "494") (name "unconnected-(JP62-Pad2)") (class "Default")
      (node (ref "JP62") (pin "2") (pinfunction "2_2") (pintype "passive"))
    )
    (net (code "495") (name "unconnected-(JP62-Pad3)") (class "Default")
      (node (ref "JP62") (pin "3") (pinfunction "3_3") (pintype "passive"))
    )
    (net (code "496") (name "unconnected-(JP62-Pad4)") (class "Default")
      (node (ref "JP62") (pin "4") (pinfunction "4_4") (pintype "passive"))
    )
    (net (code "497") (name "unconnected-(JP62-Pad5)") (class "Default")
      (node (ref "JP62") (pin "5") (pinfunction "5_5") (pintype "passive"))
    )
    (net (code "498") (name "unconnected-(JP62-Pad6)") (class "Default")
      (node (ref "JP62") (pin "6") (pinfunction "6_6") (pintype "passive"))
    )
    (net (code "499") (name "unconnected-(JP62-Pad7)") (class "Default")
      (node (ref "JP62") (pin "7") (pinfunction "7_7") (pintype "passive"))
    )
    (net (code "500") (name "unconnected-(JP62-Pad8)") (class "Default")
      (node (ref "JP62") (pin "8") (pinfunction "8_8") (pintype "passive"))
    )
    (net (code "501") (name "unconnected-(JP62-Pad9)") (class "Default")
      (node (ref "JP62") (pin "9") (pinfunction "9_9") (pintype "passive"))
    )
    (net (code "502") (name "unconnected-(JP62-Pad10)") (class "Default")
      (node (ref "JP62") (pin "10") (pinfunction "10_10") (pintype "passive"))
    )
    (net (code "503") (name "unconnected-(JP62-Pad11)") (class "Default")
      (node (ref "JP62") (pin "11") (pinfunction "11_11") (pintype "passive"))
    )
    (net (code "504") (name "unconnected-(JP62-Pad12)") (class "Default")
      (node (ref "JP62") (pin "12") (pinfunction "12_12") (pintype "passive"))
    )
    (net (code "505") (name "unconnected-(JP62-Pad13)") (class "Default")
      (node (ref "JP62") (pin "13") (pinfunction "13_13") (pintype "passive"))
    )
    (net (code "506") (name "unconnected-(JP62-Pad14)") (class "Default")
      (node (ref "JP62") (pin "14") (pinfunction "14_14") (pintype "passive"))
    )
    (net (code "507") (name "unconnected-(JP62-Pad15)") (class "Default")
      (node (ref "JP62") (pin "15") (pinfunction "15_15") (pintype "passive"))
    )
    (net (code "508") (name "unconnected-(JP62-Pad16)") (class "Default")
      (node (ref "JP62") (pin "16") (pinfunction "16_16") (pintype "passive"))
    )
    (net (code "509") (name "unconnected-(JP63-Pad2)") (class "Default")
      (node (ref "JP63") (pin "2") (pinfunction "2_2") (pintype "passive"))
    )
    (net (code "510") (name "unconnected-(JP63-Pad3)") (class "Default")
      (node (ref "JP63") (pin "3") (pinfunction "3_3") (pintype "passive"))
    )
    (net (code "511") (name "unconnected-(JP63-Pad4)") (class "Default")
      (node (ref "JP63") (pin "4") (pinfunction "4_4") (pintype "passive"))
    )
    (net (code "512") (name "unconnected-(JP63-Pad5)") (class "Default")
      (node (ref "JP63") (pin "5") (pinfunction "5_5") (pintype "passive"))
    )
    (net (code "513") (name "unconnected-(JP63-Pad6)") (class "Default")
      (node (ref "JP63") (pin "6") (pinfunction "6_6") (pintype "passive"))
    )
    (net (code "514") (name "unconnected-(JP63-Pad7)") (class "Default")
      (node (ref "JP63") (pin "7") (pinfunction "7_7") (pintype "passive"))
    )
    (net (code "515") (name "unconnected-(JP63-Pad8)") (class "Default")
      (node (ref "JP63") (pin "8") (pinfunction "8_8") (pintype "passive"))
    )
    (net (code "516") (name "unconnected-(JP63-Pad9)") (class "Default")
      (node (ref "JP63") (pin "9") (pinfunction "9_9") (pintype "passive"))
    )
    (net (code "517") (name "unconnected-(JP63-Pad10)") (class "Default")
      (node (ref "JP63") (pin "10") (pinfunction "10_10") (pintype "passive"))
    )
    (net (code "518") (name "unconnected-(JP63-Pad11)") (class "Default")
      (node (ref "JP63") (pin "11") (pinfunction "11_11") (pintype "passive"))
    )
    (net (code "519") (name "unconnected-(JP63-Pad12)") (class "Default")
      (node (ref "JP63") (pin "12") (pinfunction "12_12") (pintype "passive"))
    )
    (net (code "520") (name "unconnected-(JP63-Pad13)") (class "Default")
      (node (ref "JP63") (pin "13") (pinfunction "13_13") (pintype "passive"))
    )
    (net (code "521") (name "unconnected-(JP63-Pad14)") (class "Default")
      (node (ref "JP63") (pin "14") (pinfunction "14_14") (pintype "passive"))
    )
    (net (code "522") (name "unconnected-(JP63-Pad15)") (class "Default")
      (node (ref "JP63") (pin "15") (pinfunction "15_15") (pintype "passive"))
    )
    (net (code "523") (name "unconnected-(JP63-Pad16)") (class "Default")
      (node (ref "JP63") (pin "16") (pinfunction "16_16") (pintype "passive"))
    )
    (net (code "524") (name "unconnected-(JP64-Pad2)") (class "Default")
      (node (ref "JP64") (pin "2") (pinfunction "2_2") (pintype "passive"))
    )
    (net (code "525") (name "unconnected-(JP64-Pad3)") (class "Default")
      (node (ref "JP64") (pin "3") (pinfunction "3_3") (pintype "passive"))
    )
    (net (code "526") (name "unconnected-(JP64-Pad4)") (class "Default")
      (node (ref "JP64") (pin "4") (pinfunction "4_4") (pintype "passive"))
    )
    (net (code "527") (name "unconnected-(JP64-Pad5)") (class "Default")
      (node (ref "JP64") (pin "5") (pinfunction "5_5") (pintype "passive"))
    )
    (net (code "528") (name "unconnected-(JP64-Pad6)") (class "Default")
      (node (ref "JP64") (pin "6") (pinfunction "6_6") (pintype "passive"))
    )
    (net (code "529") (name "unconnected-(JP64-Pad7)") (class "Default")
      (node (ref "JP64") (pin "7") (pinfunction "7_7") (pintype "passive"))
    )
    (net (code "530") (name "unconnected-(JP64-Pad8)") (class "Default")
      (node (ref "JP64") (pin "8") (pinfunction "8_8") (pintype "passive"))
    )
    (net (code "531") (name "unconnected-(JP64-Pad9)") (class "Default")
      (node (ref "JP64") (pin "9") (pinfunction "9_9") (pintype "passive"))
    )
    (net (code "532") (name "unconnected-(JP64-Pad10)") (class "Default")
      (node (ref "JP64") (pin "10") (pinfunction "10_10") (pintype "passive"))
    )
    (net (code "533") (name "unconnected-(JP64-Pad11)") (class "Default")
      (node (ref "JP64") (pin "11") (pinfunction "11_11") (pintype "passive"))
    )
    (net (code "534") (name "unconnected-(JP64-Pad12)") (class "Default")
      (node (ref "JP64") (pin "12") (pinfunction "12_12") (pintype "passive"))
    )
    (net (code "535") (name "unconnected-(JP64-Pad13)") (class "Default")
      (node (ref "JP64") (pin "13") (pinfunction "13_13") (pintype "passive"))
    )
    (net (code "536") (name "unconnected-(JP64-Pad14)") (class "Default")
      (node (ref "JP64") (pin "14") (pinfunction "14_14") (pintype "passive"))
    )
    (net (code "537") (name "unconnected-(JP64-Pad15)") (class "Default")
      (node (ref "JP64") (pin "15") (pinfunction "15_15") (pintype "passive"))
    )
    (net (code "538") (name "unconnected-(JP64-Pad16)") (class "Default")
      (node (ref "JP64") (pin "16") (pinfunction "16_16") (pintype "passive"))
    )
    (net (code "539") (name "unconnected-(JP65-Pad2)") (class "Default")
      (node (ref "JP65") (pin "2") (pinfunction "2_2") (pintype "passive"))
    )
    (net (code "540") (name "unconnected-(JP65-Pad3)") (class "Default")
      (node (ref "JP65") (pin "3") (pinfunction "3_3") (pintype "passive"))
    )
    (net (code "541") (name "unconnected-(JP65-Pad4)") (class "Default")
      (node (ref "JP65") (pin "4") (pinfunction "4_4") (pintype "passive"))
    )
    (net (code "542") (name "unconnected-(JP65-Pad5)") (class "Default")
      (node (ref "JP65") (pin "5") (pinfunction "5_5") (pintype "passive"))
    )
    (net (code "543") (name "unconnected-(JP65-Pad6)") (class "Default")
      (node (ref "JP65") (pin "6") (pinfunction "6_6") (pintype "passive"))
    )
    (net (code "544") (name "unconnected-(JP65-Pad7)") (class "Default")
      (node (ref "JP65") (pin "7") (pinfunction "7_7") (pintype "passive"))
    )
    (net (code "545") (name "unconnected-(JP65-Pad8)") (class "Default")
      (node (ref "JP65") (pin "8") (pinfunction "8_8") (pintype "passive"))
    )
    (net (code "546") (name "unconnected-(JP65-Pad9)") (class "Default")
      (node (ref "JP65") (pin "9") (pinfunction "9_9") (pintype "passive"))
    )
    (net (code "547") (name "unconnected-(JP65-Pad10)") (class "Default")
      (node (ref "JP65") (pin "10") (pinfunction "10_10") (pintype "passive"))
    )
    (net (code "548") (name "unconnected-(JP65-Pad11)") (class "Default")
      (node (ref "JP65") (pin "11") (pinfunction "11_11") (pintype "passive"))
    )
    (net (code "549") (name "unconnected-(JP65-Pad12)") (class "Default")
      (node (ref "JP65") (pin "12") (pinfunction "12_12") (pintype "passive"))
    )
    (net (code "550") (name "unconnected-(JP65-Pad13)") (class "Default")
      (node (ref "JP65") (pin "13") (pinfunction "13_13") (pintype "passive"))
    )
    (net (code "551") (name "unconnected-(JP65-Pad14)") (class "Default")
      (node (ref "JP65") (pin "14") (pinfunction "14_14") (pintype "passive"))
    )
    (net (code "552") (name "unconnected-(JP65-Pad15)") (class "Default")
      (node (ref "JP65") (pin "15") (pinfunction "15_15") (pintype "passive"))
    )
    (net (code "553") (name "unconnected-(JP65-Pad16)") (class "Default")
      (node (ref "JP65") (pin "16") (pinfunction "16_16") (pintype "passive"))
    )
    (net (code "554") (name "unconnected-(JP66-Pad2)") (class "Default")
      (node (ref "JP66") (pin "2") (pinfunction "2_2") (pintype "passive"))
    )
    (net (code "555") (name "unconnected-(JP66-Pad3)") (class "Default")
      (node (ref "JP66") (pin "3") (pinfunction "3_3") (pintype "passive"))
    )
    (net (code "556") (name "unconnected-(JP66-Pad4)") (class "Default")
      (node (ref "JP66") (pin "4") (pinfunction "4_4") (pintype "passive"))
    )
    (net (code "557") (name "unconnected-(JP66-Pad5)") (class "Default")
      (node (ref "JP66") (pin "5") (pinfunction "5_5") (pintype "passive"))
    )
    (net (code "558") (name "unconnected-(JP66-Pad6)") (class "Default")
      (node (ref "JP66") (pin "6") (pinfunction "6_6") (pintype "passive"))
    )
    (net (code "559") (name "unconnected-(JP66-Pad7)") (class "Default")
      (node (ref "JP66") (pin "7") (pinfunction "7_7") (pintype "passive"))
    )
    (net (code "560") (name "unconnected-(JP66-Pad8)") (class "Default")
      (node (ref "JP66") (pin "8") (pinfunction "8_8") (pintype "passive"))
    )
    (net (code "561") (name "unconnected-(JP66-Pad9)") (class "Default")
      (node (ref "JP66") (pin "9") (pinfunction "9_9") (pintype "passive"))
    )
    (net (code "562") (name "unconnected-(JP66-Pad10)") (class "Default")
      (node (ref "JP66") (pin "10") (pinfunction "10_10") (pintype "passive"))
    )
    (net (code "563") (name "unconnected-(JP66-Pad11)") (class "Default")
      (node (ref "JP66") (pin "11") (pinfunction "11_11") (pintype "passive"))
    )
    (net (code "564") (name "unconnected-(JP66-Pad12)") (class "Default")
      (node (ref "JP66") (pin "12") (pinfunction "12_12") (pintype "passive"))
    )
    (net (code "565") (name "unconnected-(JP66-Pad13)") (class "Default")
      (node (ref "JP66") (pin "13") (pinfunction "13_13") (pintype "passive"))
    )
    (net (code "566") (name "unconnected-(JP66-Pad14)") (class "Default")
      (node (ref "JP66") (pin "14") (pinfunction "14_14") (pintype "passive"))
    )
    (net (code "567") (name "unconnected-(JP66-Pad15)") (class "Default")
      (node (ref "JP66") (pin "15") (pinfunction "15_15") (pintype "passive"))
    )
    (net (code "568") (name "unconnected-(JP66-Pad16)") (class "Default")
      (node (ref "JP66") (pin "16") (pinfunction "16_16") (pintype "passive"))
    )
    (net (code "569") (name "unconnected-(JP67-Pad2)") (class "Default")
      (node (ref "JP67") (pin "2") (pinfunction "2_2") (pintype "passive"))
    )
    (net (code "570") (name "unconnected-(JP67-Pad3)") (class "Default")
      (node (ref "JP67") (pin "3") (pinfunction "3_3") (pintype "passive"))
    )
    (net (code "571") (name "unconnected-(JP67-Pad4)") (class "Default")
      (node (ref "JP67") (pin "4") (pinfunction "4_4") (pintype "passive"))
    )
    (net (code "572") (name "unconnected-(JP67-Pad5)") (class "Default")
      (node (ref "JP67") (pin "5") (pinfunction "5_5") (pintype "passive"))
    )
    (net (code "573") (name "unconnected-(JP67-Pad6)") (class "Default")
      (node (ref "JP67") (pin "6") (pinfunction "6_6") (pintype "passive"))
    )
    (net (code "574") (name "unconnected-(JP67-Pad7)") (class "Default")
      (node (ref "JP67") (pin "7") (pinfunction "7_7") (pintype "passive"))
    )
    (net (code "575") (name "unconnected-(JP67-Pad8)") (class "Default")
      (node (ref "JP67") (pin "8") (pinfunction "8_8") (pintype "passive"))
    )
    (net (code "576") (name "unconnected-(JP67-Pad9)") (class "Default")
      (node (ref "JP67") (pin "9") (pinfunction "9_9") (pintype "passive"))
    )
    (net (code "577") (name "unconnected-(JP67-Pad10)") (class "Default")
      (node (ref "JP67") (pin "10") (pinfunction "10_10") (pintype "passive"))
    )
    (net (code "578") (name "unconnected-(JP67-Pad11)") (class "Default")
      (node (ref "JP67") (pin "11") (pinfunction "11_11") (pintype "passive"))
    )
    (net (code "579") (name "unconnected-(JP67-Pad12)") (class "Default")
      (node (ref "JP67") (pin "12") (pinfunction "12_12") (pintype "passive"))
    )
    (net (code "580") (name "unconnected-(JP67-Pad13)") (class "Default")
      (node (ref "JP67") (pin "13") (pinfunction "13_13") (pintype "passive"))
    )
    (net (code "581") (name "unconnected-(JP67-Pad14)") (class "Default")
      (node (ref "JP67") (pin "14") (pinfunction "14_14") (pintype "passive"))
    )
    (net (code "582") (name "unconnected-(JP67-Pad15)") (class "Default")
      (node (ref "JP67") (pin "15") (pinfunction "15_15") (pintype "passive"))
    )
    (net (code "583") (name "unconnected-(JP67-Pad16)") (class "Default")
      (node (ref "JP67") (pin "16") (pinfunction "16_16") (pintype "passive"))
    )
    (net (code "584") (name "unconnected-(JP68-Pad2)") (class "Default")
      (node (ref "JP68") (pin "2") (pinfunction "2_2") (pintype "passive"))
    )
    (net (code "585") (name "unconnected-(JP68-Pad3)") (class "Default")
      (node (ref "JP68") (pin "3") (pinfunction "3_3") (pintype "passive"))
    )
    (net (code "586") (name "unconnected-(JP68-Pad4)") (class "Default")
      (node (ref "JP68") (pin "4") (pinfunction "4_4") (pintype "passive"))
    )
    (net (code "587") (name "unconnected-(JP68-Pad5)") (class "Default")
      (node (ref "JP68") (pin "5") (pinfunction "5_5") (pintype "passive"))
    )
    (net (code "588") (name "unconnected-(JP68-Pad6)") (class "Default")
      (node (ref "JP68") (pin "6") (pinfunction "6_6") (pintype "passive"))
    )
    (net (code "589") (name "unconnected-(JP68-Pad7)") (class "Default")
      (node (ref "JP68") (pin "7") (pinfunction "7_7") (pintype "passive"))
    )
    (net (code "590") (name "unconnected-(JP68-Pad8)") (class "Default")
      (node (ref "JP68") (pin "8") (pinfunction "8_8") (pintype "passive"))
    )
    (net (code "591") (name "unconnected-(JP68-Pad9)") (class "Default")
      (node (ref "JP68") (pin "9") (pinfunction "9_9") (pintype "passive"))
    )
    (net (code "592") (name "unconnected-(JP68-Pad10)") (class "Default")
      (node (ref "JP68") (pin "10") (pinfunction "10_10") (pintype "passive"))
    )
    (net (code "593") (name "unconnected-(JP68-Pad11)") (class "Default")
      (node (ref "JP68") (pin "11") (pinfunction "11_11") (pintype "passive"))
    )
    (net (code "594") (name "unconnected-(JP68-Pad12)") (class "Default")
      (node (ref "JP68") (pin "12") (pinfunction "12_12") (pintype "passive"))
    )
    (net (code "595") (name "unconnected-(JP68-Pad13)") (class "Default")
      (node (ref "JP68") (pin "13") (pinfunction "13_13") (pintype "passive"))
    )
    (net (code "596") (name "unconnected-(JP68-Pad14)") (class "Default")
      (node (ref "JP68") (pin "14") (pinfunction "14_14") (pintype "passive"))
    )
    (net (code "597") (name "unconnected-(JP68-Pad15)") (class "Default")
      (node (ref "JP68") (pin "15") (pinfunction "15_15") (pintype "passive"))
    )
    (net (code "598") (name "unconnected-(JP68-Pad16)") (class "Default")
      (node (ref "JP68") (pin "16") (pinfunction "16_16") (pintype "passive"))
    )
    (net (code "599") (name "unconnected-(JP69-Pad2)") (class "Default")
      (node (ref "JP69") (pin "2") (pinfunction "2_2") (pintype "passive"))
    )
    (net (code "600") (name "unconnected-(JP69-Pad3)") (class "Default")
      (node (ref "JP69") (pin "3") (pinfunction "3_3") (pintype "passive"))
    )
    (net (code "601") (name "unconnected-(JP69-Pad4)") (class "Default")
      (node (ref "JP69") (pin "4") (pinfunction "4_4") (pintype "passive"))
    )
    (net (code "602") (name "unconnected-(JP69-Pad5)") (class "Default")
      (node (ref "JP69") (pin "5") (pinfunction "5_5") (pintype "passive"))
    )
    (net (code "603") (name "unconnected-(JP69-Pad6)") (class "Default")
      (node (ref "JP69") (pin "6") (pinfunction "6_6") (pintype "passive"))
    )
    (net (code "604") (name "unconnected-(JP69-Pad7)") (class "Default")
      (node (ref "JP69") (pin "7") (pinfunction "7_7") (pintype "passive"))
    )
    (net (code "605") (name "unconnected-(JP69-Pad8)") (class "Default")
      (node (ref "JP69") (pin "8") (pinfunction "8_8") (pintype "passive"))
    )
    (net (code "606") (name "unconnected-(JP69-Pad9)") (class "Default")
      (node (ref "JP69") (pin "9") (pinfunction "9_9") (pintype "passive"))
    )
    (net (code "607") (name "unconnected-(JP69-Pad10)") (class "Default")
      (node (ref "JP69") (pin "10") (pinfunction "10_10") (pintype "passive"))
    )
    (net (code "608") (name "unconnected-(JP69-Pad11)") (class "Default")
      (node (ref "JP69") (pin "11") (pinfunction "11_11") (pintype "passive"))
    )
    (net (code "609") (name "unconnected-(JP69-Pad12)") (class "Default")
      (node (ref "JP69") (pin "12") (pinfunction "12_12") (pintype "passive"))
    )
    (net (code "610") (name "unconnected-(JP69-Pad13)") (class "Default")
      (node (ref "JP69") (pin "13") (pinfunction "13_13") (pintype "passive"))
    )
    (net (code "611") (name "unconnected-(JP69-Pad14)") (class "Default")
      (node (ref "JP69") (pin "14") (pinfunction "14_14") (pintype "passive"))
    )
    (net (code "612") (name "unconnected-(JP69-Pad15)") (class "Default")
      (node (ref "JP69") (pin "15") (pinfunction "15_15") (pintype "passive"))
    )
    (net (code "613") (name "unconnected-(JP69-Pad16)") (class "Default")
      (node (ref "JP69") (pin "16") (pinfunction "16_16") (pintype "passive"))
    )
    (net (code "614") (name "unconnected-(JP70-Pad2)") (class "Default")
      (node (ref "JP70") (pin "2") (pinfunction "2_2") (pintype "passive"))
    )
    (net (code "615") (name "unconnected-(JP70-Pad3)") (class "Default")
      (node (ref "JP70") (pin "3") (pinfunction "3_3") (pintype "passive"))
    )
    (net (code "616") (name "unconnected-(JP70-Pad4)") (class "Default")
      (node (ref "JP70") (pin "4") (pinfunction "4_4") (pintype "passive"))
    )
    (net (code "617") (name "unconnected-(JP70-Pad5)") (class "Default")
      (node (ref "JP70") (pin "5") (pinfunction "5_5") (pintype "passive"))
    )
    (net (code "618") (name "unconnected-(JP70-Pad6)") (class "Default")
      (node (ref "JP70") (pin "6") (pinfunction "6_6") (pintype "passive"))
    )
    (net (code "619") (name "unconnected-(JP70-Pad7)") (class "Default")
      (node (ref "JP70") (pin "7") (pinfunction "7_7") (pintype "passive"))
    )
    (net (code "620") (name "unconnected-(JP70-Pad8)") (class "Default")
      (node (ref "JP70") (pin "8") (pinfunction "8_8") (pintype "passive"))
    )
    (net (code "621") (name "unconnected-(JP70-Pad9)") (class "Default")
      (node (ref "JP70") (pin "9") (pinfunction "9_9") (pintype "passive"))
    )
    (net (code "622") (name "unconnected-(JP70-Pad10)") (class "Default")
      (node (ref "JP70") (pin "10") (pinfunction "10_10") (pintype "passive"))
    )
    (net (code "623") (name "unconnected-(JP70-Pad11)") (class "Default")
      (node (ref "JP70") (pin "11") (pinfunction "11_11") (pintype "passive"))
    )
    (net (code "624") (name "unconnected-(JP70-Pad12)") (class "Default")
      (node (ref "JP70") (pin "12") (pinfunction "12_12") (pintype "passive"))
    )
    (net (code "625") (name "unconnected-(JP70-Pad13)") (class "Default")
      (node (ref "JP70") (pin "13") (pinfunction "13_13") (pintype "passive"))
    )
    (net (code "626") (name "unconnected-(JP70-Pad14)") (class "Default")
      (node (ref "JP70") (pin "14") (pinfunction "14_14") (pintype "passive"))
    )
    (net (code "627") (name "unconnected-(JP70-Pad15)") (class "Default")
      (node (ref "JP70") (pin "15") (pinfunction "15_15") (pintype "passive"))
    )
    (net (code "628") (name "unconnected-(JP70-Pad16)") (class "Default")
      (node (ref "JP70") (pin "16") (pinfunction "16_16") (pintype "passive"))
    )
  )
)
